# SMPS.net
KiCad netlist of a schematic drawn in Altium Designer
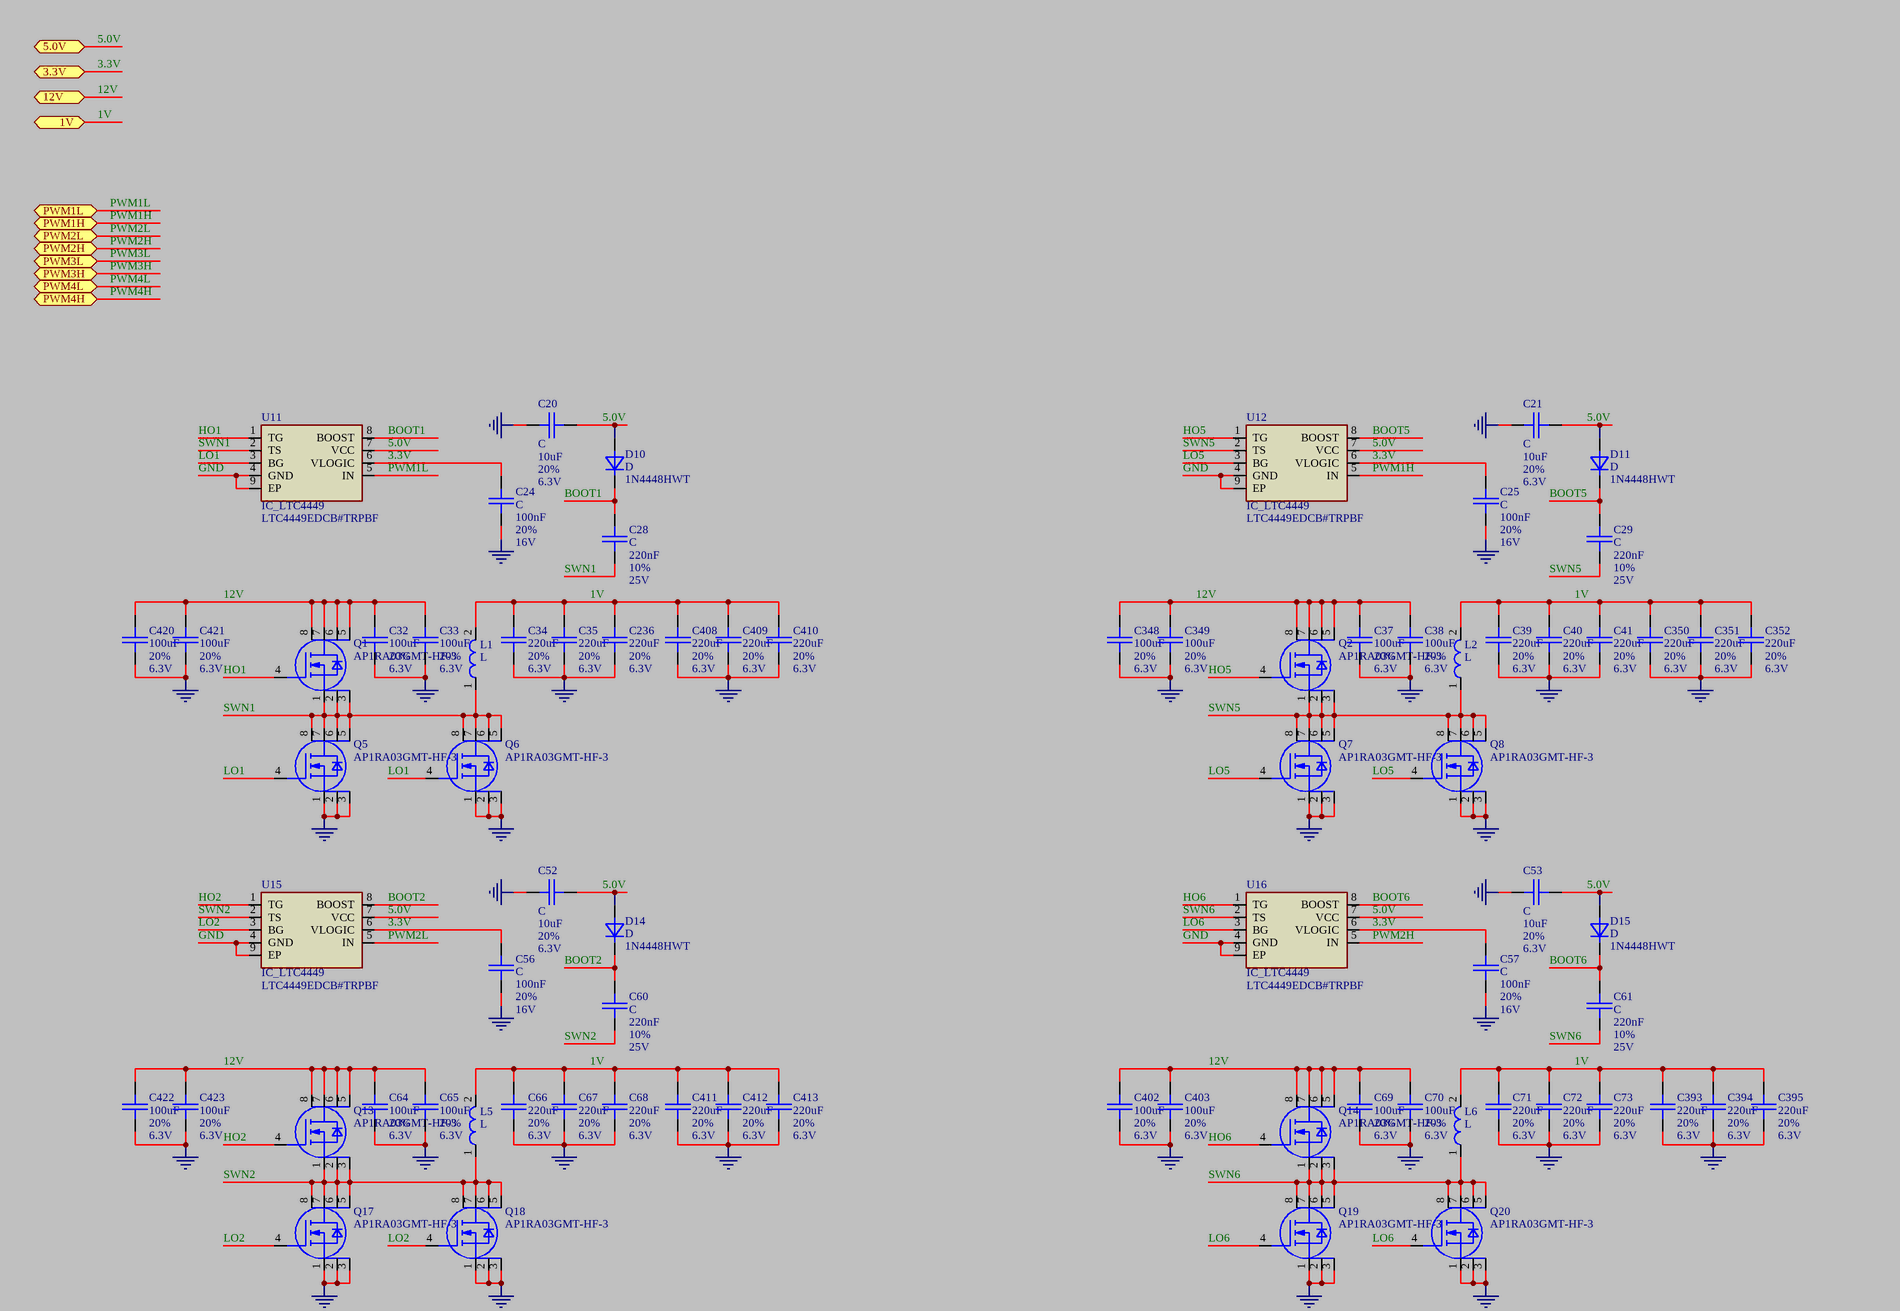
[diagram p0: SMPS.SchDoc, top left]
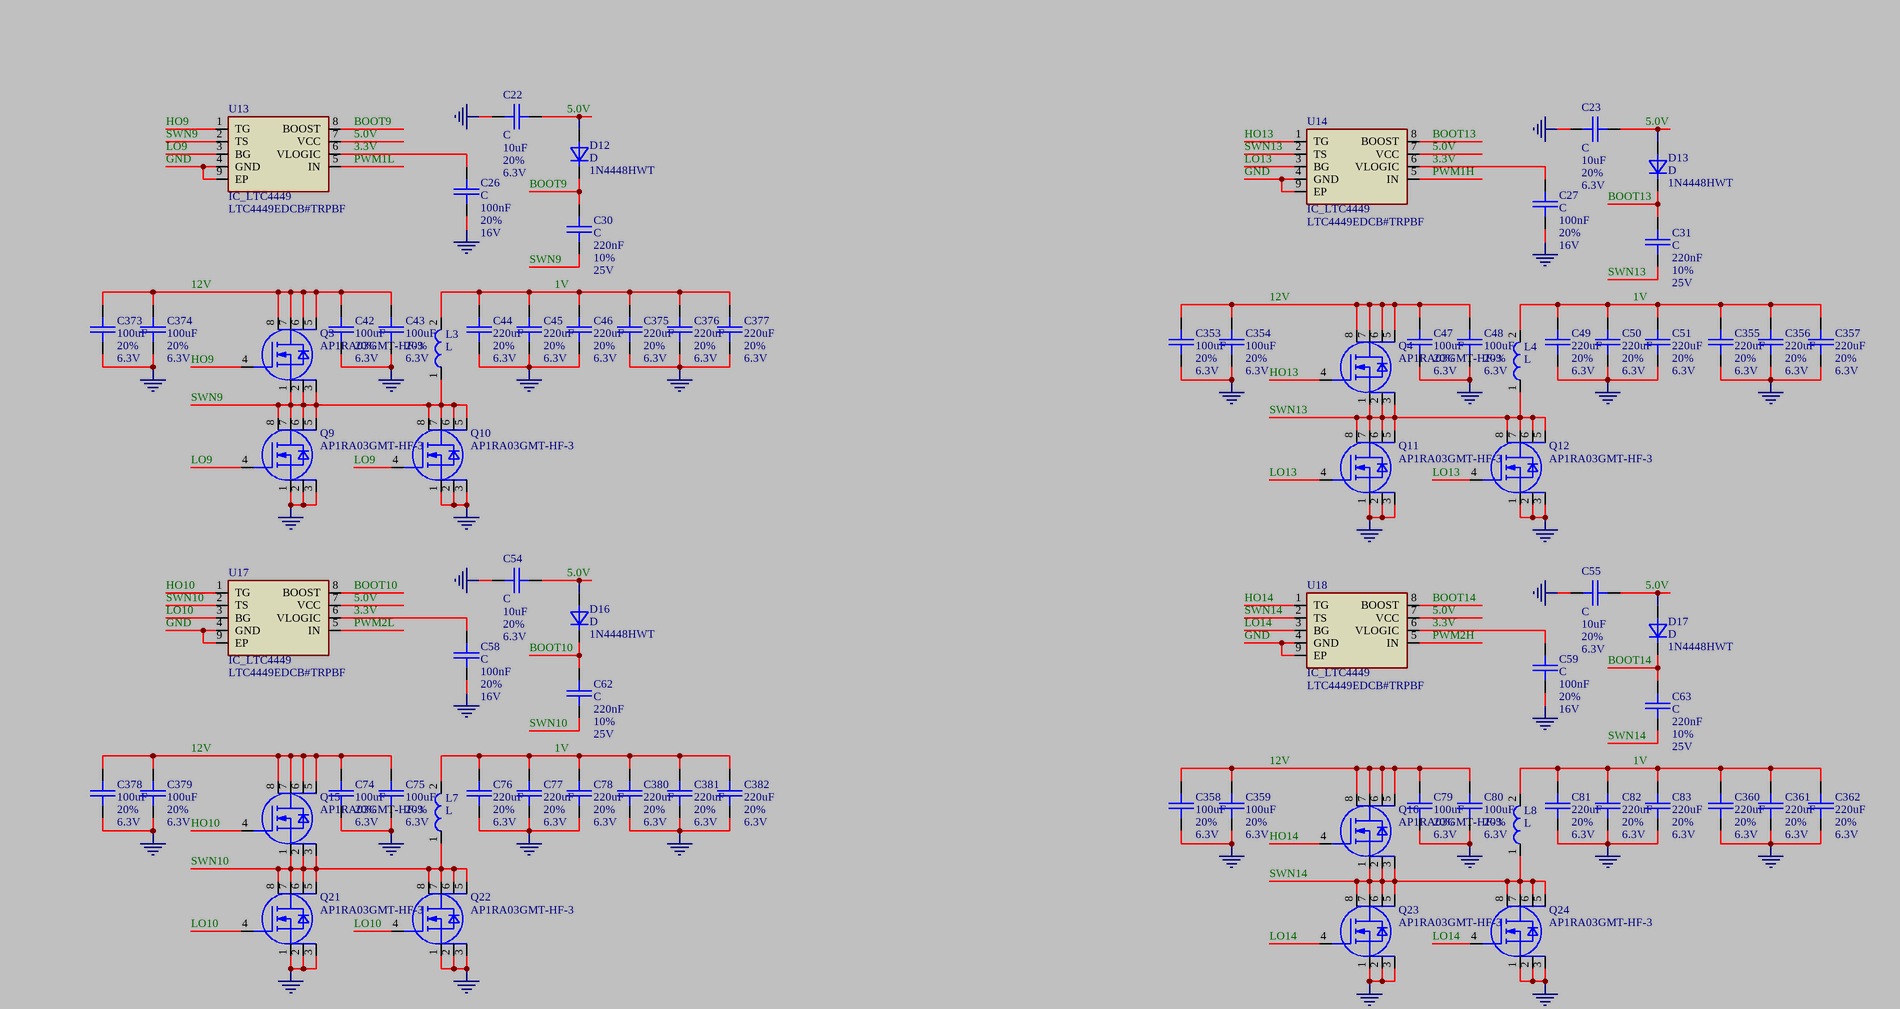
[diagram p1: SMPS.SchDoc, top right]
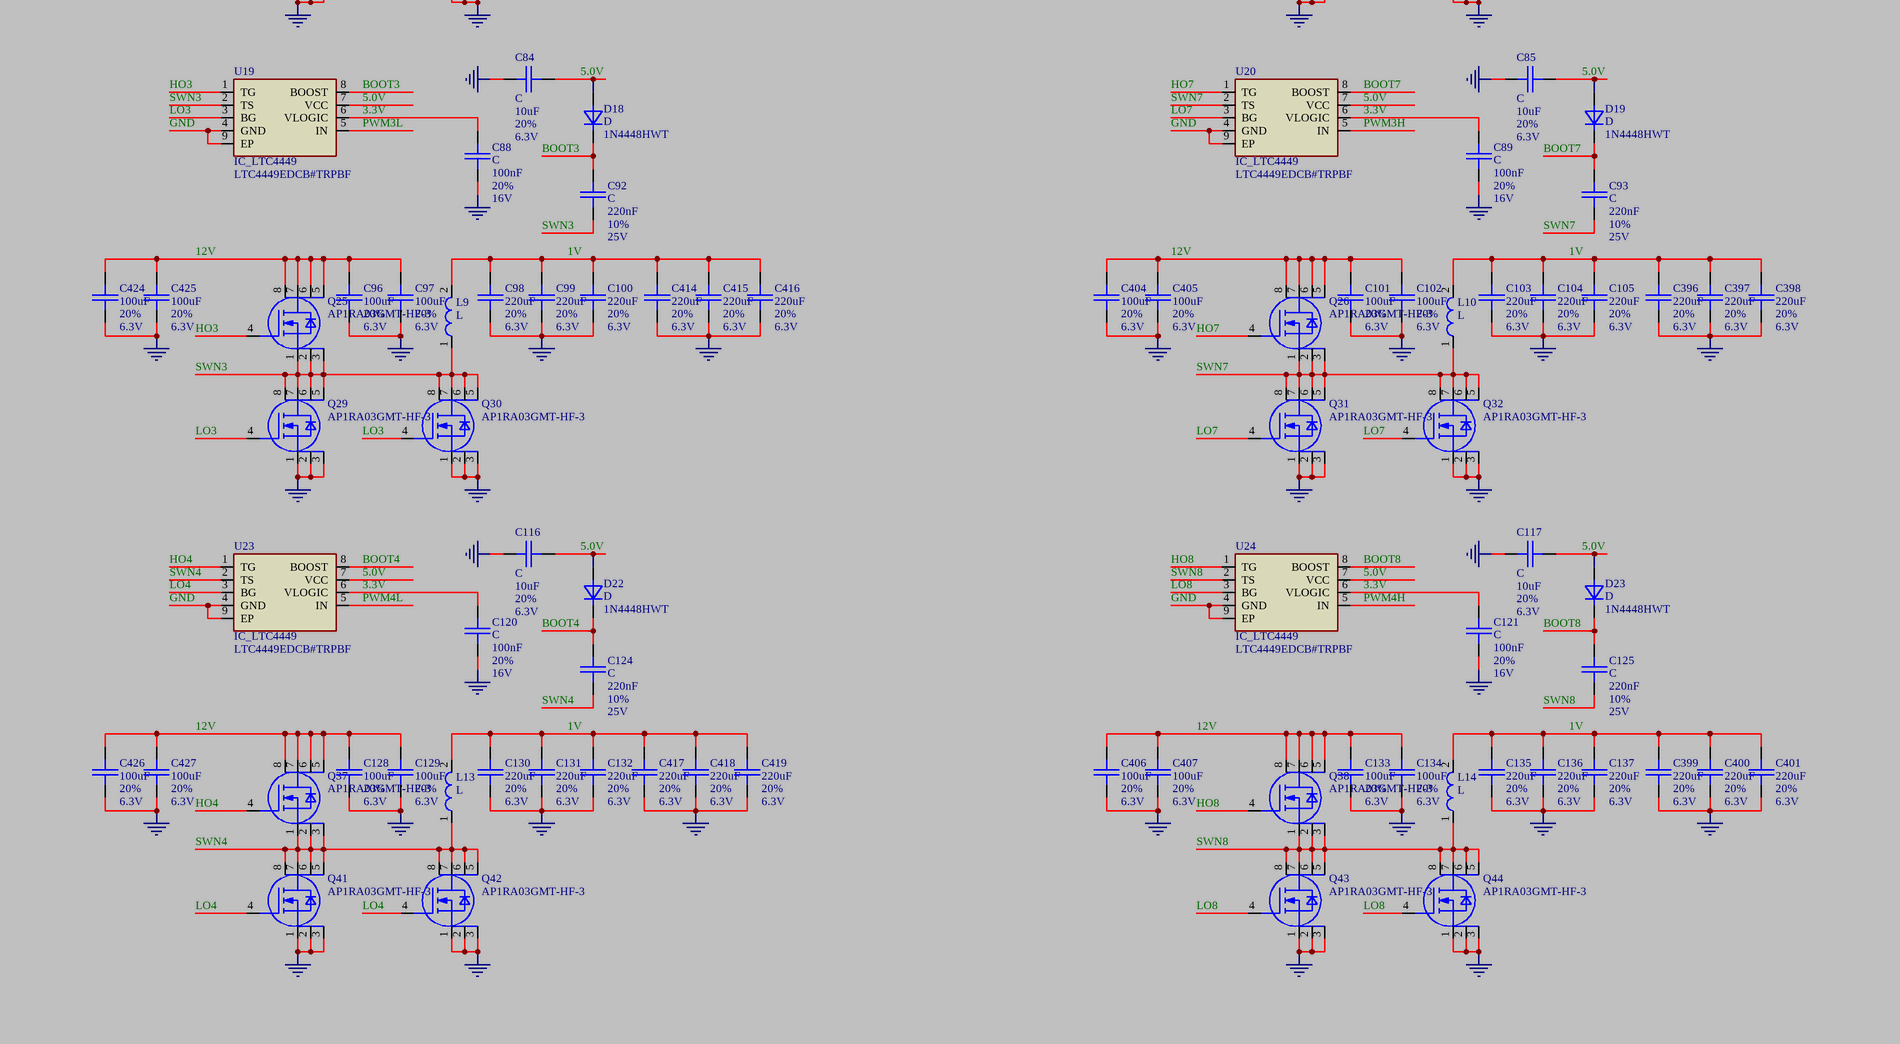
[diagram p2: SMPS.SchDoc, bottom left]
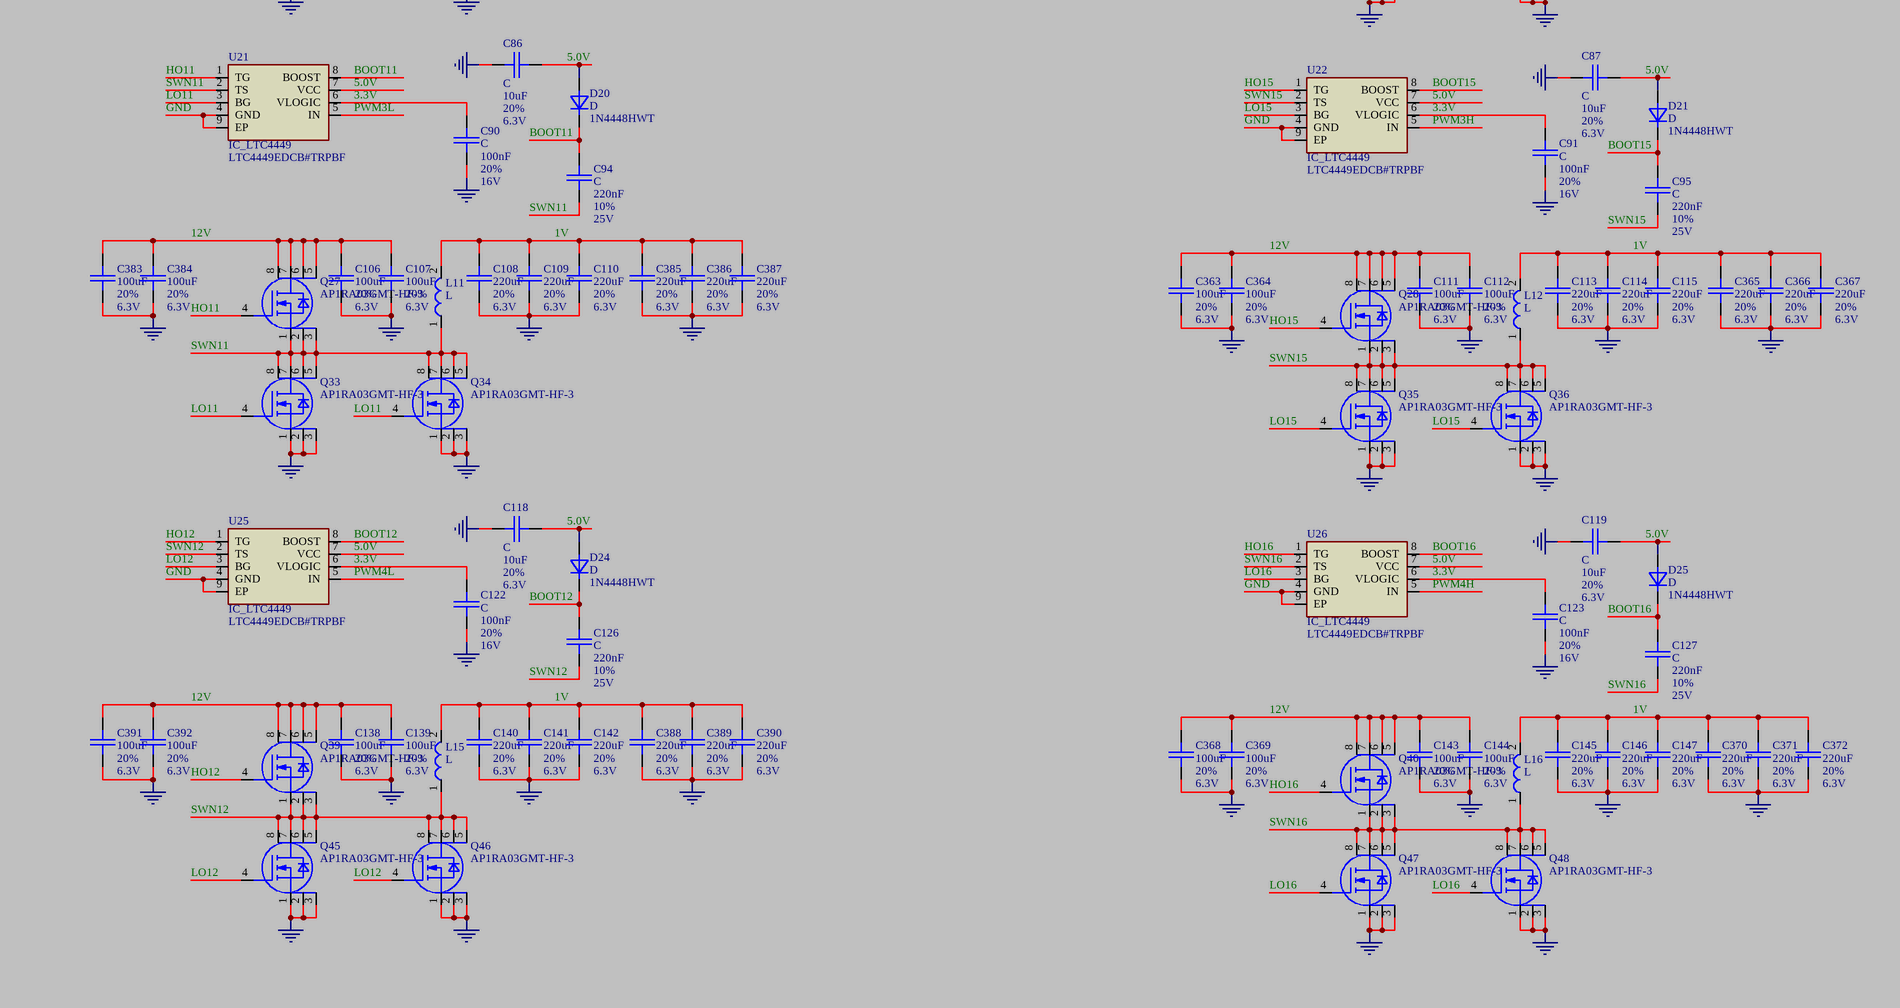
[diagram p3: SMPS.SchDoc, bottom right]

(export (version "E")
  (design (tool "Eeschema 10.0.6"))
  (components
    (comp (ref "C20")
      (value "C")
      (footprint "SMD_0603_CAPC1608X95N")
      (fields
        (field (name "DB_PART_NUMBER") "CAP000043646")
        (field (name "DB_VALUE") "10uF")
        (field (name "DB_TOLERANCE") "20%")
        (field (name "DB_VOLTAGE") "6.3V")
        (field (name "DB_MANUFACTURER_PART") "KEMET    C0603C106M9PAC")
      )
      (libsource (lib "Database_Libs1") (part "C"))
    )
    (comp (ref "C21")
      (value "C")
      (footprint "SMD_0603_CAPC1608X95N")
      (fields
        (field (name "DB_PART_NUMBER") "CAP000043646")
        (field (name "DB_VALUE") "10uF")
        (field (name "DB_TOLERANCE") "20%")
        (field (name "DB_VOLTAGE") "6.3V")
        (field (name "DB_MANUFACTURER_PART") "KEMET    C0603C106M9PAC")
      )
      (libsource (lib "Database_Libs1") (part "C"))
    )
    (comp (ref "C22")
      (value "C")
      (footprint "SMD_0603_CAPC1608X95N")
      (fields
        (field (name "DB_PART_NUMBER") "CAP000043646")
        (field (name "DB_VALUE") "10uF")
        (field (name "DB_TOLERANCE") "20%")
        (field (name "DB_VOLTAGE") "6.3V")
        (field (name "DB_MANUFACTURER_PART") "KEMET    C0603C106M9PAC")
      )
      (libsource (lib "Database_Libs1") (part "C"))
    )
    (comp (ref "C23")
      (value "C")
      (footprint "SMD_0603_CAPC1608X95N")
      (fields
        (field (name "DB_PART_NUMBER") "CAP000043646")
        (field (name "DB_VALUE") "10uF")
        (field (name "DB_TOLERANCE") "20%")
        (field (name "DB_VOLTAGE") "6.3V")
        (field (name "DB_MANUFACTURER_PART") "KEMET    C0603C106M9PAC")
      )
      (libsource (lib "Database_Libs1") (part "C"))
    )
    (comp (ref "C24")
      (value "C")
      (footprint "SMD_0402_CAPC1005X55N")
      (fields
        (field (name "DB_PART_NUMBER") "CAP000022751")
        (field (name "DB_VALUE") "100nF")
        (field (name "DB_TOLERANCE") "20%")
        (field (name "DB_VOLTAGE") "16V")
        (field (name "DB_MANUFACTURER_PART") "KEMET    C0402F104M4RAC")
      )
      (libsource (lib "Database_Libs1") (part "C"))
    )
    (comp (ref "C25")
      (value "C")
      (footprint "SMD_0402_CAPC1005X55N")
      (fields
        (field (name "DB_PART_NUMBER") "CAP000022751")
        (field (name "DB_VALUE") "100nF")
        (field (name "DB_TOLERANCE") "20%")
        (field (name "DB_VOLTAGE") "16V")
        (field (name "DB_MANUFACTURER_PART") "KEMET    C0402F104M4RAC")
      )
      (libsource (lib "Database_Libs1") (part "C"))
    )
    (comp (ref "C26")
      (value "C")
      (footprint "SMD_0402_CAPC1005X55N")
      (fields
        (field (name "DB_PART_NUMBER") "CAP000022751")
        (field (name "DB_VALUE") "100nF")
        (field (name "DB_TOLERANCE") "20%")
        (field (name "DB_VOLTAGE") "16V")
        (field (name "DB_MANUFACTURER_PART") "KEMET    C0402F104M4RAC")
      )
      (libsource (lib "Database_Libs1") (part "C"))
    )
    (comp (ref "C27")
      (value "C")
      (footprint "SMD_0402_CAPC1005X55N")
      (fields
        (field (name "DB_PART_NUMBER") "CAP000022751")
        (field (name "DB_VALUE") "100nF")
        (field (name "DB_TOLERANCE") "20%")
        (field (name "DB_VOLTAGE") "16V")
        (field (name "DB_MANUFACTURER_PART") "KEMET    C0402F104M4RAC")
      )
      (libsource (lib "Database_Libs1") (part "C"))
    )
    (comp (ref "C28")
      (value "C")
      (footprint "SMD_0603_CAPC1608X95N")
      (fields
        (field (name "DB_PART_NUMBER") "CAP000022968")
        (field (name "DB_VALUE") "220nF")
        (field (name "DB_TOLERANCE") "10%")
        (field (name "DB_VOLTAGE") "25V")
        (field (name "DB_MANUFACTURER_PART") "KEMET    C0603F224K3RAC")
      )
      (libsource (lib "Database_Libs1") (part "C"))
    )
    (comp (ref "C29")
      (value "C")
      (footprint "SMD_0603_CAPC1608X95N")
      (fields
        (field (name "DB_PART_NUMBER") "CAP000022968")
        (field (name "DB_VALUE") "220nF")
        (field (name "DB_TOLERANCE") "10%")
        (field (name "DB_VOLTAGE") "25V")
        (field (name "DB_MANUFACTURER_PART") "KEMET    C0603F224K3RAC")
      )
      (libsource (lib "Database_Libs1") (part "C"))
    )
    (comp (ref "C30")
      (value "C")
      (footprint "SMD_0603_CAPC1608X95N")
      (fields
        (field (name "DB_PART_NUMBER") "CAP000022968")
        (field (name "DB_VALUE") "220nF")
        (field (name "DB_TOLERANCE") "10%")
        (field (name "DB_VOLTAGE") "25V")
        (field (name "DB_MANUFACTURER_PART") "KEMET    C0603F224K3RAC")
      )
      (libsource (lib "Database_Libs1") (part "C"))
    )
    (comp (ref "C31")
      (value "C")
      (footprint "SMD_0603_CAPC1608X95N")
      (fields
        (field (name "DB_PART_NUMBER") "CAP000022968")
        (field (name "DB_VALUE") "220nF")
        (field (name "DB_TOLERANCE") "10%")
        (field (name "DB_VOLTAGE") "25V")
        (field (name "DB_MANUFACTURER_PART") "KEMET    C0603F224K3RAC")
      )
      (libsource (lib "Database_Libs1") (part "C"))
    )
    (comp (ref "C32")
      (value "C")
      (footprint "SMD_1210_CAPC3225X270N")
      (fields
        (field (name "DB_PART_NUMBER") "CAP000043701")
        (field (name "DB_VALUE") "100uF")
        (field (name "DB_TOLERANCE") "20%")
        (field (name "DB_VOLTAGE") "6.3V")
        (field (name "DB_MANUFACTURER_PART") "KEMET    C1210C107M9PAC")
      )
      (libsource (lib "Database_Libs1") (part "C"))
    )
    (comp (ref "C33")
      (value "C")
      (footprint "SMD_1210_CAPC3225X270N")
      (fields
        (field (name "DB_PART_NUMBER") "CAP000043701")
        (field (name "DB_VALUE") "100uF")
        (field (name "DB_TOLERANCE") "20%")
        (field (name "DB_VOLTAGE") "6.3V")
        (field (name "DB_MANUFACTURER_PART") "KEMET    C1210C107M9PAC")
      )
      (libsource (lib "Database_Libs1") (part "C"))
    )
    (comp (ref "C34")
      (value "C")
      (footprint "SMD_1210_CAPC3225X279N")
      (fields
        (field (name "DB_PART_NUMBER") "CAP000047355")
        (field (name "DB_VALUE") "220uF")
        (field (name "DB_TOLERANCE") "20%")
        (field (name "DB_VOLTAGE") "6.3V")
        (field (name "DB_MANUFACTURER_PART") "SAMSUNG    CL32A227MQVNNNE")
        (field (name "DB_APPROVED_BY") "VSN")
      )
      (libsource (lib "Database_Libs1") (part "C"))
    )
    (comp (ref "C35")
      (value "C")
      (footprint "SMD_1210_CAPC3225X279N")
      (fields
        (field (name "DB_PART_NUMBER") "CAP000047355")
        (field (name "DB_VALUE") "220uF")
        (field (name "DB_TOLERANCE") "20%")
        (field (name "DB_VOLTAGE") "6.3V")
        (field (name "DB_MANUFACTURER_PART") "SAMSUNG    CL32A227MQVNNNE")
        (field (name "DB_APPROVED_BY") "VSN")
      )
      (libsource (lib "Database_Libs1") (part "C"))
    )
    (comp (ref "C37")
      (value "C")
      (footprint "SMD_1210_CAPC3225X270N")
      (fields
        (field (name "DB_PART_NUMBER") "CAP000043701")
        (field (name "DB_VALUE") "100uF")
        (field (name "DB_TOLERANCE") "20%")
        (field (name "DB_VOLTAGE") "6.3V")
        (field (name "DB_MANUFACTURER_PART") "KEMET    C1210C107M9PAC")
      )
      (libsource (lib "Database_Libs1") (part "C"))
    )
    (comp (ref "C38")
      (value "C")
      (footprint "SMD_1210_CAPC3225X270N")
      (fields
        (field (name "DB_PART_NUMBER") "CAP000043701")
        (field (name "DB_VALUE") "100uF")
        (field (name "DB_TOLERANCE") "20%")
        (field (name "DB_VOLTAGE") "6.3V")
        (field (name "DB_MANUFACTURER_PART") "KEMET    C1210C107M9PAC")
      )
      (libsource (lib "Database_Libs1") (part "C"))
    )
    (comp (ref "C39")
      (value "C")
      (footprint "SMD_1210_CAPC3225X279N")
      (fields
        (field (name "DB_PART_NUMBER") "CAP000047355")
        (field (name "DB_VALUE") "220uF")
        (field (name "DB_TOLERANCE") "20%")
        (field (name "DB_VOLTAGE") "6.3V")
        (field (name "DB_MANUFACTURER_PART") "SAMSUNG    CL32A227MQVNNNE")
        (field (name "DB_APPROVED_BY") "VSN")
      )
      (libsource (lib "Database_Libs1") (part "C"))
    )
    (comp (ref "C40")
      (value "C")
      (footprint "SMD_1210_CAPC3225X279N")
      (fields
        (field (name "DB_PART_NUMBER") "CAP000047355")
        (field (name "DB_VALUE") "220uF")
        (field (name "DB_TOLERANCE") "20%")
        (field (name "DB_VOLTAGE") "6.3V")
        (field (name "DB_MANUFACTURER_PART") "SAMSUNG    CL32A227MQVNNNE")
        (field (name "DB_APPROVED_BY") "VSN")
      )
      (libsource (lib "Database_Libs1") (part "C"))
    )
    (comp (ref "C41")
      (value "C")
      (footprint "SMD_1210_CAPC3225X279N")
      (fields
        (field (name "DB_PART_NUMBER") "CAP000047355")
        (field (name "DB_VALUE") "220uF")
        (field (name "DB_TOLERANCE") "20%")
        (field (name "DB_VOLTAGE") "6.3V")
        (field (name "DB_MANUFACTURER_PART") "SAMSUNG    CL32A227MQVNNNE")
        (field (name "DB_APPROVED_BY") "VSN")
      )
      (libsource (lib "Database_Libs1") (part "C"))
    )
    (comp (ref "C42")
      (value "C")
      (footprint "SMD_1210_CAPC3225X270N")
      (fields
        (field (name "DB_PART_NUMBER") "CAP000043701")
        (field (name "DB_VALUE") "100uF")
        (field (name "DB_TOLERANCE") "20%")
        (field (name "DB_VOLTAGE") "6.3V")
        (field (name "DB_MANUFACTURER_PART") "KEMET    C1210C107M9PAC")
      )
      (libsource (lib "Database_Libs1") (part "C"))
    )
    (comp (ref "C43")
      (value "C")
      (footprint "SMD_1210_CAPC3225X270N")
      (fields
        (field (name "DB_PART_NUMBER") "CAP000043701")
        (field (name "DB_VALUE") "100uF")
        (field (name "DB_TOLERANCE") "20%")
        (field (name "DB_VOLTAGE") "6.3V")
        (field (name "DB_MANUFACTURER_PART") "KEMET    C1210C107M9PAC")
      )
      (libsource (lib "Database_Libs1") (part "C"))
    )
    (comp (ref "C44")
      (value "C")
      (footprint "SMD_1210_CAPC3225X279N")
      (fields
        (field (name "DB_PART_NUMBER") "CAP000047355")
        (field (name "DB_VALUE") "220uF")
        (field (name "DB_TOLERANCE") "20%")
        (field (name "DB_VOLTAGE") "6.3V")
        (field (name "DB_MANUFACTURER_PART") "SAMSUNG    CL32A227MQVNNNE")
        (field (name "DB_APPROVED_BY") "VSN")
      )
      (libsource (lib "Database_Libs1") (part "C"))
    )
    (comp (ref "C45")
      (value "C")
      (footprint "SMD_1210_CAPC3225X279N")
      (fields
        (field (name "DB_PART_NUMBER") "CAP000047355")
        (field (name "DB_VALUE") "220uF")
        (field (name "DB_TOLERANCE") "20%")
        (field (name "DB_VOLTAGE") "6.3V")
        (field (name "DB_MANUFACTURER_PART") "SAMSUNG    CL32A227MQVNNNE")
        (field (name "DB_APPROVED_BY") "VSN")
      )
      (libsource (lib "Database_Libs1") (part "C"))
    )
    (comp (ref "C46")
      (value "C")
      (footprint "SMD_1210_CAPC3225X279N")
      (fields
        (field (name "DB_PART_NUMBER") "CAP000047355")
        (field (name "DB_VALUE") "220uF")
        (field (name "DB_TOLERANCE") "20%")
        (field (name "DB_VOLTAGE") "6.3V")
        (field (name "DB_MANUFACTURER_PART") "SAMSUNG    CL32A227MQVNNNE")
        (field (name "DB_APPROVED_BY") "VSN")
      )
      (libsource (lib "Database_Libs1") (part "C"))
    )
    (comp (ref "C47")
      (value "C")
      (footprint "SMD_1210_CAPC3225X270N")
      (fields
        (field (name "DB_PART_NUMBER") "CAP000043701")
        (field (name "DB_VALUE") "100uF")
        (field (name "DB_TOLERANCE") "20%")
        (field (name "DB_VOLTAGE") "6.3V")
        (field (name "DB_MANUFACTURER_PART") "KEMET    C1210C107M9PAC")
      )
      (libsource (lib "Database_Libs1") (part "C"))
    )
    (comp (ref "C48")
      (value "C")
      (footprint "SMD_1210_CAPC3225X270N")
      (fields
        (field (name "DB_PART_NUMBER") "CAP000043701")
        (field (name "DB_VALUE") "100uF")
        (field (name "DB_TOLERANCE") "20%")
        (field (name "DB_VOLTAGE") "6.3V")
        (field (name "DB_MANUFACTURER_PART") "KEMET    C1210C107M9PAC")
      )
      (libsource (lib "Database_Libs1") (part "C"))
    )
    (comp (ref "C49")
      (value "C")
      (footprint "SMD_1210_CAPC3225X279N")
      (fields
        (field (name "DB_PART_NUMBER") "CAP000047355")
        (field (name "DB_VALUE") "220uF")
        (field (name "DB_TOLERANCE") "20%")
        (field (name "DB_VOLTAGE") "6.3V")
        (field (name "DB_MANUFACTURER_PART") "SAMSUNG    CL32A227MQVNNNE")
        (field (name "DB_APPROVED_BY") "VSN")
      )
      (libsource (lib "Database_Libs1") (part "C"))
    )
    (comp (ref "C50")
      (value "C")
      (footprint "SMD_1210_CAPC3225X279N")
      (fields
        (field (name "DB_PART_NUMBER") "CAP000047355")
        (field (name "DB_VALUE") "220uF")
        (field (name "DB_TOLERANCE") "20%")
        (field (name "DB_VOLTAGE") "6.3V")
        (field (name "DB_MANUFACTURER_PART") "SAMSUNG    CL32A227MQVNNNE")
        (field (name "DB_APPROVED_BY") "VSN")
      )
      (libsource (lib "Database_Libs1") (part "C"))
    )
    (comp (ref "C51")
      (value "C")
      (footprint "SMD_1210_CAPC3225X279N")
      (fields
        (field (name "DB_PART_NUMBER") "CAP000047355")
        (field (name "DB_VALUE") "220uF")
        (field (name "DB_TOLERANCE") "20%")
        (field (name "DB_VOLTAGE") "6.3V")
        (field (name "DB_MANUFACTURER_PART") "SAMSUNG    CL32A227MQVNNNE")
        (field (name "DB_APPROVED_BY") "VSN")
      )
      (libsource (lib "Database_Libs1") (part "C"))
    )
    (comp (ref "C52")
      (value "C")
      (footprint "SMD_0603_CAPC1608X95N")
      (fields
        (field (name "DB_PART_NUMBER") "CAP000043646")
        (field (name "DB_VALUE") "10uF")
        (field (name "DB_TOLERANCE") "20%")
        (field (name "DB_VOLTAGE") "6.3V")
        (field (name "DB_MANUFACTURER_PART") "KEMET    C0603C106M9PAC")
      )
      (libsource (lib "Database_Libs1") (part "C"))
    )
    (comp (ref "C53")
      (value "C")
      (footprint "SMD_0603_CAPC1608X95N")
      (fields
        (field (name "DB_PART_NUMBER") "CAP000043646")
        (field (name "DB_VALUE") "10uF")
        (field (name "DB_TOLERANCE") "20%")
        (field (name "DB_VOLTAGE") "6.3V")
        (field (name "DB_MANUFACTURER_PART") "KEMET    C0603C106M9PAC")
      )
      (libsource (lib "Database_Libs1") (part "C"))
    )
    (comp (ref "C54")
      (value "C")
      (footprint "SMD_0603_CAPC1608X95N")
      (fields
        (field (name "DB_PART_NUMBER") "CAP000043646")
        (field (name "DB_VALUE") "10uF")
        (field (name "DB_TOLERANCE") "20%")
        (field (name "DB_VOLTAGE") "6.3V")
        (field (name "DB_MANUFACTURER_PART") "KEMET    C0603C106M9PAC")
      )
      (libsource (lib "Database_Libs1") (part "C"))
    )
    (comp (ref "C55")
      (value "C")
      (footprint "SMD_0603_CAPC1608X95N")
      (fields
        (field (name "DB_PART_NUMBER") "CAP000043646")
        (field (name "DB_VALUE") "10uF")
        (field (name "DB_TOLERANCE") "20%")
        (field (name "DB_VOLTAGE") "6.3V")
        (field (name "DB_MANUFACTURER_PART") "KEMET    C0603C106M9PAC")
      )
      (libsource (lib "Database_Libs1") (part "C"))
    )
    (comp (ref "C56")
      (value "C")
      (footprint "SMD_0402_CAPC1005X55N")
      (fields
        (field (name "DB_PART_NUMBER") "CAP000022751")
        (field (name "DB_VALUE") "100nF")
        (field (name "DB_TOLERANCE") "20%")
        (field (name "DB_VOLTAGE") "16V")
        (field (name "DB_MANUFACTURER_PART") "KEMET    C0402F104M4RAC")
      )
      (libsource (lib "Database_Libs1") (part "C"))
    )
    (comp (ref "C57")
      (value "C")
      (footprint "SMD_0402_CAPC1005X55N")
      (fields
        (field (name "DB_PART_NUMBER") "CAP000022751")
        (field (name "DB_VALUE") "100nF")
        (field (name "DB_TOLERANCE") "20%")
        (field (name "DB_VOLTAGE") "16V")
        (field (name "DB_MANUFACTURER_PART") "KEMET    C0402F104M4RAC")
      )
      (libsource (lib "Database_Libs1") (part "C"))
    )
    (comp (ref "C58")
      (value "C")
      (footprint "SMD_0402_CAPC1005X55N")
      (fields
        (field (name "DB_PART_NUMBER") "CAP000022751")
        (field (name "DB_VALUE") "100nF")
        (field (name "DB_TOLERANCE") "20%")
        (field (name "DB_VOLTAGE") "16V")
        (field (name "DB_MANUFACTURER_PART") "KEMET    C0402F104M4RAC")
      )
      (libsource (lib "Database_Libs1") (part "C"))
    )
    (comp (ref "C59")
      (value "C")
      (footprint "SMD_0402_CAPC1005X55N")
      (fields
        (field (name "DB_PART_NUMBER") "CAP000022751")
        (field (name "DB_VALUE") "100nF")
        (field (name "DB_TOLERANCE") "20%")
        (field (name "DB_VOLTAGE") "16V")
        (field (name "DB_MANUFACTURER_PART") "KEMET    C0402F104M4RAC")
      )
      (libsource (lib "Database_Libs1") (part "C"))
    )
    (comp (ref "C60")
      (value "C")
      (footprint "SMD_0603_CAPC1608X95N")
      (fields
        (field (name "DB_PART_NUMBER") "CAP000022968")
        (field (name "DB_VALUE") "220nF")
        (field (name "DB_TOLERANCE") "10%")
        (field (name "DB_VOLTAGE") "25V")
        (field (name "DB_MANUFACTURER_PART") "KEMET    C0603F224K3RAC")
      )
      (libsource (lib "Database_Libs1") (part "C"))
    )
    (comp (ref "C61")
      (value "C")
      (footprint "SMD_0603_CAPC1608X95N")
      (fields
        (field (name "DB_PART_NUMBER") "CAP000022968")
        (field (name "DB_VALUE") "220nF")
        (field (name "DB_TOLERANCE") "10%")
        (field (name "DB_VOLTAGE") "25V")
        (field (name "DB_MANUFACTURER_PART") "KEMET    C0603F224K3RAC")
      )
      (libsource (lib "Database_Libs1") (part "C"))
    )
    (comp (ref "C62")
      (value "C")
      (footprint "SMD_0603_CAPC1608X95N")
      (fields
        (field (name "DB_PART_NUMBER") "CAP000022968")
        (field (name "DB_VALUE") "220nF")
        (field (name "DB_TOLERANCE") "10%")
        (field (name "DB_VOLTAGE") "25V")
        (field (name "DB_MANUFACTURER_PART") "KEMET    C0603F224K3RAC")
      )
      (libsource (lib "Database_Libs1") (part "C"))
    )
    (comp (ref "C63")
      (value "C")
      (footprint "SMD_0603_CAPC1608X95N")
      (fields
        (field (name "DB_PART_NUMBER") "CAP000022968")
        (field (name "DB_VALUE") "220nF")
        (field (name "DB_TOLERANCE") "10%")
        (field (name "DB_VOLTAGE") "25V")
        (field (name "DB_MANUFACTURER_PART") "KEMET    C0603F224K3RAC")
      )
      (libsource (lib "Database_Libs1") (part "C"))
    )
    (comp (ref "C64")
      (value "C")
      (footprint "SMD_1210_CAPC3225X270N")
      (fields
        (field (name "DB_PART_NUMBER") "CAP000043701")
        (field (name "DB_VALUE") "100uF")
        (field (name "DB_TOLERANCE") "20%")
        (field (name "DB_VOLTAGE") "6.3V")
        (field (name "DB_MANUFACTURER_PART") "KEMET    C1210C107M9PAC")
      )
      (libsource (lib "Database_Libs1") (part "C"))
    )
    (comp (ref "C65")
      (value "C")
      (footprint "SMD_1210_CAPC3225X270N")
      (fields
        (field (name "DB_PART_NUMBER") "CAP000043701")
        (field (name "DB_VALUE") "100uF")
        (field (name "DB_TOLERANCE") "20%")
        (field (name "DB_VOLTAGE") "6.3V")
        (field (name "DB_MANUFACTURER_PART") "KEMET    C1210C107M9PAC")
      )
      (libsource (lib "Database_Libs1") (part "C"))
    )
    (comp (ref "C66")
      (value "C")
      (footprint "SMD_1210_CAPC3225X279N")
      (fields
        (field (name "DB_PART_NUMBER") "CAP000047355")
        (field (name "DB_VALUE") "220uF")
        (field (name "DB_TOLERANCE") "20%")
        (field (name "DB_VOLTAGE") "6.3V")
        (field (name "DB_MANUFACTURER_PART") "SAMSUNG    CL32A227MQVNNNE")
        (field (name "DB_APPROVED_BY") "VSN")
      )
      (libsource (lib "Database_Libs1") (part "C"))
    )
    (comp (ref "C67")
      (value "C")
      (footprint "SMD_1210_CAPC3225X279N")
      (fields
        (field (name "DB_PART_NUMBER") "CAP000047355")
        (field (name "DB_VALUE") "220uF")
        (field (name "DB_TOLERANCE") "20%")
        (field (name "DB_VOLTAGE") "6.3V")
        (field (name "DB_MANUFACTURER_PART") "SAMSUNG    CL32A227MQVNNNE")
        (field (name "DB_APPROVED_BY") "VSN")
      )
      (libsource (lib "Database_Libs1") (part "C"))
    )
    (comp (ref "C68")
      (value "C")
      (footprint "SMD_1210_CAPC3225X279N")
      (fields
        (field (name "DB_PART_NUMBER") "CAP000047355")
        (field (name "DB_VALUE") "220uF")
        (field (name "DB_TOLERANCE") "20%")
        (field (name "DB_VOLTAGE") "6.3V")
        (field (name "DB_MANUFACTURER_PART") "SAMSUNG    CL32A227MQVNNNE")
        (field (name "DB_APPROVED_BY") "VSN")
      )
      (libsource (lib "Database_Libs1") (part "C"))
    )
    (comp (ref "C69")
      (value "C")
      (footprint "SMD_1210_CAPC3225X270N")
      (fields
        (field (name "DB_PART_NUMBER") "CAP000043701")
        (field (name "DB_VALUE") "100uF")
        (field (name "DB_TOLERANCE") "20%")
        (field (name "DB_VOLTAGE") "6.3V")
        (field (name "DB_MANUFACTURER_PART") "KEMET    C1210C107M9PAC")
      )
      (libsource (lib "Database_Libs1") (part "C"))
    )
    (comp (ref "C70")
      (value "C")
      (footprint "SMD_1210_CAPC3225X270N")
      (fields
        (field (name "DB_PART_NUMBER") "CAP000043701")
        (field (name "DB_VALUE") "100uF")
        (field (name "DB_TOLERANCE") "20%")
        (field (name "DB_VOLTAGE") "6.3V")
        (field (name "DB_MANUFACTURER_PART") "KEMET    C1210C107M9PAC")
      )
      (libsource (lib "Database_Libs1") (part "C"))
    )
    (comp (ref "C71")
      (value "C")
      (footprint "SMD_1210_CAPC3225X279N")
      (fields
        (field (name "DB_PART_NUMBER") "CAP000047355")
        (field (name "DB_VALUE") "220uF")
        (field (name "DB_TOLERANCE") "20%")
        (field (name "DB_VOLTAGE") "6.3V")
        (field (name "DB_MANUFACTURER_PART") "SAMSUNG    CL32A227MQVNNNE")
        (field (name "DB_APPROVED_BY") "VSN")
      )
      (libsource (lib "Database_Libs1") (part "C"))
    )
    (comp (ref "C72")
      (value "C")
      (footprint "SMD_1210_CAPC3225X279N")
      (fields
        (field (name "DB_PART_NUMBER") "CAP000047355")
        (field (name "DB_VALUE") "220uF")
        (field (name "DB_TOLERANCE") "20%")
        (field (name "DB_VOLTAGE") "6.3V")
        (field (name "DB_MANUFACTURER_PART") "SAMSUNG    CL32A227MQVNNNE")
        (field (name "DB_APPROVED_BY") "VSN")
      )
      (libsource (lib "Database_Libs1") (part "C"))
    )
    (comp (ref "C73")
      (value "C")
      (footprint "SMD_1210_CAPC3225X279N")
      (fields
        (field (name "DB_PART_NUMBER") "CAP000047355")
        (field (name "DB_VALUE") "220uF")
        (field (name "DB_TOLERANCE") "20%")
        (field (name "DB_VOLTAGE") "6.3V")
        (field (name "DB_MANUFACTURER_PART") "SAMSUNG    CL32A227MQVNNNE")
        (field (name "DB_APPROVED_BY") "VSN")
      )
      (libsource (lib "Database_Libs1") (part "C"))
    )
    (comp (ref "C74")
      (value "C")
      (footprint "SMD_1210_CAPC3225X270N")
      (fields
        (field (name "DB_PART_NUMBER") "CAP000043701")
        (field (name "DB_VALUE") "100uF")
        (field (name "DB_TOLERANCE") "20%")
        (field (name "DB_VOLTAGE") "6.3V")
        (field (name "DB_MANUFACTURER_PART") "KEMET    C1210C107M9PAC")
      )
      (libsource (lib "Database_Libs1") (part "C"))
    )
    (comp (ref "C75")
      (value "C")
      (footprint "SMD_1210_CAPC3225X270N")
      (fields
        (field (name "DB_PART_NUMBER") "CAP000043701")
        (field (name "DB_VALUE") "100uF")
        (field (name "DB_TOLERANCE") "20%")
        (field (name "DB_VOLTAGE") "6.3V")
        (field (name "DB_MANUFACTURER_PART") "KEMET    C1210C107M9PAC")
      )
      (libsource (lib "Database_Libs1") (part "C"))
    )
    (comp (ref "C76")
      (value "C")
      (footprint "SMD_1210_CAPC3225X279N")
      (fields
        (field (name "DB_PART_NUMBER") "CAP000047355")
        (field (name "DB_VALUE") "220uF")
        (field (name "DB_TOLERANCE") "20%")
        (field (name "DB_VOLTAGE") "6.3V")
        (field (name "DB_MANUFACTURER_PART") "SAMSUNG    CL32A227MQVNNNE")
        (field (name "DB_APPROVED_BY") "VSN")
      )
      (libsource (lib "Database_Libs1") (part "C"))
    )
    (comp (ref "C77")
      (value "C")
      (footprint "SMD_1210_CAPC3225X279N")
      (fields
        (field (name "DB_PART_NUMBER") "CAP000047355")
        (field (name "DB_VALUE") "220uF")
        (field (name "DB_TOLERANCE") "20%")
        (field (name "DB_VOLTAGE") "6.3V")
        (field (name "DB_MANUFACTURER_PART") "SAMSUNG    CL32A227MQVNNNE")
        (field (name "DB_APPROVED_BY") "VSN")
      )
      (libsource (lib "Database_Libs1") (part "C"))
    )
    (comp (ref "C78")
      (value "C")
      (footprint "SMD_1210_CAPC3225X279N")
      (fields
        (field (name "DB_PART_NUMBER") "CAP000047355")
        (field (name "DB_VALUE") "220uF")
        (field (name "DB_TOLERANCE") "20%")
        (field (name "DB_VOLTAGE") "6.3V")
        (field (name "DB_MANUFACTURER_PART") "SAMSUNG    CL32A227MQVNNNE")
        (field (name "DB_APPROVED_BY") "VSN")
      )
      (libsource (lib "Database_Libs1") (part "C"))
    )
    (comp (ref "C79")
      (value "C")
      (footprint "SMD_1210_CAPC3225X270N")
      (fields
        (field (name "DB_PART_NUMBER") "CAP000043701")
        (field (name "DB_VALUE") "100uF")
        (field (name "DB_TOLERANCE") "20%")
        (field (name "DB_VOLTAGE") "6.3V")
        (field (name "DB_MANUFACTURER_PART") "KEMET    C1210C107M9PAC")
      )
      (libsource (lib "Database_Libs1") (part "C"))
    )
    (comp (ref "C80")
      (value "C")
      (footprint "SMD_1210_CAPC3225X270N")
      (fields
        (field (name "DB_PART_NUMBER") "CAP000043701")
        (field (name "DB_VALUE") "100uF")
        (field (name "DB_TOLERANCE") "20%")
        (field (name "DB_VOLTAGE") "6.3V")
        (field (name "DB_MANUFACTURER_PART") "KEMET    C1210C107M9PAC")
      )
      (libsource (lib "Database_Libs1") (part "C"))
    )
    (comp (ref "C81")
      (value "C")
      (footprint "SMD_1210_CAPC3225X279N")
      (fields
        (field (name "DB_PART_NUMBER") "CAP000047355")
        (field (name "DB_VALUE") "220uF")
        (field (name "DB_TOLERANCE") "20%")
        (field (name "DB_VOLTAGE") "6.3V")
        (field (name "DB_MANUFACTURER_PART") "SAMSUNG    CL32A227MQVNNNE")
        (field (name "DB_APPROVED_BY") "VSN")
      )
      (libsource (lib "Database_Libs1") (part "C"))
    )
    (comp (ref "C82")
      (value "C")
      (footprint "SMD_1210_CAPC3225X279N")
      (fields
        (field (name "DB_PART_NUMBER") "CAP000047355")
        (field (name "DB_VALUE") "220uF")
        (field (name "DB_TOLERANCE") "20%")
        (field (name "DB_VOLTAGE") "6.3V")
        (field (name "DB_MANUFACTURER_PART") "SAMSUNG    CL32A227MQVNNNE")
        (field (name "DB_APPROVED_BY") "VSN")
      )
      (libsource (lib "Database_Libs1") (part "C"))
    )
    (comp (ref "C83")
      (value "C")
      (footprint "SMD_1210_CAPC3225X279N")
      (fields
        (field (name "DB_PART_NUMBER") "CAP000047355")
        (field (name "DB_VALUE") "220uF")
        (field (name "DB_TOLERANCE") "20%")
        (field (name "DB_VOLTAGE") "6.3V")
        (field (name "DB_MANUFACTURER_PART") "SAMSUNG    CL32A227MQVNNNE")
        (field (name "DB_APPROVED_BY") "VSN")
      )
      (libsource (lib "Database_Libs1") (part "C"))
    )
    (comp (ref "C84")
      (value "C")
      (footprint "SMD_0603_CAPC1608X95N")
      (fields
        (field (name "DB_PART_NUMBER") "CAP000043646")
        (field (name "DB_VALUE") "10uF")
        (field (name "DB_TOLERANCE") "20%")
        (field (name "DB_VOLTAGE") "6.3V")
        (field (name "DB_MANUFACTURER_PART") "KEMET    C0603C106M9PAC")
      )
      (libsource (lib "Database_Libs1") (part "C"))
    )
    (comp (ref "C85")
      (value "C")
      (footprint "SMD_0603_CAPC1608X95N")
      (fields
        (field (name "DB_PART_NUMBER") "CAP000043646")
        (field (name "DB_VALUE") "10uF")
        (field (name "DB_TOLERANCE") "20%")
        (field (name "DB_VOLTAGE") "6.3V")
        (field (name "DB_MANUFACTURER_PART") "KEMET    C0603C106M9PAC")
      )
      (libsource (lib "Database_Libs1") (part "C"))
    )
    (comp (ref "C86")
      (value "C")
      (footprint "SMD_0603_CAPC1608X95N")
      (fields
        (field (name "DB_PART_NUMBER") "CAP000043646")
        (field (name "DB_VALUE") "10uF")
        (field (name "DB_TOLERANCE") "20%")
        (field (name "DB_VOLTAGE") "6.3V")
        (field (name "DB_MANUFACTURER_PART") "KEMET    C0603C106M9PAC")
      )
      (libsource (lib "Database_Libs1") (part "C"))
    )
    (comp (ref "C87")
      (value "C")
      (footprint "SMD_0603_CAPC1608X95N")
      (fields
        (field (name "DB_PART_NUMBER") "CAP000043646")
        (field (name "DB_VALUE") "10uF")
        (field (name "DB_TOLERANCE") "20%")
        (field (name "DB_VOLTAGE") "6.3V")
        (field (name "DB_MANUFACTURER_PART") "KEMET    C0603C106M9PAC")
      )
      (libsource (lib "Database_Libs1") (part "C"))
    )
    (comp (ref "C88")
      (value "C")
      (footprint "SMD_0402_CAPC1005X55N")
      (fields
        (field (name "DB_PART_NUMBER") "CAP000022751")
        (field (name "DB_VALUE") "100nF")
        (field (name "DB_TOLERANCE") "20%")
        (field (name "DB_VOLTAGE") "16V")
        (field (name "DB_MANUFACTURER_PART") "KEMET    C0402F104M4RAC")
      )
      (libsource (lib "Database_Libs1") (part "C"))
    )
    (comp (ref "C89")
      (value "C")
      (footprint "SMD_0402_CAPC1005X55N")
      (fields
        (field (name "DB_PART_NUMBER") "CAP000022751")
        (field (name "DB_VALUE") "100nF")
        (field (name "DB_TOLERANCE") "20%")
        (field (name "DB_VOLTAGE") "16V")
        (field (name "DB_MANUFACTURER_PART") "KEMET    C0402F104M4RAC")
      )
      (libsource (lib "Database_Libs1") (part "C"))
    )
    (comp (ref "C90")
      (value "C")
      (footprint "SMD_0402_CAPC1005X55N")
      (fields
        (field (name "DB_PART_NUMBER") "CAP000022751")
        (field (name "DB_VALUE") "100nF")
        (field (name "DB_TOLERANCE") "20%")
        (field (name "DB_VOLTAGE") "16V")
        (field (name "DB_MANUFACTURER_PART") "KEMET    C0402F104M4RAC")
      )
      (libsource (lib "Database_Libs1") (part "C"))
    )
    (comp (ref "C91")
      (value "C")
      (footprint "SMD_0402_CAPC1005X55N")
      (fields
        (field (name "DB_PART_NUMBER") "CAP000022751")
        (field (name "DB_VALUE") "100nF")
        (field (name "DB_TOLERANCE") "20%")
        (field (name "DB_VOLTAGE") "16V")
        (field (name "DB_MANUFACTURER_PART") "KEMET    C0402F104M4RAC")
      )
      (libsource (lib "Database_Libs1") (part "C"))
    )
    (comp (ref "C92")
      (value "C")
      (footprint "SMD_0603_CAPC1608X95N")
      (fields
        (field (name "DB_PART_NUMBER") "CAP000022968")
        (field (name "DB_VALUE") "220nF")
        (field (name "DB_TOLERANCE") "10%")
        (field (name "DB_VOLTAGE") "25V")
        (field (name "DB_MANUFACTURER_PART") "KEMET    C0603F224K3RAC")
      )
      (libsource (lib "Database_Libs1") (part "C"))
    )
    (comp (ref "C93")
      (value "C")
      (footprint "SMD_0603_CAPC1608X95N")
      (fields
        (field (name "DB_PART_NUMBER") "CAP000022968")
        (field (name "DB_VALUE") "220nF")
        (field (name "DB_TOLERANCE") "10%")
        (field (name "DB_VOLTAGE") "25V")
        (field (name "DB_MANUFACTURER_PART") "KEMET    C0603F224K3RAC")
      )
      (libsource (lib "Database_Libs1") (part "C"))
    )
    (comp (ref "C94")
      (value "C")
      (footprint "SMD_0603_CAPC1608X95N")
      (fields
        (field (name "DB_PART_NUMBER") "CAP000022968")
        (field (name "DB_VALUE") "220nF")
        (field (name "DB_TOLERANCE") "10%")
        (field (name "DB_VOLTAGE") "25V")
        (field (name "DB_MANUFACTURER_PART") "KEMET    C0603F224K3RAC")
      )
      (libsource (lib "Database_Libs1") (part "C"))
    )
    (comp (ref "C95")
      (value "C")
      (footprint "SMD_0603_CAPC1608X95N")
      (fields
        (field (name "DB_PART_NUMBER") "CAP000022968")
        (field (name "DB_VALUE") "220nF")
        (field (name "DB_TOLERANCE") "10%")
        (field (name "DB_VOLTAGE") "25V")
        (field (name "DB_MANUFACTURER_PART") "KEMET    C0603F224K3RAC")
      )
      (libsource (lib "Database_Libs1") (part "C"))
    )
    (comp (ref "C96")
      (value "C")
      (footprint "SMD_1210_CAPC3225X270N")
      (fields
        (field (name "DB_PART_NUMBER") "CAP000043701")
        (field (name "DB_VALUE") "100uF")
        (field (name "DB_TOLERANCE") "20%")
        (field (name "DB_VOLTAGE") "6.3V")
        (field (name "DB_MANUFACTURER_PART") "KEMET    C1210C107M9PAC")
      )
      (libsource (lib "Database_Libs1") (part "C"))
    )
    (comp (ref "C97")
      (value "C")
      (footprint "SMD_1210_CAPC3225X270N")
      (fields
        (field (name "DB_PART_NUMBER") "CAP000043701")
        (field (name "DB_VALUE") "100uF")
        (field (name "DB_TOLERANCE") "20%")
        (field (name "DB_VOLTAGE") "6.3V")
        (field (name "DB_MANUFACTURER_PART") "KEMET    C1210C107M9PAC")
      )
      (libsource (lib "Database_Libs1") (part "C"))
    )
    (comp (ref "C98")
      (value "C")
      (footprint "SMD_1210_CAPC3225X279N")
      (fields
        (field (name "DB_PART_NUMBER") "CAP000047355")
        (field (name "DB_VALUE") "220uF")
        (field (name "DB_TOLERANCE") "20%")
        (field (name "DB_VOLTAGE") "6.3V")
        (field (name "DB_MANUFACTURER_PART") "SAMSUNG    CL32A227MQVNNNE")
        (field (name "DB_APPROVED_BY") "VSN")
      )
      (libsource (lib "Database_Libs1") (part "C"))
    )
    (comp (ref "C99")
      (value "C")
      (footprint "SMD_1210_CAPC3225X279N")
      (fields
        (field (name "DB_PART_NUMBER") "CAP000047355")
        (field (name "DB_VALUE") "220uF")
        (field (name "DB_TOLERANCE") "20%")
        (field (name "DB_VOLTAGE") "6.3V")
        (field (name "DB_MANUFACTURER_PART") "SAMSUNG    CL32A227MQVNNNE")
        (field (name "DB_APPROVED_BY") "VSN")
      )
      (libsource (lib "Database_Libs1") (part "C"))
    )
    (comp (ref "C100")
      (value "C")
      (footprint "SMD_1210_CAPC3225X279N")
      (fields
        (field (name "DB_PART_NUMBER") "CAP000047355")
        (field (name "DB_VALUE") "220uF")
        (field (name "DB_TOLERANCE") "20%")
        (field (name "DB_VOLTAGE") "6.3V")
        (field (name "DB_MANUFACTURER_PART") "SAMSUNG    CL32A227MQVNNNE")
        (field (name "DB_APPROVED_BY") "VSN")
      )
      (libsource (lib "Database_Libs1") (part "C"))
    )
    (comp (ref "C101")
      (value "C")
      (footprint "SMD_1210_CAPC3225X270N")
      (fields
        (field (name "DB_PART_NUMBER") "CAP000043701")
        (field (name "DB_VALUE") "100uF")
        (field (name "DB_TOLERANCE") "20%")
        (field (name "DB_VOLTAGE") "6.3V")
        (field (name "DB_MANUFACTURER_PART") "KEMET    C1210C107M9PAC")
      )
      (libsource (lib "Database_Libs1") (part "C"))
    )
    (comp (ref "C102")
      (value "C")
      (footprint "SMD_1210_CAPC3225X270N")
      (fields
        (field (name "DB_PART_NUMBER") "CAP000043701")
        (field (name "DB_VALUE") "100uF")
        (field (name "DB_TOLERANCE") "20%")
        (field (name "DB_VOLTAGE") "6.3V")
        (field (name "DB_MANUFACTURER_PART") "KEMET    C1210C107M9PAC")
      )
      (libsource (lib "Database_Libs1") (part "C"))
    )
    (comp (ref "C103")
      (value "C")
      (footprint "SMD_1210_CAPC3225X279N")
      (fields
        (field (name "DB_PART_NUMBER") "CAP000047355")
        (field (name "DB_VALUE") "220uF")
        (field (name "DB_TOLERANCE") "20%")
        (field (name "DB_VOLTAGE") "6.3V")
        (field (name "DB_MANUFACTURER_PART") "SAMSUNG    CL32A227MQVNNNE")
        (field (name "DB_APPROVED_BY") "VSN")
      )
      (libsource (lib "Database_Libs1") (part "C"))
    )
    (comp (ref "C104")
      (value "C")
      (footprint "SMD_1210_CAPC3225X279N")
      (fields
        (field (name "DB_PART_NUMBER") "CAP000047355")
        (field (name "DB_VALUE") "220uF")
        (field (name "DB_TOLERANCE") "20%")
        (field (name "DB_VOLTAGE") "6.3V")
        (field (name "DB_MANUFACTURER_PART") "SAMSUNG    CL32A227MQVNNNE")
        (field (name "DB_APPROVED_BY") "VSN")
      )
      (libsource (lib "Database_Libs1") (part "C"))
    )
    (comp (ref "C105")
      (value "C")
      (footprint "SMD_1210_CAPC3225X279N")
      (fields
        (field (name "DB_PART_NUMBER") "CAP000047355")
        (field (name "DB_VALUE") "220uF")
        (field (name "DB_TOLERANCE") "20%")
        (field (name "DB_VOLTAGE") "6.3V")
        (field (name "DB_MANUFACTURER_PART") "SAMSUNG    CL32A227MQVNNNE")
        (field (name "DB_APPROVED_BY") "VSN")
      )
      (libsource (lib "Database_Libs1") (part "C"))
    )
    (comp (ref "C106")
      (value "C")
      (footprint "SMD_1210_CAPC3225X270N")
      (fields
        (field (name "DB_PART_NUMBER") "CAP000043701")
        (field (name "DB_VALUE") "100uF")
        (field (name "DB_TOLERANCE") "20%")
        (field (name "DB_VOLTAGE") "6.3V")
        (field (name "DB_MANUFACTURER_PART") "KEMET    C1210C107M9PAC")
      )
      (libsource (lib "Database_Libs1") (part "C"))
    )
    (comp (ref "C107")
      (value "C")
      (footprint "SMD_1210_CAPC3225X270N")
      (fields
        (field (name "DB_PART_NUMBER") "CAP000043701")
        (field (name "DB_VALUE") "100uF")
        (field (name "DB_TOLERANCE") "20%")
        (field (name "DB_VOLTAGE") "6.3V")
        (field (name "DB_MANUFACTURER_PART") "KEMET    C1210C107M9PAC")
      )
      (libsource (lib "Database_Libs1") (part "C"))
    )
    (comp (ref "C108")
      (value "C")
      (footprint "SMD_1210_CAPC3225X279N")
      (fields
        (field (name "DB_PART_NUMBER") "CAP000047355")
        (field (name "DB_VALUE") "220uF")
        (field (name "DB_TOLERANCE") "20%")
        (field (name "DB_VOLTAGE") "6.3V")
        (field (name "DB_MANUFACTURER_PART") "SAMSUNG    CL32A227MQVNNNE")
        (field (name "DB_APPROVED_BY") "VSN")
      )
      (libsource (lib "Database_Libs1") (part "C"))
    )
    (comp (ref "C109")
      (value "C")
      (footprint "SMD_1210_CAPC3225X279N")
      (fields
        (field (name "DB_PART_NUMBER") "CAP000047355")
        (field (name "DB_VALUE") "220uF")
        (field (name "DB_TOLERANCE") "20%")
        (field (name "DB_VOLTAGE") "6.3V")
        (field (name "DB_MANUFACTURER_PART") "SAMSUNG    CL32A227MQVNNNE")
        (field (name "DB_APPROVED_BY") "VSN")
      )
      (libsource (lib "Database_Libs1") (part "C"))
    )
    (comp (ref "C110")
      (value "C")
      (footprint "SMD_1210_CAPC3225X279N")
      (fields
        (field (name "DB_PART_NUMBER") "CAP000047355")
        (field (name "DB_VALUE") "220uF")
        (field (name "DB_TOLERANCE") "20%")
        (field (name "DB_VOLTAGE") "6.3V")
        (field (name "DB_MANUFACTURER_PART") "SAMSUNG    CL32A227MQVNNNE")
        (field (name "DB_APPROVED_BY") "VSN")
      )
      (libsource (lib "Database_Libs1") (part "C"))
    )
    (comp (ref "C111")
      (value "C")
      (footprint "SMD_1210_CAPC3225X270N")
      (fields
        (field (name "DB_PART_NUMBER") "CAP000043701")
        (field (name "DB_VALUE") "100uF")
        (field (name "DB_TOLERANCE") "20%")
        (field (name "DB_VOLTAGE") "6.3V")
        (field (name "DB_MANUFACTURER_PART") "KEMET    C1210C107M9PAC")
      )
      (libsource (lib "Database_Libs1") (part "C"))
    )
    (comp (ref "C112")
      (value "C")
      (footprint "SMD_1210_CAPC3225X270N")
      (fields
        (field (name "DB_PART_NUMBER") "CAP000043701")
        (field (name "DB_VALUE") "100uF")
        (field (name "DB_TOLERANCE") "20%")
        (field (name "DB_VOLTAGE") "6.3V")
        (field (name "DB_MANUFACTURER_PART") "KEMET    C1210C107M9PAC")
      )
      (libsource (lib "Database_Libs1") (part "C"))
    )
    (comp (ref "C113")
      (value "C")
      (footprint "SMD_1210_CAPC3225X279N")
      (fields
        (field (name "DB_PART_NUMBER") "CAP000047355")
        (field (name "DB_VALUE") "220uF")
        (field (name "DB_TOLERANCE") "20%")
        (field (name "DB_VOLTAGE") "6.3V")
        (field (name "DB_MANUFACTURER_PART") "SAMSUNG    CL32A227MQVNNNE")
        (field (name "DB_APPROVED_BY") "VSN")
      )
      (libsource (lib "Database_Libs1") (part "C"))
    )
    (comp (ref "C114")
      (value "C")
      (footprint "SMD_1210_CAPC3225X279N")
      (fields
        (field (name "DB_PART_NUMBER") "CAP000047355")
        (field (name "DB_VALUE") "220uF")
        (field (name "DB_TOLERANCE") "20%")
        (field (name "DB_VOLTAGE") "6.3V")
        (field (name "DB_MANUFACTURER_PART") "SAMSUNG    CL32A227MQVNNNE")
        (field (name "DB_APPROVED_BY") "VSN")
      )
      (libsource (lib "Database_Libs1") (part "C"))
    )
    (comp (ref "C115")
      (value "C")
      (footprint "SMD_1210_CAPC3225X279N")
      (fields
        (field (name "DB_PART_NUMBER") "CAP000047355")
        (field (name "DB_VALUE") "220uF")
        (field (name "DB_TOLERANCE") "20%")
        (field (name "DB_VOLTAGE") "6.3V")
        (field (name "DB_MANUFACTURER_PART") "SAMSUNG    CL32A227MQVNNNE")
        (field (name "DB_APPROVED_BY") "VSN")
      )
      (libsource (lib "Database_Libs1") (part "C"))
    )
    (comp (ref "C116")
      (value "C")
      (footprint "SMD_0603_CAPC1608X95N")
      (fields
        (field (name "DB_PART_NUMBER") "CAP000043646")
        (field (name "DB_VALUE") "10uF")
        (field (name "DB_TOLERANCE") "20%")
        (field (name "DB_VOLTAGE") "6.3V")
        (field (name "DB_MANUFACTURER_PART") "KEMET    C0603C106M9PAC")
      )
      (libsource (lib "Database_Libs1") (part "C"))
    )
    (comp (ref "C117")
      (value "C")
      (footprint "SMD_0603_CAPC1608X95N")
      (fields
        (field (name "DB_PART_NUMBER") "CAP000043646")
        (field (name "DB_VALUE") "10uF")
        (field (name "DB_TOLERANCE") "20%")
        (field (name "DB_VOLTAGE") "6.3V")
        (field (name "DB_MANUFACTURER_PART") "KEMET    C0603C106M9PAC")
      )
      (libsource (lib "Database_Libs1") (part "C"))
    )
    (comp (ref "C118")
      (value "C")
      (footprint "SMD_0603_CAPC1608X95N")
      (fields
        (field (name "DB_PART_NUMBER") "CAP000043646")
        (field (name "DB_VALUE") "10uF")
        (field (name "DB_TOLERANCE") "20%")
        (field (name "DB_VOLTAGE") "6.3V")
        (field (name "DB_MANUFACTURER_PART") "KEMET    C0603C106M9PAC")
      )
      (libsource (lib "Database_Libs1") (part "C"))
    )
    (comp (ref "C119")
      (value "C")
      (footprint "SMD_0603_CAPC1608X95N")
      (fields
        (field (name "DB_PART_NUMBER") "CAP000043646")
        (field (name "DB_VALUE") "10uF")
        (field (name "DB_TOLERANCE") "20%")
        (field (name "DB_VOLTAGE") "6.3V")
        (field (name "DB_MANUFACTURER_PART") "KEMET    C0603C106M9PAC")
      )
      (libsource (lib "Database_Libs1") (part "C"))
    )
    (comp (ref "C120")
      (value "C")
      (footprint "SMD_0402_CAPC1005X55N")
      (fields
        (field (name "DB_PART_NUMBER") "CAP000022751")
        (field (name "DB_VALUE") "100nF")
        (field (name "DB_TOLERANCE") "20%")
        (field (name "DB_VOLTAGE") "16V")
        (field (name "DB_MANUFACTURER_PART") "KEMET    C0402F104M4RAC")
      )
      (libsource (lib "Database_Libs1") (part "C"))
    )
    (comp (ref "C121")
      (value "C")
      (footprint "SMD_0402_CAPC1005X55N")
      (fields
        (field (name "DB_PART_NUMBER") "CAP000022751")
        (field (name "DB_VALUE") "100nF")
        (field (name "DB_TOLERANCE") "20%")
        (field (name "DB_VOLTAGE") "16V")
        (field (name "DB_MANUFACTURER_PART") "KEMET    C0402F104M4RAC")
      )
      (libsource (lib "Database_Libs1") (part "C"))
    )
    (comp (ref "C122")
      (value "C")
      (footprint "SMD_0402_CAPC1005X55N")
      (fields
        (field (name "DB_PART_NUMBER") "CAP000022751")
        (field (name "DB_VALUE") "100nF")
        (field (name "DB_TOLERANCE") "20%")
        (field (name "DB_VOLTAGE") "16V")
        (field (name "DB_MANUFACTURER_PART") "KEMET    C0402F104M4RAC")
      )
      (libsource (lib "Database_Libs1") (part "C"))
    )
    (comp (ref "C123")
      (value "C")
      (footprint "SMD_0402_CAPC1005X55N")
      (fields
        (field (name "DB_PART_NUMBER") "CAP000022751")
        (field (name "DB_VALUE") "100nF")
        (field (name "DB_TOLERANCE") "20%")
        (field (name "DB_VOLTAGE") "16V")
        (field (name "DB_MANUFACTURER_PART") "KEMET    C0402F104M4RAC")
      )
      (libsource (lib "Database_Libs1") (part "C"))
    )
    (comp (ref "C124")
      (value "C")
      (footprint "SMD_0603_CAPC1608X95N")
      (fields
        (field (name "DB_PART_NUMBER") "CAP000022968")
        (field (name "DB_VALUE") "220nF")
        (field (name "DB_TOLERANCE") "10%")
        (field (name "DB_VOLTAGE") "25V")
        (field (name "DB_MANUFACTURER_PART") "KEMET    C0603F224K3RAC")
      )
      (libsource (lib "Database_Libs1") (part "C"))
    )
    (comp (ref "C125")
      (value "C")
      (footprint "SMD_0603_CAPC1608X95N")
      (fields
        (field (name "DB_PART_NUMBER") "CAP000022968")
        (field (name "DB_VALUE") "220nF")
        (field (name "DB_TOLERANCE") "10%")
        (field (name "DB_VOLTAGE") "25V")
        (field (name "DB_MANUFACTURER_PART") "KEMET    C0603F224K3RAC")
      )
      (libsource (lib "Database_Libs1") (part "C"))
    )
    (comp (ref "C126")
      (value "C")
      (footprint "SMD_0603_CAPC1608X95N")
      (fields
        (field (name "DB_PART_NUMBER") "CAP000022968")
        (field (name "DB_VALUE") "220nF")
        (field (name "DB_TOLERANCE") "10%")
        (field (name "DB_VOLTAGE") "25V")
        (field (name "DB_MANUFACTURER_PART") "KEMET    C0603F224K3RAC")
      )
      (libsource (lib "Database_Libs1") (part "C"))
    )
    (comp (ref "C127")
      (value "C")
      (footprint "SMD_0603_CAPC1608X95N")
      (fields
        (field (name "DB_PART_NUMBER") "CAP000022968")
        (field (name "DB_VALUE") "220nF")
        (field (name "DB_TOLERANCE") "10%")
        (field (name "DB_VOLTAGE") "25V")
        (field (name "DB_MANUFACTURER_PART") "KEMET    C0603F224K3RAC")
      )
      (libsource (lib "Database_Libs1") (part "C"))
    )
    (comp (ref "C128")
      (value "C")
      (footprint "SMD_1210_CAPC3225X270N")
      (fields
        (field (name "DB_PART_NUMBER") "CAP000043701")
        (field (name "DB_VALUE") "100uF")
        (field (name "DB_TOLERANCE") "20%")
        (field (name "DB_VOLTAGE") "6.3V")
        (field (name "DB_MANUFACTURER_PART") "KEMET    C1210C107M9PAC")
      )
      (libsource (lib "Database_Libs1") (part "C"))
    )
    (comp (ref "C129")
      (value "C")
      (footprint "SMD_1210_CAPC3225X270N")
      (fields
        (field (name "DB_PART_NUMBER") "CAP000043701")
        (field (name "DB_VALUE") "100uF")
        (field (name "DB_TOLERANCE") "20%")
        (field (name "DB_VOLTAGE") "6.3V")
        (field (name "DB_MANUFACTURER_PART") "KEMET    C1210C107M9PAC")
      )
      (libsource (lib "Database_Libs1") (part "C"))
    )
    (comp (ref "C130")
      (value "C")
      (footprint "SMD_1210_CAPC3225X279N")
      (fields
        (field (name "DB_PART_NUMBER") "CAP000047355")
        (field (name "DB_VALUE") "220uF")
        (field (name "DB_TOLERANCE") "20%")
        (field (name "DB_VOLTAGE") "6.3V")
        (field (name "DB_MANUFACTURER_PART") "SAMSUNG    CL32A227MQVNNNE")
        (field (name "DB_APPROVED_BY") "VSN")
      )
      (libsource (lib "Database_Libs1") (part "C"))
    )
    (comp (ref "C131")
      (value "C")
      (footprint "SMD_1210_CAPC3225X279N")
      (fields
        (field (name "DB_PART_NUMBER") "CAP000047355")
        (field (name "DB_VALUE") "220uF")
        (field (name "DB_TOLERANCE") "20%")
        (field (name "DB_VOLTAGE") "6.3V")
        (field (name "DB_MANUFACTURER_PART") "SAMSUNG    CL32A227MQVNNNE")
        (field (name "DB_APPROVED_BY") "VSN")
      )
      (libsource (lib "Database_Libs1") (part "C"))
    )
    (comp (ref "C132")
      (value "C")
      (footprint "SMD_1210_CAPC3225X279N")
      (fields
        (field (name "DB_PART_NUMBER") "CAP000047355")
        (field (name "DB_VALUE") "220uF")
        (field (name "DB_TOLERANCE") "20%")
        (field (name "DB_VOLTAGE") "6.3V")
        (field (name "DB_MANUFACTURER_PART") "SAMSUNG    CL32A227MQVNNNE")
        (field (name "DB_APPROVED_BY") "VSN")
      )
      (libsource (lib "Database_Libs1") (part "C"))
    )
    (comp (ref "C133")
      (value "C")
      (footprint "SMD_1210_CAPC3225X270N")
      (fields
        (field (name "DB_PART_NUMBER") "CAP000043701")
        (field (name "DB_VALUE") "100uF")
        (field (name "DB_TOLERANCE") "20%")
        (field (name "DB_VOLTAGE") "6.3V")
        (field (name "DB_MANUFACTURER_PART") "KEMET    C1210C107M9PAC")
      )
      (libsource (lib "Database_Libs1") (part "C"))
    )
    (comp (ref "C134")
      (value "C")
      (footprint "SMD_1210_CAPC3225X270N")
      (fields
        (field (name "DB_PART_NUMBER") "CAP000043701")
        (field (name "DB_VALUE") "100uF")
        (field (name "DB_TOLERANCE") "20%")
        (field (name "DB_VOLTAGE") "6.3V")
        (field (name "DB_MANUFACTURER_PART") "KEMET    C1210C107M9PAC")
      )
      (libsource (lib "Database_Libs1") (part "C"))
    )
    (comp (ref "C135")
      (value "C")
      (footprint "SMD_1210_CAPC3225X279N")
      (fields
        (field (name "DB_PART_NUMBER") "CAP000047355")
        (field (name "DB_VALUE") "220uF")
        (field (name "DB_TOLERANCE") "20%")
        (field (name "DB_VOLTAGE") "6.3V")
        (field (name "DB_MANUFACTURER_PART") "SAMSUNG    CL32A227MQVNNNE")
        (field (name "DB_APPROVED_BY") "VSN")
      )
      (libsource (lib "Database_Libs1") (part "C"))
    )
    (comp (ref "C136")
      (value "C")
      (footprint "SMD_1210_CAPC3225X279N")
      (fields
        (field (name "DB_PART_NUMBER") "CAP000047355")
        (field (name "DB_VALUE") "220uF")
        (field (name "DB_TOLERANCE") "20%")
        (field (name "DB_VOLTAGE") "6.3V")
        (field (name "DB_MANUFACTURER_PART") "SAMSUNG    CL32A227MQVNNNE")
        (field (name "DB_APPROVED_BY") "VSN")
      )
      (libsource (lib "Database_Libs1") (part "C"))
    )
    (comp (ref "C137")
      (value "C")
      (footprint "SMD_1210_CAPC3225X279N")
      (fields
        (field (name "DB_PART_NUMBER") "CAP000047355")
        (field (name "DB_VALUE") "220uF")
        (field (name "DB_TOLERANCE") "20%")
        (field (name "DB_VOLTAGE") "6.3V")
        (field (name "DB_MANUFACTURER_PART") "SAMSUNG    CL32A227MQVNNNE")
        (field (name "DB_APPROVED_BY") "VSN")
      )
      (libsource (lib "Database_Libs1") (part "C"))
    )
    (comp (ref "C138")
      (value "C")
      (footprint "SMD_1210_CAPC3225X270N")
      (fields
        (field (name "DB_PART_NUMBER") "CAP000043701")
        (field (name "DB_VALUE") "100uF")
        (field (name "DB_TOLERANCE") "20%")
        (field (name "DB_VOLTAGE") "6.3V")
        (field (name "DB_MANUFACTURER_PART") "KEMET    C1210C107M9PAC")
      )
      (libsource (lib "Database_Libs1") (part "C"))
    )
    (comp (ref "C139")
      (value "C")
      (footprint "SMD_1210_CAPC3225X270N")
      (fields
        (field (name "DB_PART_NUMBER") "CAP000043701")
        (field (name "DB_VALUE") "100uF")
        (field (name "DB_TOLERANCE") "20%")
        (field (name "DB_VOLTAGE") "6.3V")
        (field (name "DB_MANUFACTURER_PART") "KEMET    C1210C107M9PAC")
      )
      (libsource (lib "Database_Libs1") (part "C"))
    )
    (comp (ref "C140")
      (value "C")
      (footprint "SMD_1210_CAPC3225X279N")
      (fields
        (field (name "DB_PART_NUMBER") "CAP000047355")
        (field (name "DB_VALUE") "220uF")
        (field (name "DB_TOLERANCE") "20%")
        (field (name "DB_VOLTAGE") "6.3V")
        (field (name "DB_MANUFACTURER_PART") "SAMSUNG    CL32A227MQVNNNE")
        (field (name "DB_APPROVED_BY") "VSN")
      )
      (libsource (lib "Database_Libs1") (part "C"))
    )
    (comp (ref "C141")
      (value "C")
      (footprint "SMD_1210_CAPC3225X279N")
      (fields
        (field (name "DB_PART_NUMBER") "CAP000047355")
        (field (name "DB_VALUE") "220uF")
        (field (name "DB_TOLERANCE") "20%")
        (field (name "DB_VOLTAGE") "6.3V")
        (field (name "DB_MANUFACTURER_PART") "SAMSUNG    CL32A227MQVNNNE")
        (field (name "DB_APPROVED_BY") "VSN")
      )
      (libsource (lib "Database_Libs1") (part "C"))
    )
    (comp (ref "C142")
      (value "C")
      (footprint "SMD_1210_CAPC3225X279N")
      (fields
        (field (name "DB_PART_NUMBER") "CAP000047355")
        (field (name "DB_VALUE") "220uF")
        (field (name "DB_TOLERANCE") "20%")
        (field (name "DB_VOLTAGE") "6.3V")
        (field (name "DB_MANUFACTURER_PART") "SAMSUNG    CL32A227MQVNNNE")
        (field (name "DB_APPROVED_BY") "VSN")
      )
      (libsource (lib "Database_Libs1") (part "C"))
    )
    (comp (ref "C143")
      (value "C")
      (footprint "SMD_1210_CAPC3225X270N")
      (fields
        (field (name "DB_PART_NUMBER") "CAP000043701")
        (field (name "DB_VALUE") "100uF")
        (field (name "DB_TOLERANCE") "20%")
        (field (name "DB_VOLTAGE") "6.3V")
        (field (name "DB_MANUFACTURER_PART") "KEMET    C1210C107M9PAC")
      )
      (libsource (lib "Database_Libs1") (part "C"))
    )
    (comp (ref "C144")
      (value "C")
      (footprint "SMD_1210_CAPC3225X270N")
      (fields
        (field (name "DB_PART_NUMBER") "CAP000043701")
        (field (name "DB_VALUE") "100uF")
        (field (name "DB_TOLERANCE") "20%")
        (field (name "DB_VOLTAGE") "6.3V")
        (field (name "DB_MANUFACTURER_PART") "KEMET    C1210C107M9PAC")
      )
      (libsource (lib "Database_Libs1") (part "C"))
    )
    (comp (ref "C145")
      (value "C")
      (footprint "SMD_1210_CAPC3225X279N")
      (fields
        (field (name "DB_PART_NUMBER") "CAP000047355")
        (field (name "DB_VALUE") "220uF")
        (field (name "DB_TOLERANCE") "20%")
        (field (name "DB_VOLTAGE") "6.3V")
        (field (name "DB_MANUFACTURER_PART") "SAMSUNG    CL32A227MQVNNNE")
        (field (name "DB_APPROVED_BY") "VSN")
      )
      (libsource (lib "Database_Libs1") (part "C"))
    )
    (comp (ref "C146")
      (value "C")
      (footprint "SMD_1210_CAPC3225X279N")
      (fields
        (field (name "DB_PART_NUMBER") "CAP000047355")
        (field (name "DB_VALUE") "220uF")
        (field (name "DB_TOLERANCE") "20%")
        (field (name "DB_VOLTAGE") "6.3V")
        (field (name "DB_MANUFACTURER_PART") "SAMSUNG    CL32A227MQVNNNE")
        (field (name "DB_APPROVED_BY") "VSN")
      )
      (libsource (lib "Database_Libs1") (part "C"))
    )
    (comp (ref "C147")
      (value "C")
      (footprint "SMD_1210_CAPC3225X279N")
      (fields
        (field (name "DB_PART_NUMBER") "CAP000047355")
        (field (name "DB_VALUE") "220uF")
        (field (name "DB_TOLERANCE") "20%")
        (field (name "DB_VOLTAGE") "6.3V")
        (field (name "DB_MANUFACTURER_PART") "SAMSUNG    CL32A227MQVNNNE")
        (field (name "DB_APPROVED_BY") "VSN")
      )
      (libsource (lib "Database_Libs1") (part "C"))
    )
    (comp (ref "C236")
      (value "C")
      (footprint "SMD_1210_CAPC3225X279N")
      (fields
        (field (name "DB_PART_NUMBER") "CAP000047355")
        (field (name "DB_VALUE") "220uF")
        (field (name "DB_TOLERANCE") "20%")
        (field (name "DB_VOLTAGE") "6.3V")
        (field (name "DB_MANUFACTURER_PART") "SAMSUNG    CL32A227MQVNNNE")
        (field (name "DB_APPROVED_BY") "VSN")
      )
      (libsource (lib "Database_Libs1") (part "C"))
    )
    (comp (ref "C348")
      (value "C")
      (footprint "SMD_1210_CAPC3225X270N")
      (fields
        (field (name "DB_PART_NUMBER") "CAP000043701")
        (field (name "DB_VALUE") "100uF")
        (field (name "DB_TOLERANCE") "20%")
        (field (name "DB_VOLTAGE") "6.3V")
        (field (name "DB_MANUFACTURER_PART") "KEMET    C1210C107M9PAC")
      )
      (libsource (lib "Database_Libs1") (part "C"))
    )
    (comp (ref "C349")
      (value "C")
      (footprint "SMD_1210_CAPC3225X270N")
      (fields
        (field (name "DB_PART_NUMBER") "CAP000043701")
        (field (name "DB_VALUE") "100uF")
        (field (name "DB_TOLERANCE") "20%")
        (field (name "DB_VOLTAGE") "6.3V")
        (field (name "DB_MANUFACTURER_PART") "KEMET    C1210C107M9PAC")
      )
      (libsource (lib "Database_Libs1") (part "C"))
    )
    (comp (ref "C350")
      (value "C")
      (footprint "SMD_1210_CAPC3225X279N")
      (fields
        (field (name "DB_PART_NUMBER") "CAP000047355")
        (field (name "DB_VALUE") "220uF")
        (field (name "DB_TOLERANCE") "20%")
        (field (name "DB_VOLTAGE") "6.3V")
        (field (name "DB_MANUFACTURER_PART") "SAMSUNG    CL32A227MQVNNNE")
        (field (name "DB_APPROVED_BY") "VSN")
      )
      (libsource (lib "Database_Libs1") (part "C"))
    )
    (comp (ref "C351")
      (value "C")
      (footprint "SMD_1210_CAPC3225X279N")
      (fields
        (field (name "DB_PART_NUMBER") "CAP000047355")
        (field (name "DB_VALUE") "220uF")
        (field (name "DB_TOLERANCE") "20%")
        (field (name "DB_VOLTAGE") "6.3V")
        (field (name "DB_MANUFACTURER_PART") "SAMSUNG    CL32A227MQVNNNE")
        (field (name "DB_APPROVED_BY") "VSN")
      )
      (libsource (lib "Database_Libs1") (part "C"))
    )
    (comp (ref "C352")
      (value "C")
      (footprint "SMD_1210_CAPC3225X279N")
      (fields
        (field (name "DB_PART_NUMBER") "CAP000047355")
        (field (name "DB_VALUE") "220uF")
        (field (name "DB_TOLERANCE") "20%")
        (field (name "DB_VOLTAGE") "6.3V")
        (field (name "DB_MANUFACTURER_PART") "SAMSUNG    CL32A227MQVNNNE")
        (field (name "DB_APPROVED_BY") "VSN")
      )
      (libsource (lib "Database_Libs1") (part "C"))
    )
    (comp (ref "C353")
      (value "C")
      (footprint "SMD_1210_CAPC3225X270N")
      (fields
        (field (name "DB_PART_NUMBER") "CAP000043701")
        (field (name "DB_VALUE") "100uF")
        (field (name "DB_TOLERANCE") "20%")
        (field (name "DB_VOLTAGE") "6.3V")
        (field (name "DB_MANUFACTURER_PART") "KEMET    C1210C107M9PAC")
      )
      (libsource (lib "Database_Libs1") (part "C"))
    )
    (comp (ref "C354")
      (value "C")
      (footprint "SMD_1210_CAPC3225X270N")
      (fields
        (field (name "DB_PART_NUMBER") "CAP000043701")
        (field (name "DB_VALUE") "100uF")
        (field (name "DB_TOLERANCE") "20%")
        (field (name "DB_VOLTAGE") "6.3V")
        (field (name "DB_MANUFACTURER_PART") "KEMET    C1210C107M9PAC")
      )
      (libsource (lib "Database_Libs1") (part "C"))
    )
    (comp (ref "C355")
      (value "C")
      (footprint "SMD_1210_CAPC3225X279N")
      (fields
        (field (name "DB_PART_NUMBER") "CAP000047355")
        (field (name "DB_VALUE") "220uF")
        (field (name "DB_TOLERANCE") "20%")
        (field (name "DB_VOLTAGE") "6.3V")
        (field (name "DB_MANUFACTURER_PART") "SAMSUNG    CL32A227MQVNNNE")
        (field (name "DB_APPROVED_BY") "VSN")
      )
      (libsource (lib "Database_Libs1") (part "C"))
    )
    (comp (ref "C356")
      (value "C")
      (footprint "SMD_1210_CAPC3225X279N")
      (fields
        (field (name "DB_PART_NUMBER") "CAP000047355")
        (field (name "DB_VALUE") "220uF")
        (field (name "DB_TOLERANCE") "20%")
        (field (name "DB_VOLTAGE") "6.3V")
        (field (name "DB_MANUFACTURER_PART") "SAMSUNG    CL32A227MQVNNNE")
        (field (name "DB_APPROVED_BY") "VSN")
      )
      (libsource (lib "Database_Libs1") (part "C"))
    )
    (comp (ref "C357")
      (value "C")
      (footprint "SMD_1210_CAPC3225X279N")
      (fields
        (field (name "DB_PART_NUMBER") "CAP000047355")
        (field (name "DB_VALUE") "220uF")
        (field (name "DB_TOLERANCE") "20%")
        (field (name "DB_VOLTAGE") "6.3V")
        (field (name "DB_MANUFACTURER_PART") "SAMSUNG    CL32A227MQVNNNE")
        (field (name "DB_APPROVED_BY") "VSN")
      )
      (libsource (lib "Database_Libs1") (part "C"))
    )
    (comp (ref "C358")
      (value "C")
      (footprint "SMD_1210_CAPC3225X270N")
      (fields
        (field (name "DB_PART_NUMBER") "CAP000043701")
        (field (name "DB_VALUE") "100uF")
        (field (name "DB_TOLERANCE") "20%")
        (field (name "DB_VOLTAGE") "6.3V")
        (field (name "DB_MANUFACTURER_PART") "KEMET    C1210C107M9PAC")
      )
      (libsource (lib "Database_Libs1") (part "C"))
    )
    (comp (ref "C359")
      (value "C")
      (footprint "SMD_1210_CAPC3225X270N")
      (fields
        (field (name "DB_PART_NUMBER") "CAP000043701")
        (field (name "DB_VALUE") "100uF")
        (field (name "DB_TOLERANCE") "20%")
        (field (name "DB_VOLTAGE") "6.3V")
        (field (name "DB_MANUFACTURER_PART") "KEMET    C1210C107M9PAC")
      )
      (libsource (lib "Database_Libs1") (part "C"))
    )
    (comp (ref "C360")
      (value "C")
      (footprint "SMD_1210_CAPC3225X279N")
      (fields
        (field (name "DB_PART_NUMBER") "CAP000047355")
        (field (name "DB_VALUE") "220uF")
        (field (name "DB_TOLERANCE") "20%")
        (field (name "DB_VOLTAGE") "6.3V")
        (field (name "DB_MANUFACTURER_PART") "SAMSUNG    CL32A227MQVNNNE")
        (field (name "DB_APPROVED_BY") "VSN")
      )
      (libsource (lib "Database_Libs1") (part "C"))
    )
    (comp (ref "C361")
      (value "C")
      (footprint "SMD_1210_CAPC3225X279N")
      (fields
        (field (name "DB_PART_NUMBER") "CAP000047355")
        (field (name "DB_VALUE") "220uF")
        (field (name "DB_TOLERANCE") "20%")
        (field (name "DB_VOLTAGE") "6.3V")
        (field (name "DB_MANUFACTURER_PART") "SAMSUNG    CL32A227MQVNNNE")
        (field (name "DB_APPROVED_BY") "VSN")
      )
      (libsource (lib "Database_Libs1") (part "C"))
    )
    (comp (ref "C362")
      (value "C")
      (footprint "SMD_1210_CAPC3225X279N")
      (fields
        (field (name "DB_PART_NUMBER") "CAP000047355")
        (field (name "DB_VALUE") "220uF")
        (field (name "DB_TOLERANCE") "20%")
        (field (name "DB_VOLTAGE") "6.3V")
        (field (name "DB_MANUFACTURER_PART") "SAMSUNG    CL32A227MQVNNNE")
        (field (name "DB_APPROVED_BY") "VSN")
      )
      (libsource (lib "Database_Libs1") (part "C"))
    )
    (comp (ref "C363")
      (value "C")
      (footprint "SMD_1210_CAPC3225X270N")
      (fields
        (field (name "DB_PART_NUMBER") "CAP000043701")
        (field (name "DB_VALUE") "100uF")
        (field (name "DB_TOLERANCE") "20%")
        (field (name "DB_VOLTAGE") "6.3V")
        (field (name "DB_MANUFACTURER_PART") "KEMET    C1210C107M9PAC")
      )
      (libsource (lib "Database_Libs1") (part "C"))
    )
    (comp (ref "C364")
      (value "C")
      (footprint "SMD_1210_CAPC3225X270N")
      (fields
        (field (name "DB_PART_NUMBER") "CAP000043701")
        (field (name "DB_VALUE") "100uF")
        (field (name "DB_TOLERANCE") "20%")
        (field (name "DB_VOLTAGE") "6.3V")
        (field (name "DB_MANUFACTURER_PART") "KEMET    C1210C107M9PAC")
      )
      (libsource (lib "Database_Libs1") (part "C"))
    )
    (comp (ref "C365")
      (value "C")
      (footprint "SMD_1210_CAPC3225X279N")
      (fields
        (field (name "DB_PART_NUMBER") "CAP000047355")
        (field (name "DB_VALUE") "220uF")
        (field (name "DB_TOLERANCE") "20%")
        (field (name "DB_VOLTAGE") "6.3V")
        (field (name "DB_MANUFACTURER_PART") "SAMSUNG    CL32A227MQVNNNE")
        (field (name "DB_APPROVED_BY") "VSN")
      )
      (libsource (lib "Database_Libs1") (part "C"))
    )
    (comp (ref "C366")
      (value "C")
      (footprint "SMD_1210_CAPC3225X279N")
      (fields
        (field (name "DB_PART_NUMBER") "CAP000047355")
        (field (name "DB_VALUE") "220uF")
        (field (name "DB_TOLERANCE") "20%")
        (field (name "DB_VOLTAGE") "6.3V")
        (field (name "DB_MANUFACTURER_PART") "SAMSUNG    CL32A227MQVNNNE")
        (field (name "DB_APPROVED_BY") "VSN")
      )
      (libsource (lib "Database_Libs1") (part "C"))
    )
    (comp (ref "C367")
      (value "C")
      (footprint "SMD_1210_CAPC3225X279N")
      (fields
        (field (name "DB_PART_NUMBER") "CAP000047355")
        (field (name "DB_VALUE") "220uF")
        (field (name "DB_TOLERANCE") "20%")
        (field (name "DB_VOLTAGE") "6.3V")
        (field (name "DB_MANUFACTURER_PART") "SAMSUNG    CL32A227MQVNNNE")
        (field (name "DB_APPROVED_BY") "VSN")
      )
      (libsource (lib "Database_Libs1") (part "C"))
    )
    (comp (ref "C368")
      (value "C")
      (footprint "SMD_1210_CAPC3225X270N")
      (fields
        (field (name "DB_PART_NUMBER") "CAP000043701")
        (field (name "DB_VALUE") "100uF")
        (field (name "DB_TOLERANCE") "20%")
        (field (name "DB_VOLTAGE") "6.3V")
        (field (name "DB_MANUFACTURER_PART") "KEMET    C1210C107M9PAC")
      )
      (libsource (lib "Database_Libs1") (part "C"))
    )
    (comp (ref "C369")
      (value "C")
      (footprint "SMD_1210_CAPC3225X270N")
      (fields
        (field (name "DB_PART_NUMBER") "CAP000043701")
        (field (name "DB_VALUE") "100uF")
        (field (name "DB_TOLERANCE") "20%")
        (field (name "DB_VOLTAGE") "6.3V")
        (field (name "DB_MANUFACTURER_PART") "KEMET    C1210C107M9PAC")
      )
      (libsource (lib "Database_Libs1") (part "C"))
    )
    (comp (ref "C370")
      (value "C")
      (footprint "SMD_1210_CAPC3225X279N")
      (fields
        (field (name "DB_PART_NUMBER") "CAP000047355")
        (field (name "DB_VALUE") "220uF")
        (field (name "DB_TOLERANCE") "20%")
        (field (name "DB_VOLTAGE") "6.3V")
        (field (name "DB_MANUFACTURER_PART") "SAMSUNG    CL32A227MQVNNNE")
        (field (name "DB_APPROVED_BY") "VSN")
      )
      (libsource (lib "Database_Libs1") (part "C"))
    )
    (comp (ref "C371")
      (value "C")
      (footprint "SMD_1210_CAPC3225X279N")
      (fields
        (field (name "DB_PART_NUMBER") "CAP000047355")
        (field (name "DB_VALUE") "220uF")
        (field (name "DB_TOLERANCE") "20%")
        (field (name "DB_VOLTAGE") "6.3V")
        (field (name "DB_MANUFACTURER_PART") "SAMSUNG    CL32A227MQVNNNE")
        (field (name "DB_APPROVED_BY") "VSN")
      )
      (libsource (lib "Database_Libs1") (part "C"))
    )
    (comp (ref "C372")
      (value "C")
      (footprint "SMD_1210_CAPC3225X279N")
      (fields
        (field (name "DB_PART_NUMBER") "CAP000047355")
        (field (name "DB_VALUE") "220uF")
        (field (name "DB_TOLERANCE") "20%")
        (field (name "DB_VOLTAGE") "6.3V")
        (field (name "DB_MANUFACTURER_PART") "SAMSUNG    CL32A227MQVNNNE")
        (field (name "DB_APPROVED_BY") "VSN")
      )
      (libsource (lib "Database_Libs1") (part "C"))
    )
    (comp (ref "C373")
      (value "C")
      (footprint "SMD_1210_CAPC3225X270N")
      (fields
        (field (name "DB_PART_NUMBER") "CAP000043701")
        (field (name "DB_VALUE") "100uF")
        (field (name "DB_TOLERANCE") "20%")
        (field (name "DB_VOLTAGE") "6.3V")
        (field (name "DB_MANUFACTURER_PART") "KEMET    C1210C107M9PAC")
      )
      (libsource (lib "Database_Libs1") (part "C"))
    )
    (comp (ref "C374")
      (value "C")
      (footprint "SMD_1210_CAPC3225X270N")
      (fields
        (field (name "DB_PART_NUMBER") "CAP000043701")
        (field (name "DB_VALUE") "100uF")
        (field (name "DB_TOLERANCE") "20%")
        (field (name "DB_VOLTAGE") "6.3V")
        (field (name "DB_MANUFACTURER_PART") "KEMET    C1210C107M9PAC")
      )
      (libsource (lib "Database_Libs1") (part "C"))
    )
    (comp (ref "C375")
      (value "C")
      (footprint "SMD_1210_CAPC3225X279N")
      (fields
        (field (name "DB_PART_NUMBER") "CAP000047355")
        (field (name "DB_VALUE") "220uF")
        (field (name "DB_TOLERANCE") "20%")
        (field (name "DB_VOLTAGE") "6.3V")
        (field (name "DB_MANUFACTURER_PART") "SAMSUNG    CL32A227MQVNNNE")
        (field (name "DB_APPROVED_BY") "VSN")
      )
      (libsource (lib "Database_Libs1") (part "C"))
    )
    (comp (ref "C376")
      (value "C")
      (footprint "SMD_1210_CAPC3225X279N")
      (fields
        (field (name "DB_PART_NUMBER") "CAP000047355")
        (field (name "DB_VALUE") "220uF")
        (field (name "DB_TOLERANCE") "20%")
        (field (name "DB_VOLTAGE") "6.3V")
        (field (name "DB_MANUFACTURER_PART") "SAMSUNG    CL32A227MQVNNNE")
        (field (name "DB_APPROVED_BY") "VSN")
      )
      (libsource (lib "Database_Libs1") (part "C"))
    )
    (comp (ref "C377")
      (value "C")
      (footprint "SMD_1210_CAPC3225X279N")
      (fields
        (field (name "DB_PART_NUMBER") "CAP000047355")
        (field (name "DB_VALUE") "220uF")
        (field (name "DB_TOLERANCE") "20%")
        (field (name "DB_VOLTAGE") "6.3V")
        (field (name "DB_MANUFACTURER_PART") "SAMSUNG    CL32A227MQVNNNE")
        (field (name "DB_APPROVED_BY") "VSN")
      )
      (libsource (lib "Database_Libs1") (part "C"))
    )
    (comp (ref "C378")
      (value "C")
      (footprint "SMD_1210_CAPC3225X270N")
      (fields
        (field (name "DB_PART_NUMBER") "CAP000043701")
        (field (name "DB_VALUE") "100uF")
        (field (name "DB_TOLERANCE") "20%")
        (field (name "DB_VOLTAGE") "6.3V")
        (field (name "DB_MANUFACTURER_PART") "KEMET    C1210C107M9PAC")
      )
      (libsource (lib "Database_Libs1") (part "C"))
    )
    (comp (ref "C379")
      (value "C")
      (footprint "SMD_1210_CAPC3225X270N")
      (fields
        (field (name "DB_PART_NUMBER") "CAP000043701")
        (field (name "DB_VALUE") "100uF")
        (field (name "DB_TOLERANCE") "20%")
        (field (name "DB_VOLTAGE") "6.3V")
        (field (name "DB_MANUFACTURER_PART") "KEMET    C1210C107M9PAC")
      )
      (libsource (lib "Database_Libs1") (part "C"))
    )
    (comp (ref "C380")
      (value "C")
      (footprint "SMD_1210_CAPC3225X279N")
      (fields
        (field (name "DB_PART_NUMBER") "CAP000047355")
        (field (name "DB_VALUE") "220uF")
        (field (name "DB_TOLERANCE") "20%")
        (field (name "DB_VOLTAGE") "6.3V")
        (field (name "DB_MANUFACTURER_PART") "SAMSUNG    CL32A227MQVNNNE")
        (field (name "DB_APPROVED_BY") "VSN")
      )
      (libsource (lib "Database_Libs1") (part "C"))
    )
    (comp (ref "C381")
      (value "C")
      (footprint "SMD_1210_CAPC3225X279N")
      (fields
        (field (name "DB_PART_NUMBER") "CAP000047355")
        (field (name "DB_VALUE") "220uF")
        (field (name "DB_TOLERANCE") "20%")
        (field (name "DB_VOLTAGE") "6.3V")
        (field (name "DB_MANUFACTURER_PART") "SAMSUNG    CL32A227MQVNNNE")
        (field (name "DB_APPROVED_BY") "VSN")
      )
      (libsource (lib "Database_Libs1") (part "C"))
    )
    (comp (ref "C382")
      (value "C")
      (footprint "SMD_1210_CAPC3225X279N")
      (fields
        (field (name "DB_PART_NUMBER") "CAP000047355")
        (field (name "DB_VALUE") "220uF")
        (field (name "DB_TOLERANCE") "20%")
        (field (name "DB_VOLTAGE") "6.3V")
        (field (name "DB_MANUFACTURER_PART") "SAMSUNG    CL32A227MQVNNNE")
        (field (name "DB_APPROVED_BY") "VSN")
      )
      (libsource (lib "Database_Libs1") (part "C"))
    )
    (comp (ref "C383")
      (value "C")
      (footprint "SMD_1210_CAPC3225X270N")
      (fields
        (field (name "DB_PART_NUMBER") "CAP000043701")
        (field (name "DB_VALUE") "100uF")
        (field (name "DB_TOLERANCE") "20%")
        (field (name "DB_VOLTAGE") "6.3V")
        (field (name "DB_MANUFACTURER_PART") "KEMET    C1210C107M9PAC")
      )
      (libsource (lib "Database_Libs1") (part "C"))
    )
    (comp (ref "C384")
      (value "C")
      (footprint "SMD_1210_CAPC3225X270N")
      (fields
        (field (name "DB_PART_NUMBER") "CAP000043701")
        (field (name "DB_VALUE") "100uF")
        (field (name "DB_TOLERANCE") "20%")
        (field (name "DB_VOLTAGE") "6.3V")
        (field (name "DB_MANUFACTURER_PART") "KEMET    C1210C107M9PAC")
      )
      (libsource (lib "Database_Libs1") (part "C"))
    )
    (comp (ref "C385")
      (value "C")
      (footprint "SMD_1210_CAPC3225X279N")
      (fields
        (field (name "DB_PART_NUMBER") "CAP000047355")
        (field (name "DB_VALUE") "220uF")
        (field (name "DB_TOLERANCE") "20%")
        (field (name "DB_VOLTAGE") "6.3V")
        (field (name "DB_MANUFACTURER_PART") "SAMSUNG    CL32A227MQVNNNE")
        (field (name "DB_APPROVED_BY") "VSN")
      )
      (libsource (lib "Database_Libs1") (part "C"))
    )
    (comp (ref "C386")
      (value "C")
      (footprint "SMD_1210_CAPC3225X279N")
      (fields
        (field (name "DB_PART_NUMBER") "CAP000047355")
        (field (name "DB_VALUE") "220uF")
        (field (name "DB_TOLERANCE") "20%")
        (field (name "DB_VOLTAGE") "6.3V")
        (field (name "DB_MANUFACTURER_PART") "SAMSUNG    CL32A227MQVNNNE")
        (field (name "DB_APPROVED_BY") "VSN")
      )
      (libsource (lib "Database_Libs1") (part "C"))
    )
    (comp (ref "C387")
      (value "C")
      (footprint "SMD_1210_CAPC3225X279N")
      (fields
        (field (name "DB_PART_NUMBER") "CAP000047355")
        (field (name "DB_VALUE") "220uF")
        (field (name "DB_TOLERANCE") "20%")
        (field (name "DB_VOLTAGE") "6.3V")
        (field (name "DB_MANUFACTURER_PART") "SAMSUNG    CL32A227MQVNNNE")
        (field (name "DB_APPROVED_BY") "VSN")
      )
      (libsource (lib "Database_Libs1") (part "C"))
    )
    (comp (ref "C388")
      (value "C")
      (footprint "SMD_1210_CAPC3225X279N")
      (fields
        (field (name "DB_PART_NUMBER") "CAP000047355")
        (field (name "DB_VALUE") "220uF")
        (field (name "DB_TOLERANCE") "20%")
        (field (name "DB_VOLTAGE") "6.3V")
        (field (name "DB_MANUFACTURER_PART") "SAMSUNG    CL32A227MQVNNNE")
        (field (name "DB_APPROVED_BY") "VSN")
      )
      (libsource (lib "Database_Libs1") (part "C"))
    )
    (comp (ref "C389")
      (value "C")
      (footprint "SMD_1210_CAPC3225X279N")
      (fields
        (field (name "DB_PART_NUMBER") "CAP000047355")
        (field (name "DB_VALUE") "220uF")
        (field (name "DB_TOLERANCE") "20%")
        (field (name "DB_VOLTAGE") "6.3V")
        (field (name "DB_MANUFACTURER_PART") "SAMSUNG    CL32A227MQVNNNE")
        (field (name "DB_APPROVED_BY") "VSN")
      )
      (libsource (lib "Database_Libs1") (part "C"))
    )
    (comp (ref "C390")
      (value "C")
      (footprint "SMD_1210_CAPC3225X279N")
      (fields
        (field (name "DB_PART_NUMBER") "CAP000047355")
        (field (name "DB_VALUE") "220uF")
        (field (name "DB_TOLERANCE") "20%")
        (field (name "DB_VOLTAGE") "6.3V")
        (field (name "DB_MANUFACTURER_PART") "SAMSUNG    CL32A227MQVNNNE")
        (field (name "DB_APPROVED_BY") "VSN")
      )
      (libsource (lib "Database_Libs1") (part "C"))
    )
    (comp (ref "C391")
      (value "C")
      (footprint "SMD_1210_CAPC3225X270N")
      (fields
        (field (name "DB_PART_NUMBER") "CAP000043701")
        (field (name "DB_VALUE") "100uF")
        (field (name "DB_TOLERANCE") "20%")
        (field (name "DB_VOLTAGE") "6.3V")
        (field (name "DB_MANUFACTURER_PART") "KEMET    C1210C107M9PAC")
      )
      (libsource (lib "Database_Libs1") (part "C"))
    )
    (comp (ref "C392")
      (value "C")
      (footprint "SMD_1210_CAPC3225X270N")
      (fields
        (field (name "DB_PART_NUMBER") "CAP000043701")
        (field (name "DB_VALUE") "100uF")
        (field (name "DB_TOLERANCE") "20%")
        (field (name "DB_VOLTAGE") "6.3V")
        (field (name "DB_MANUFACTURER_PART") "KEMET    C1210C107M9PAC")
      )
      (libsource (lib "Database_Libs1") (part "C"))
    )
    (comp (ref "C393")
      (value "C")
      (footprint "SMD_1210_CAPC3225X279N")
      (fields
        (field (name "DB_PART_NUMBER") "CAP000047355")
        (field (name "DB_VALUE") "220uF")
        (field (name "DB_TOLERANCE") "20%")
        (field (name "DB_VOLTAGE") "6.3V")
        (field (name "DB_MANUFACTURER_PART") "SAMSUNG    CL32A227MQVNNNE")
        (field (name "DB_APPROVED_BY") "VSN")
      )
      (libsource (lib "Database_Libs1") (part "C"))
    )
    (comp (ref "C394")
      (value "C")
      (footprint "SMD_1210_CAPC3225X279N")
      (fields
        (field (name "DB_PART_NUMBER") "CAP000047355")
        (field (name "DB_VALUE") "220uF")
        (field (name "DB_TOLERANCE") "20%")
        (field (name "DB_VOLTAGE") "6.3V")
        (field (name "DB_MANUFACTURER_PART") "SAMSUNG    CL32A227MQVNNNE")
        (field (name "DB_APPROVED_BY") "VSN")
      )
      (libsource (lib "Database_Libs1") (part "C"))
    )
    (comp (ref "C395")
      (value "C")
      (footprint "SMD_1210_CAPC3225X279N")
      (fields
        (field (name "DB_PART_NUMBER") "CAP000047355")
        (field (name "DB_VALUE") "220uF")
        (field (name "DB_TOLERANCE") "20%")
        (field (name "DB_VOLTAGE") "6.3V")
        (field (name "DB_MANUFACTURER_PART") "SAMSUNG    CL32A227MQVNNNE")
        (field (name "DB_APPROVED_BY") "VSN")
      )
      (libsource (lib "Database_Libs1") (part "C"))
    )
    (comp (ref "C396")
      (value "C")
      (footprint "SMD_1210_CAPC3225X279N")
      (fields
        (field (name "DB_PART_NUMBER") "CAP000047355")
        (field (name "DB_VALUE") "220uF")
        (field (name "DB_TOLERANCE") "20%")
        (field (name "DB_VOLTAGE") "6.3V")
        (field (name "DB_MANUFACTURER_PART") "SAMSUNG    CL32A227MQVNNNE")
        (field (name "DB_APPROVED_BY") "VSN")
      )
      (libsource (lib "Database_Libs1") (part "C"))
    )
    (comp (ref "C397")
      (value "C")
      (footprint "SMD_1210_CAPC3225X279N")
      (fields
        (field (name "DB_PART_NUMBER") "CAP000047355")
        (field (name "DB_VALUE") "220uF")
        (field (name "DB_TOLERANCE") "20%")
        (field (name "DB_VOLTAGE") "6.3V")
        (field (name "DB_MANUFACTURER_PART") "SAMSUNG    CL32A227MQVNNNE")
        (field (name "DB_APPROVED_BY") "VSN")
      )
      (libsource (lib "Database_Libs1") (part "C"))
    )
    (comp (ref "C398")
      (value "C")
      (footprint "SMD_1210_CAPC3225X279N")
      (fields
        (field (name "DB_PART_NUMBER") "CAP000047355")
        (field (name "DB_VALUE") "220uF")
        (field (name "DB_TOLERANCE") "20%")
        (field (name "DB_VOLTAGE") "6.3V")
        (field (name "DB_MANUFACTURER_PART") "SAMSUNG    CL32A227MQVNNNE")
        (field (name "DB_APPROVED_BY") "VSN")
      )
      (libsource (lib "Database_Libs1") (part "C"))
    )
    (comp (ref "C399")
      (value "C")
      (footprint "SMD_1210_CAPC3225X279N")
      (fields
        (field (name "DB_PART_NUMBER") "CAP000047355")
        (field (name "DB_VALUE") "220uF")
        (field (name "DB_TOLERANCE") "20%")
        (field (name "DB_VOLTAGE") "6.3V")
        (field (name "DB_MANUFACTURER_PART") "SAMSUNG    CL32A227MQVNNNE")
        (field (name "DB_APPROVED_BY") "VSN")
      )
      (libsource (lib "Database_Libs1") (part "C"))
    )
    (comp (ref "C400")
      (value "C")
      (footprint "SMD_1210_CAPC3225X279N")
      (fields
        (field (name "DB_PART_NUMBER") "CAP000047355")
        (field (name "DB_VALUE") "220uF")
        (field (name "DB_TOLERANCE") "20%")
        (field (name "DB_VOLTAGE") "6.3V")
        (field (name "DB_MANUFACTURER_PART") "SAMSUNG    CL32A227MQVNNNE")
        (field (name "DB_APPROVED_BY") "VSN")
      )
      (libsource (lib "Database_Libs1") (part "C"))
    )
    (comp (ref "C401")
      (value "C")
      (footprint "SMD_1210_CAPC3225X279N")
      (fields
        (field (name "DB_PART_NUMBER") "CAP000047355")
        (field (name "DB_VALUE") "220uF")
        (field (name "DB_TOLERANCE") "20%")
        (field (name "DB_VOLTAGE") "6.3V")
        (field (name "DB_MANUFACTURER_PART") "SAMSUNG    CL32A227MQVNNNE")
        (field (name "DB_APPROVED_BY") "VSN")
      )
      (libsource (lib "Database_Libs1") (part "C"))
    )
    (comp (ref "C402")
      (value "C")
      (footprint "SMD_1210_CAPC3225X270N")
      (fields
        (field (name "DB_PART_NUMBER") "CAP000043701")
        (field (name "DB_VALUE") "100uF")
        (field (name "DB_TOLERANCE") "20%")
        (field (name "DB_VOLTAGE") "6.3V")
        (field (name "DB_MANUFACTURER_PART") "KEMET    C1210C107M9PAC")
      )
      (libsource (lib "Database_Libs1") (part "C"))
    )
    (comp (ref "C403")
      (value "C")
      (footprint "SMD_1210_CAPC3225X270N")
      (fields
        (field (name "DB_PART_NUMBER") "CAP000043701")
        (field (name "DB_VALUE") "100uF")
        (field (name "DB_TOLERANCE") "20%")
        (field (name "DB_VOLTAGE") "6.3V")
        (field (name "DB_MANUFACTURER_PART") "KEMET    C1210C107M9PAC")
      )
      (libsource (lib "Database_Libs1") (part "C"))
    )
    (comp (ref "C404")
      (value "C")
      (footprint "SMD_1210_CAPC3225X270N")
      (fields
        (field (name "DB_PART_NUMBER") "CAP000043701")
        (field (name "DB_VALUE") "100uF")
        (field (name "DB_TOLERANCE") "20%")
        (field (name "DB_VOLTAGE") "6.3V")
        (field (name "DB_MANUFACTURER_PART") "KEMET    C1210C107M9PAC")
      )
      (libsource (lib "Database_Libs1") (part "C"))
    )
    (comp (ref "C405")
      (value "C")
      (footprint "SMD_1210_CAPC3225X270N")
      (fields
        (field (name "DB_PART_NUMBER") "CAP000043701")
        (field (name "DB_VALUE") "100uF")
        (field (name "DB_TOLERANCE") "20%")
        (field (name "DB_VOLTAGE") "6.3V")
        (field (name "DB_MANUFACTURER_PART") "KEMET    C1210C107M9PAC")
      )
      (libsource (lib "Database_Libs1") (part "C"))
    )
    (comp (ref "C406")
      (value "C")
      (footprint "SMD_1210_CAPC3225X270N")
      (fields
        (field (name "DB_PART_NUMBER") "CAP000043701")
        (field (name "DB_VALUE") "100uF")
        (field (name "DB_TOLERANCE") "20%")
        (field (name "DB_VOLTAGE") "6.3V")
        (field (name "DB_MANUFACTURER_PART") "KEMET    C1210C107M9PAC")
      )
      (libsource (lib "Database_Libs1") (part "C"))
    )
    (comp (ref "C407")
      (value "C")
      (footprint "SMD_1210_CAPC3225X270N")
      (fields
        (field (name "DB_PART_NUMBER") "CAP000043701")
        (field (name "DB_VALUE") "100uF")
        (field (name "DB_TOLERANCE") "20%")
        (field (name "DB_VOLTAGE") "6.3V")
        (field (name "DB_MANUFACTURER_PART") "KEMET    C1210C107M9PAC")
      )
      (libsource (lib "Database_Libs1") (part "C"))
    )
    (comp (ref "C408")
      (value "C")
      (footprint "SMD_1210_CAPC3225X279N")
      (fields
        (field (name "DB_PART_NUMBER") "CAP000047355")
        (field (name "DB_VALUE") "220uF")
        (field (name "DB_TOLERANCE") "20%")
        (field (name "DB_VOLTAGE") "6.3V")
        (field (name "DB_MANUFACTURER_PART") "SAMSUNG    CL32A227MQVNNNE")
        (field (name "DB_APPROVED_BY") "VSN")
      )
      (libsource (lib "Database_Libs1") (part "C"))
    )
    (comp (ref "C409")
      (value "C")
      (footprint "SMD_1210_CAPC3225X279N")
      (fields
        (field (name "DB_PART_NUMBER") "CAP000047355")
        (field (name "DB_VALUE") "220uF")
        (field (name "DB_TOLERANCE") "20%")
        (field (name "DB_VOLTAGE") "6.3V")
        (field (name "DB_MANUFACTURER_PART") "SAMSUNG    CL32A227MQVNNNE")
        (field (name "DB_APPROVED_BY") "VSN")
      )
      (libsource (lib "Database_Libs1") (part "C"))
    )
    (comp (ref "C410")
      (value "C")
      (footprint "SMD_1210_CAPC3225X279N")
      (fields
        (field (name "DB_PART_NUMBER") "CAP000047355")
        (field (name "DB_VALUE") "220uF")
        (field (name "DB_TOLERANCE") "20%")
        (field (name "DB_VOLTAGE") "6.3V")
        (field (name "DB_MANUFACTURER_PART") "SAMSUNG    CL32A227MQVNNNE")
        (field (name "DB_APPROVED_BY") "VSN")
      )
      (libsource (lib "Database_Libs1") (part "C"))
    )
    (comp (ref "C411")
      (value "C")
      (footprint "SMD_1210_CAPC3225X279N")
      (fields
        (field (name "DB_PART_NUMBER") "CAP000047355")
        (field (name "DB_VALUE") "220uF")
        (field (name "DB_TOLERANCE") "20%")
        (field (name "DB_VOLTAGE") "6.3V")
        (field (name "DB_MANUFACTURER_PART") "SAMSUNG    CL32A227MQVNNNE")
        (field (name "DB_APPROVED_BY") "VSN")
      )
      (libsource (lib "Database_Libs1") (part "C"))
    )
    (comp (ref "C412")
      (value "C")
      (footprint "SMD_1210_CAPC3225X279N")
      (fields
        (field (name "DB_PART_NUMBER") "CAP000047355")
        (field (name "DB_VALUE") "220uF")
        (field (name "DB_TOLERANCE") "20%")
        (field (name "DB_VOLTAGE") "6.3V")
        (field (name "DB_MANUFACTURER_PART") "SAMSUNG    CL32A227MQVNNNE")
        (field (name "DB_APPROVED_BY") "VSN")
      )
      (libsource (lib "Database_Libs1") (part "C"))
    )
    (comp (ref "C413")
      (value "C")
      (footprint "SMD_1210_CAPC3225X279N")
      (fields
        (field (name "DB_PART_NUMBER") "CAP000047355")
        (field (name "DB_VALUE") "220uF")
        (field (name "DB_TOLERANCE") "20%")
        (field (name "DB_VOLTAGE") "6.3V")
        (field (name "DB_MANUFACTURER_PART") "SAMSUNG    CL32A227MQVNNNE")
        (field (name "DB_APPROVED_BY") "VSN")
      )
      (libsource (lib "Database_Libs1") (part "C"))
    )
    (comp (ref "C414")
      (value "C")
      (footprint "SMD_1210_CAPC3225X279N")
      (fields
        (field (name "DB_PART_NUMBER") "CAP000047355")
        (field (name "DB_VALUE") "220uF")
        (field (name "DB_TOLERANCE") "20%")
        (field (name "DB_VOLTAGE") "6.3V")
        (field (name "DB_MANUFACTURER_PART") "SAMSUNG    CL32A227MQVNNNE")
        (field (name "DB_APPROVED_BY") "VSN")
      )
      (libsource (lib "Database_Libs1") (part "C"))
    )
    (comp (ref "C415")
      (value "C")
      (footprint "SMD_1210_CAPC3225X279N")
      (fields
        (field (name "DB_PART_NUMBER") "CAP000047355")
        (field (name "DB_VALUE") "220uF")
        (field (name "DB_TOLERANCE") "20%")
        (field (name "DB_VOLTAGE") "6.3V")
        (field (name "DB_MANUFACTURER_PART") "SAMSUNG    CL32A227MQVNNNE")
        (field (name "DB_APPROVED_BY") "VSN")
      )
      (libsource (lib "Database_Libs1") (part "C"))
    )
    (comp (ref "C416")
      (value "C")
      (footprint "SMD_1210_CAPC3225X279N")
      (fields
        (field (name "DB_PART_NUMBER") "CAP000047355")
        (field (name "DB_VALUE") "220uF")
        (field (name "DB_TOLERANCE") "20%")
        (field (name "DB_VOLTAGE") "6.3V")
        (field (name "DB_MANUFACTURER_PART") "SAMSUNG    CL32A227MQVNNNE")
        (field (name "DB_APPROVED_BY") "VSN")
      )
      (libsource (lib "Database_Libs1") (part "C"))
    )
    (comp (ref "C417")
      (value "C")
      (footprint "SMD_1210_CAPC3225X279N")
      (fields
        (field (name "DB_PART_NUMBER") "CAP000047355")
        (field (name "DB_VALUE") "220uF")
        (field (name "DB_TOLERANCE") "20%")
        (field (name "DB_VOLTAGE") "6.3V")
        (field (name "DB_MANUFACTURER_PART") "SAMSUNG    CL32A227MQVNNNE")
        (field (name "DB_APPROVED_BY") "VSN")
      )
      (libsource (lib "Database_Libs1") (part "C"))
    )
    (comp (ref "C418")
      (value "C")
      (footprint "SMD_1210_CAPC3225X279N")
      (fields
        (field (name "DB_PART_NUMBER") "CAP000047355")
        (field (name "DB_VALUE") "220uF")
        (field (name "DB_TOLERANCE") "20%")
        (field (name "DB_VOLTAGE") "6.3V")
        (field (name "DB_MANUFACTURER_PART") "SAMSUNG    CL32A227MQVNNNE")
        (field (name "DB_APPROVED_BY") "VSN")
      )
      (libsource (lib "Database_Libs1") (part "C"))
    )
    (comp (ref "C419")
      (value "C")
      (footprint "SMD_1210_CAPC3225X279N")
      (fields
        (field (name "DB_PART_NUMBER") "CAP000047355")
        (field (name "DB_VALUE") "220uF")
        (field (name "DB_TOLERANCE") "20%")
        (field (name "DB_VOLTAGE") "6.3V")
        (field (name "DB_MANUFACTURER_PART") "SAMSUNG    CL32A227MQVNNNE")
        (field (name "DB_APPROVED_BY") "VSN")
      )
      (libsource (lib "Database_Libs1") (part "C"))
    )
    (comp (ref "C420")
      (value "C")
      (footprint "SMD_1210_CAPC3225X270N")
      (fields
        (field (name "DB_PART_NUMBER") "CAP000043701")
        (field (name "DB_VALUE") "100uF")
        (field (name "DB_TOLERANCE") "20%")
        (field (name "DB_VOLTAGE") "6.3V")
        (field (name "DB_MANUFACTURER_PART") "KEMET    C1210C107M9PAC")
      )
      (libsource (lib "Database_Libs1") (part "C"))
    )
    (comp (ref "C421")
      (value "C")
      (footprint "SMD_1210_CAPC3225X270N")
      (fields
        (field (name "DB_PART_NUMBER") "CAP000043701")
        (field (name "DB_VALUE") "100uF")
        (field (name "DB_TOLERANCE") "20%")
        (field (name "DB_VOLTAGE") "6.3V")
        (field (name "DB_MANUFACTURER_PART") "KEMET    C1210C107M9PAC")
      )
      (libsource (lib "Database_Libs1") (part "C"))
    )
    (comp (ref "C422")
      (value "C")
      (footprint "SMD_1210_CAPC3225X270N")
      (fields
        (field (name "DB_PART_NUMBER") "CAP000043701")
        (field (name "DB_VALUE") "100uF")
        (field (name "DB_TOLERANCE") "20%")
        (field (name "DB_VOLTAGE") "6.3V")
        (field (name "DB_MANUFACTURER_PART") "KEMET    C1210C107M9PAC")
      )
      (libsource (lib "Database_Libs1") (part "C"))
    )
    (comp (ref "C423")
      (value "C")
      (footprint "SMD_1210_CAPC3225X270N")
      (fields
        (field (name "DB_PART_NUMBER") "CAP000043701")
        (field (name "DB_VALUE") "100uF")
        (field (name "DB_TOLERANCE") "20%")
        (field (name "DB_VOLTAGE") "6.3V")
        (field (name "DB_MANUFACTURER_PART") "KEMET    C1210C107M9PAC")
      )
      (libsource (lib "Database_Libs1") (part "C"))
    )
    (comp (ref "C424")
      (value "C")
      (footprint "SMD_1210_CAPC3225X270N")
      (fields
        (field (name "DB_PART_NUMBER") "CAP000043701")
        (field (name "DB_VALUE") "100uF")
        (field (name "DB_TOLERANCE") "20%")
        (field (name "DB_VOLTAGE") "6.3V")
        (field (name "DB_MANUFACTURER_PART") "KEMET    C1210C107M9PAC")
      )
      (libsource (lib "Database_Libs1") (part "C"))
    )
    (comp (ref "C425")
      (value "C")
      (footprint "SMD_1210_CAPC3225X270N")
      (fields
        (field (name "DB_PART_NUMBER") "CAP000043701")
        (field (name "DB_VALUE") "100uF")
        (field (name "DB_TOLERANCE") "20%")
        (field (name "DB_VOLTAGE") "6.3V")
        (field (name "DB_MANUFACTURER_PART") "KEMET    C1210C107M9PAC")
      )
      (libsource (lib "Database_Libs1") (part "C"))
    )
    (comp (ref "C426")
      (value "C")
      (footprint "SMD_1210_CAPC3225X270N")
      (fields
        (field (name "DB_PART_NUMBER") "CAP000043701")
        (field (name "DB_VALUE") "100uF")
        (field (name "DB_TOLERANCE") "20%")
        (field (name "DB_VOLTAGE") "6.3V")
        (field (name "DB_MANUFACTURER_PART") "KEMET    C1210C107M9PAC")
      )
      (libsource (lib "Database_Libs1") (part "C"))
    )
    (comp (ref "C427")
      (value "C")
      (footprint "SMD_1210_CAPC3225X270N")
      (fields
        (field (name "DB_PART_NUMBER") "CAP000043701")
        (field (name "DB_VALUE") "100uF")
        (field (name "DB_TOLERANCE") "20%")
        (field (name "DB_VOLTAGE") "6.3V")
        (field (name "DB_MANUFACTURER_PART") "KEMET    C1210C107M9PAC")
      )
      (libsource (lib "Database_Libs1") (part "C"))
    )
    (comp (ref "D10")
      (value "D")
      (footprint "SMD_SOD523_SOD1608X65N")
      (fields
        (field (name "DB_PART_NUMBER") "DDE000001203")
        (field (name "DB_VALUE") "1N4448HWT")
        (field (name "DB_MANUFACTURER_PART") "Diodes        1N4448HWT")
      )
      (libsource (lib "Database_Libs1") (part "D"))
    )
    (comp (ref "D11")
      (value "D")
      (footprint "SMD_SOD523_SOD1608X65N")
      (fields
        (field (name "DB_PART_NUMBER") "DDE000001203")
        (field (name "DB_VALUE") "1N4448HWT")
        (field (name "DB_MANUFACTURER_PART") "Diodes        1N4448HWT")
      )
      (libsource (lib "Database_Libs1") (part "D"))
    )
    (comp (ref "D12")
      (value "D")
      (footprint "SMD_SOD523_SOD1608X65N")
      (fields
        (field (name "DB_PART_NUMBER") "DDE000001203")
        (field (name "DB_VALUE") "1N4448HWT")
        (field (name "DB_MANUFACTURER_PART") "Diodes        1N4448HWT")
      )
      (libsource (lib "Database_Libs1") (part "D"))
    )
    (comp (ref "D13")
      (value "D")
      (footprint "SMD_SOD523_SOD1608X65N")
      (fields
        (field (name "DB_PART_NUMBER") "DDE000001203")
        (field (name "DB_VALUE") "1N4448HWT")
        (field (name "DB_MANUFACTURER_PART") "Diodes        1N4448HWT")
      )
      (libsource (lib "Database_Libs1") (part "D"))
    )
    (comp (ref "D14")
      (value "D")
      (footprint "SMD_SOD523_SOD1608X65N")
      (fields
        (field (name "DB_PART_NUMBER") "DDE000001203")
        (field (name "DB_VALUE") "1N4448HWT")
        (field (name "DB_MANUFACTURER_PART") "Diodes        1N4448HWT")
      )
      (libsource (lib "Database_Libs1") (part "D"))
    )
    (comp (ref "D15")
      (value "D")
      (footprint "SMD_SOD523_SOD1608X65N")
      (fields
        (field (name "DB_PART_NUMBER") "DDE000001203")
        (field (name "DB_VALUE") "1N4448HWT")
        (field (name "DB_MANUFACTURER_PART") "Diodes        1N4448HWT")
      )
      (libsource (lib "Database_Libs1") (part "D"))
    )
    (comp (ref "D16")
      (value "D")
      (footprint "SMD_SOD523_SOD1608X65N")
      (fields
        (field (name "DB_PART_NUMBER") "DDE000001203")
        (field (name "DB_VALUE") "1N4448HWT")
        (field (name "DB_MANUFACTURER_PART") "Diodes        1N4448HWT")
      )
      (libsource (lib "Database_Libs1") (part "D"))
    )
    (comp (ref "D17")
      (value "D")
      (footprint "SMD_SOD523_SOD1608X65N")
      (fields
        (field (name "DB_PART_NUMBER") "DDE000001203")
        (field (name "DB_VALUE") "1N4448HWT")
        (field (name "DB_MANUFACTURER_PART") "Diodes        1N4448HWT")
      )
      (libsource (lib "Database_Libs1") (part "D"))
    )
    (comp (ref "D18")
      (value "D")
      (footprint "SMD_SOD523_SOD1608X65N")
      (fields
        (field (name "DB_PART_NUMBER") "DDE000001203")
        (field (name "DB_VALUE") "1N4448HWT")
        (field (name "DB_MANUFACTURER_PART") "Diodes        1N4448HWT")
      )
      (libsource (lib "Database_Libs1") (part "D"))
    )
    (comp (ref "D19")
      (value "D")
      (footprint "SMD_SOD523_SOD1608X65N")
      (fields
        (field (name "DB_PART_NUMBER") "DDE000001203")
        (field (name "DB_VALUE") "1N4448HWT")
        (field (name "DB_MANUFACTURER_PART") "Diodes        1N4448HWT")
      )
      (libsource (lib "Database_Libs1") (part "D"))
    )
    (comp (ref "D20")
      (value "D")
      (footprint "SMD_SOD523_SOD1608X65N")
      (fields
        (field (name "DB_PART_NUMBER") "DDE000001203")
        (field (name "DB_VALUE") "1N4448HWT")
        (field (name "DB_MANUFACTURER_PART") "Diodes        1N4448HWT")
      )
      (libsource (lib "Database_Libs1") (part "D"))
    )
    (comp (ref "D21")
      (value "D")
      (footprint "SMD_SOD523_SOD1608X65N")
      (fields
        (field (name "DB_PART_NUMBER") "DDE000001203")
        (field (name "DB_VALUE") "1N4448HWT")
        (field (name "DB_MANUFACTURER_PART") "Diodes        1N4448HWT")
      )
      (libsource (lib "Database_Libs1") (part "D"))
    )
    (comp (ref "D22")
      (value "D")
      (footprint "SMD_SOD523_SOD1608X65N")
      (fields
        (field (name "DB_PART_NUMBER") "DDE000001203")
        (field (name "DB_VALUE") "1N4448HWT")
        (field (name "DB_MANUFACTURER_PART") "Diodes        1N4448HWT")
      )
      (libsource (lib "Database_Libs1") (part "D"))
    )
    (comp (ref "D23")
      (value "D")
      (footprint "SMD_SOD523_SOD1608X65N")
      (fields
        (field (name "DB_PART_NUMBER") "DDE000001203")
        (field (name "DB_VALUE") "1N4448HWT")
        (field (name "DB_MANUFACTURER_PART") "Diodes        1N4448HWT")
      )
      (libsource (lib "Database_Libs1") (part "D"))
    )
    (comp (ref "D24")
      (value "D")
      (footprint "SMD_SOD523_SOD1608X65N")
      (fields
        (field (name "DB_PART_NUMBER") "DDE000001203")
        (field (name "DB_VALUE") "1N4448HWT")
        (field (name "DB_MANUFACTURER_PART") "Diodes        1N4448HWT")
      )
      (libsource (lib "Database_Libs1") (part "D"))
    )
    (comp (ref "D25")
      (value "D")
      (footprint "SMD_SOD523_SOD1608X65N")
      (fields
        (field (name "DB_PART_NUMBER") "DDE000001203")
        (field (name "DB_VALUE") "1N4448HWT")
        (field (name "DB_MANUFACTURER_PART") "Diodes        1N4448HWT")
      )
      (libsource (lib "Database_Libs1") (part "D"))
    )
    (comp (ref "L1")
      (value "L")
      (footprint "SMT_INDM135130X800N")
      (libsource (lib "EPIQ_DND_CIS_Library") (part "L"))
    )
    (comp (ref "L2")
      (value "L")
      (footprint "SMT_INDM135130X800N")
      (libsource (lib "EPIQ_DND_CIS_Library") (part "L"))
    )
    (comp (ref "L3")
      (value "L")
      (footprint "SMT_INDM135130X800N")
      (libsource (lib "EPIQ_DND_CIS_Library") (part "L"))
    )
    (comp (ref "L4")
      (value "L")
      (footprint "SMT_INDM135130X800N")
      (libsource (lib "EPIQ_DND_CIS_Library") (part "L"))
    )
    (comp (ref "L5")
      (value "L")
      (footprint "SMT_INDM135130X800N")
      (libsource (lib "EPIQ_DND_CIS_Library") (part "L"))
    )
    (comp (ref "L6")
      (value "L")
      (footprint "SMT_INDM135130X800N")
      (libsource (lib "EPIQ_DND_CIS_Library") (part "L"))
    )
    (comp (ref "L7")
      (value "L")
      (footprint "SMT_INDM135130X800N")
      (libsource (lib "EPIQ_DND_CIS_Library") (part "L"))
    )
    (comp (ref "L8")
      (value "L")
      (footprint "SMT_INDM135130X800N")
      (libsource (lib "EPIQ_DND_CIS_Library") (part "L"))
    )
    (comp (ref "L9")
      (value "L")
      (footprint "SMT_INDM135130X800N")
      (libsource (lib "EPIQ_DND_CIS_Library") (part "L"))
    )
    (comp (ref "L10")
      (value "L")
      (footprint "SMT_INDM135130X800N")
      (libsource (lib "EPIQ_DND_CIS_Library") (part "L"))
    )
    (comp (ref "L11")
      (value "L")
      (footprint "SMT_INDM135130X800N")
      (libsource (lib "EPIQ_DND_CIS_Library") (part "L"))
    )
    (comp (ref "L12")
      (value "L")
      (footprint "SMT_INDM135130X800N")
      (libsource (lib "EPIQ_DND_CIS_Library") (part "L"))
    )
    (comp (ref "L13")
      (value "L")
      (footprint "SMT_INDM135130X800N")
      (libsource (lib "EPIQ_DND_CIS_Library") (part "L"))
    )
    (comp (ref "L14")
      (value "L")
      (footprint "SMT_INDM135130X800N")
      (libsource (lib "EPIQ_DND_CIS_Library") (part "L"))
    )
    (comp (ref "L15")
      (value "L")
      (footprint "SMT_INDM135130X800N")
      (libsource (lib "EPIQ_DND_CIS_Library") (part "L"))
    )
    (comp (ref "L16")
      (value "L")
      (footprint "SMT_INDM135130X800N")
      (libsource (lib "EPIQ_DND_CIS_Library") (part "L"))
    )
    (comp (ref "Q1")
      (value "MOS_N_D1_S1S2S3G4D5D6D7D8")
      (footprint "SMD_SOIC127P600X110-9AN")
      (fields
        (field (name "DB_PART_NUMBER") "TRA000001604")
        (field (name "DB_VALUE") "AP1RA03GMT-HF-3")
        (field (name "DB_MANUFACTURER_PART") "ADVANCED POWER ELECTRONICS CORP      AP1RA03GMT-HF-3")
        (field (name "DB_APPROVED_BY") "VSN")
      )
      (libsource (lib "Database_Libs1") (part "MOS_N_D1_S1S2S3G4D5D6D7D8"))
    )
    (comp (ref "Q2")
      (value "MOS_N_D1_S1S2S3G4D5D6D7D8")
      (footprint "SMD_SOIC127P600X110-9AN")
      (fields
        (field (name "DB_PART_NUMBER") "TRA000001604")
        (field (name "DB_VALUE") "AP1RA03GMT-HF-3")
        (field (name "DB_MANUFACTURER_PART") "ADVANCED POWER ELECTRONICS CORP      AP1RA03GMT-HF-3")
        (field (name "DB_APPROVED_BY") "VSN")
      )
      (libsource (lib "Database_Libs1") (part "MOS_N_D1_S1S2S3G4D5D6D7D8"))
    )
    (comp (ref "Q3")
      (value "MOS_N_D1_S1S2S3G4D5D6D7D8")
      (footprint "SMD_SOIC127P600X110-9AN")
      (fields
        (field (name "DB_PART_NUMBER") "TRA000001604")
        (field (name "DB_VALUE") "AP1RA03GMT-HF-3")
        (field (name "DB_MANUFACTURER_PART") "ADVANCED POWER ELECTRONICS CORP      AP1RA03GMT-HF-3")
        (field (name "DB_APPROVED_BY") "VSN")
      )
      (libsource (lib "Database_Libs1") (part "MOS_N_D1_S1S2S3G4D5D6D7D8"))
    )
    (comp (ref "Q4")
      (value "MOS_N_D1_S1S2S3G4D5D6D7D8")
      (footprint "SMD_SOIC127P600X110-9AN")
      (fields
        (field (name "DB_PART_NUMBER") "TRA000001604")
        (field (name "DB_VALUE") "AP1RA03GMT-HF-3")
        (field (name "DB_MANUFACTURER_PART") "ADVANCED POWER ELECTRONICS CORP      AP1RA03GMT-HF-3")
        (field (name "DB_APPROVED_BY") "VSN")
      )
      (libsource (lib "Database_Libs1") (part "MOS_N_D1_S1S2S3G4D5D6D7D8"))
    )
    (comp (ref "Q5")
      (value "MOS_N_D1_S1S2S3G4D5D6D7D8")
      (footprint "SMD_SOIC127P600X110-9AN")
      (fields
        (field (name "DB_PART_NUMBER") "TRA000001604")
        (field (name "DB_VALUE") "AP1RA03GMT-HF-3")
        (field (name "DB_MANUFACTURER_PART") "ADVANCED POWER ELECTRONICS CORP      AP1RA03GMT-HF-3")
        (field (name "DB_APPROVED_BY") "VSN")
      )
      (libsource (lib "Database_Libs1") (part "MOS_N_D1_S1S2S3G4D5D6D7D8"))
    )
    (comp (ref "Q6")
      (value "MOS_N_D1_S1S2S3G4D5D6D7D8")
      (footprint "SMD_SOIC127P600X110-9AN")
      (fields
        (field (name "DB_PART_NUMBER") "TRA000001604")
        (field (name "DB_VALUE") "AP1RA03GMT-HF-3")
        (field (name "DB_MANUFACTURER_PART") "ADVANCED POWER ELECTRONICS CORP      AP1RA03GMT-HF-3")
        (field (name "DB_APPROVED_BY") "VSN")
      )
      (libsource (lib "Database_Libs1") (part "MOS_N_D1_S1S2S3G4D5D6D7D8"))
    )
    (comp (ref "Q7")
      (value "MOS_N_D1_S1S2S3G4D5D6D7D8")
      (footprint "SMD_SOIC127P600X110-9AN")
      (fields
        (field (name "DB_PART_NUMBER") "TRA000001604")
        (field (name "DB_VALUE") "AP1RA03GMT-HF-3")
        (field (name "DB_MANUFACTURER_PART") "ADVANCED POWER ELECTRONICS CORP      AP1RA03GMT-HF-3")
        (field (name "DB_APPROVED_BY") "VSN")
      )
      (libsource (lib "Database_Libs1") (part "MOS_N_D1_S1S2S3G4D5D6D7D8"))
    )
    (comp (ref "Q8")
      (value "MOS_N_D1_S1S2S3G4D5D6D7D8")
      (footprint "SMD_SOIC127P600X110-9AN")
      (fields
        (field (name "DB_PART_NUMBER") "TRA000001604")
        (field (name "DB_VALUE") "AP1RA03GMT-HF-3")
        (field (name "DB_MANUFACTURER_PART") "ADVANCED POWER ELECTRONICS CORP      AP1RA03GMT-HF-3")
        (field (name "DB_APPROVED_BY") "VSN")
      )
      (libsource (lib "Database_Libs1") (part "MOS_N_D1_S1S2S3G4D5D6D7D8"))
    )
    (comp (ref "Q9")
      (value "MOS_N_D1_S1S2S3G4D5D6D7D8")
      (footprint "SMD_SOIC127P600X110-9AN")
      (fields
        (field (name "DB_PART_NUMBER") "TRA000001604")
        (field (name "DB_VALUE") "AP1RA03GMT-HF-3")
        (field (name "DB_MANUFACTURER_PART") "ADVANCED POWER ELECTRONICS CORP      AP1RA03GMT-HF-3")
        (field (name "DB_APPROVED_BY") "VSN")
      )
      (libsource (lib "Database_Libs1") (part "MOS_N_D1_S1S2S3G4D5D6D7D8"))
    )
    (comp (ref "Q10")
      (value "MOS_N_D1_S1S2S3G4D5D6D7D8")
      (footprint "SMD_SOIC127P600X110-9AN")
      (fields
        (field (name "DB_PART_NUMBER") "TRA000001604")
        (field (name "DB_VALUE") "AP1RA03GMT-HF-3")
        (field (name "DB_MANUFACTURER_PART") "ADVANCED POWER ELECTRONICS CORP      AP1RA03GMT-HF-3")
        (field (name "DB_APPROVED_BY") "VSN")
      )
      (libsource (lib "Database_Libs1") (part "MOS_N_D1_S1S2S3G4D5D6D7D8"))
    )
    (comp (ref "Q11")
      (value "MOS_N_D1_S1S2S3G4D5D6D7D8")
      (footprint "SMD_SOIC127P600X110-9AN")
      (fields
        (field (name "DB_PART_NUMBER") "TRA000001604")
        (field (name "DB_VALUE") "AP1RA03GMT-HF-3")
        (field (name "DB_MANUFACTURER_PART") "ADVANCED POWER ELECTRONICS CORP      AP1RA03GMT-HF-3")
        (field (name "DB_APPROVED_BY") "VSN")
      )
      (libsource (lib "Database_Libs1") (part "MOS_N_D1_S1S2S3G4D5D6D7D8"))
    )
    (comp (ref "Q12")
      (value "MOS_N_D1_S1S2S3G4D5D6D7D8")
      (footprint "SMD_SOIC127P600X110-9AN")
      (fields
        (field (name "DB_PART_NUMBER") "TRA000001604")
        (field (name "DB_VALUE") "AP1RA03GMT-HF-3")
        (field (name "DB_MANUFACTURER_PART") "ADVANCED POWER ELECTRONICS CORP      AP1RA03GMT-HF-3")
        (field (name "DB_APPROVED_BY") "VSN")
      )
      (libsource (lib "Database_Libs1") (part "MOS_N_D1_S1S2S3G4D5D6D7D8"))
    )
    (comp (ref "Q13")
      (value "MOS_N_D1_S1S2S3G4D5D6D7D8")
      (footprint "SMD_SOIC127P600X110-9AN")
      (fields
        (field (name "DB_PART_NUMBER") "TRA000001604")
        (field (name "DB_VALUE") "AP1RA03GMT-HF-3")
        (field (name "DB_MANUFACTURER_PART") "ADVANCED POWER ELECTRONICS CORP      AP1RA03GMT-HF-3")
        (field (name "DB_APPROVED_BY") "VSN")
      )
      (libsource (lib "Database_Libs1") (part "MOS_N_D1_S1S2S3G4D5D6D7D8"))
    )
    (comp (ref "Q14")
      (value "MOS_N_D1_S1S2S3G4D5D6D7D8")
      (footprint "SMD_SOIC127P600X110-9AN")
      (fields
        (field (name "DB_PART_NUMBER") "TRA000001604")
        (field (name "DB_VALUE") "AP1RA03GMT-HF-3")
        (field (name "DB_MANUFACTURER_PART") "ADVANCED POWER ELECTRONICS CORP      AP1RA03GMT-HF-3")
        (field (name "DB_APPROVED_BY") "VSN")
      )
      (libsource (lib "Database_Libs1") (part "MOS_N_D1_S1S2S3G4D5D6D7D8"))
    )
    (comp (ref "Q15")
      (value "MOS_N_D1_S1S2S3G4D5D6D7D8")
      (footprint "SMD_SOIC127P600X110-9AN")
      (fields
        (field (name "DB_PART_NUMBER") "TRA000001604")
        (field (name "DB_VALUE") "AP1RA03GMT-HF-3")
        (field (name "DB_MANUFACTURER_PART") "ADVANCED POWER ELECTRONICS CORP      AP1RA03GMT-HF-3")
        (field (name "DB_APPROVED_BY") "VSN")
      )
      (libsource (lib "Database_Libs1") (part "MOS_N_D1_S1S2S3G4D5D6D7D8"))
    )
    (comp (ref "Q16")
      (value "MOS_N_D1_S1S2S3G4D5D6D7D8")
      (footprint "SMD_SOIC127P600X110-9AN")
      (fields
        (field (name "DB_PART_NUMBER") "TRA000001604")
        (field (name "DB_VALUE") "AP1RA03GMT-HF-3")
        (field (name "DB_MANUFACTURER_PART") "ADVANCED POWER ELECTRONICS CORP      AP1RA03GMT-HF-3")
        (field (name "DB_APPROVED_BY") "VSN")
      )
      (libsource (lib "Database_Libs1") (part "MOS_N_D1_S1S2S3G4D5D6D7D8"))
    )
    (comp (ref "Q17")
      (value "MOS_N_D1_S1S2S3G4D5D6D7D8")
      (footprint "SMD_SOIC127P600X110-9AN")
      (fields
        (field (name "DB_PART_NUMBER") "TRA000001604")
        (field (name "DB_VALUE") "AP1RA03GMT-HF-3")
        (field (name "DB_MANUFACTURER_PART") "ADVANCED POWER ELECTRONICS CORP      AP1RA03GMT-HF-3")
        (field (name "DB_APPROVED_BY") "VSN")
      )
      (libsource (lib "Database_Libs1") (part "MOS_N_D1_S1S2S3G4D5D6D7D8"))
    )
    (comp (ref "Q18")
      (value "MOS_N_D1_S1S2S3G4D5D6D7D8")
      (footprint "SMD_SOIC127P600X110-9AN")
      (fields
        (field (name "DB_PART_NUMBER") "TRA000001604")
        (field (name "DB_VALUE") "AP1RA03GMT-HF-3")
        (field (name "DB_MANUFACTURER_PART") "ADVANCED POWER ELECTRONICS CORP      AP1RA03GMT-HF-3")
        (field (name "DB_APPROVED_BY") "VSN")
      )
      (libsource (lib "Database_Libs1") (part "MOS_N_D1_S1S2S3G4D5D6D7D8"))
    )
    (comp (ref "Q19")
      (value "MOS_N_D1_S1S2S3G4D5D6D7D8")
      (footprint "SMD_SOIC127P600X110-9AN")
      (fields
        (field (name "DB_PART_NUMBER") "TRA000001604")
        (field (name "DB_VALUE") "AP1RA03GMT-HF-3")
        (field (name "DB_MANUFACTURER_PART") "ADVANCED POWER ELECTRONICS CORP      AP1RA03GMT-HF-3")
        (field (name "DB_APPROVED_BY") "VSN")
      )
      (libsource (lib "Database_Libs1") (part "MOS_N_D1_S1S2S3G4D5D6D7D8"))
    )
    (comp (ref "Q20")
      (value "MOS_N_D1_S1S2S3G4D5D6D7D8")
      (footprint "SMD_SOIC127P600X110-9AN")
      (fields
        (field (name "DB_PART_NUMBER") "TRA000001604")
        (field (name "DB_VALUE") "AP1RA03GMT-HF-3")
        (field (name "DB_MANUFACTURER_PART") "ADVANCED POWER ELECTRONICS CORP      AP1RA03GMT-HF-3")
        (field (name "DB_APPROVED_BY") "VSN")
      )
      (libsource (lib "Database_Libs1") (part "MOS_N_D1_S1S2S3G4D5D6D7D8"))
    )
    (comp (ref "Q21")
      (value "MOS_N_D1_S1S2S3G4D5D6D7D8")
      (footprint "SMD_SOIC127P600X110-9AN")
      (fields
        (field (name "DB_PART_NUMBER") "TRA000001604")
        (field (name "DB_VALUE") "AP1RA03GMT-HF-3")
        (field (name "DB_MANUFACTURER_PART") "ADVANCED POWER ELECTRONICS CORP      AP1RA03GMT-HF-3")
        (field (name "DB_APPROVED_BY") "VSN")
      )
      (libsource (lib "Database_Libs1") (part "MOS_N_D1_S1S2S3G4D5D6D7D8"))
    )
    (comp (ref "Q22")
      (value "MOS_N_D1_S1S2S3G4D5D6D7D8")
      (footprint "SMD_SOIC127P600X110-9AN")
      (fields
        (field (name "DB_PART_NUMBER") "TRA000001604")
        (field (name "DB_VALUE") "AP1RA03GMT-HF-3")
        (field (name "DB_MANUFACTURER_PART") "ADVANCED POWER ELECTRONICS CORP      AP1RA03GMT-HF-3")
        (field (name "DB_APPROVED_BY") "VSN")
      )
      (libsource (lib "Database_Libs1") (part "MOS_N_D1_S1S2S3G4D5D6D7D8"))
    )
    (comp (ref "Q23")
      (value "MOS_N_D1_S1S2S3G4D5D6D7D8")
      (footprint "SMD_SOIC127P600X110-9AN")
      (fields
        (field (name "DB_PART_NUMBER") "TRA000001604")
        (field (name "DB_VALUE") "AP1RA03GMT-HF-3")
        (field (name "DB_MANUFACTURER_PART") "ADVANCED POWER ELECTRONICS CORP      AP1RA03GMT-HF-3")
        (field (name "DB_APPROVED_BY") "VSN")
      )
      (libsource (lib "Database_Libs1") (part "MOS_N_D1_S1S2S3G4D5D6D7D8"))
    )
    (comp (ref "Q24")
      (value "MOS_N_D1_S1S2S3G4D5D6D7D8")
      (footprint "SMD_SOIC127P600X110-9AN")
      (fields
        (field (name "DB_PART_NUMBER") "TRA000001604")
        (field (name "DB_VALUE") "AP1RA03GMT-HF-3")
        (field (name "DB_MANUFACTURER_PART") "ADVANCED POWER ELECTRONICS CORP      AP1RA03GMT-HF-3")
        (field (name "DB_APPROVED_BY") "VSN")
      )
      (libsource (lib "Database_Libs1") (part "MOS_N_D1_S1S2S3G4D5D6D7D8"))
    )
    (comp (ref "Q25")
      (value "MOS_N_D1_S1S2S3G4D5D6D7D8")
      (footprint "SMD_SOIC127P600X110-9AN")
      (fields
        (field (name "DB_PART_NUMBER") "TRA000001604")
        (field (name "DB_VALUE") "AP1RA03GMT-HF-3")
        (field (name "DB_MANUFACTURER_PART") "ADVANCED POWER ELECTRONICS CORP      AP1RA03GMT-HF-3")
        (field (name "DB_APPROVED_BY") "VSN")
      )
      (libsource (lib "Database_Libs1") (part "MOS_N_D1_S1S2S3G4D5D6D7D8"))
    )
    (comp (ref "Q26")
      (value "MOS_N_D1_S1S2S3G4D5D6D7D8")
      (footprint "SMD_SOIC127P600X110-9AN")
      (fields
        (field (name "DB_PART_NUMBER") "TRA000001604")
        (field (name "DB_VALUE") "AP1RA03GMT-HF-3")
        (field (name "DB_MANUFACTURER_PART") "ADVANCED POWER ELECTRONICS CORP      AP1RA03GMT-HF-3")
        (field (name "DB_APPROVED_BY") "VSN")
      )
      (libsource (lib "Database_Libs1") (part "MOS_N_D1_S1S2S3G4D5D6D7D8"))
    )
    (comp (ref "Q27")
      (value "MOS_N_D1_S1S2S3G4D5D6D7D8")
      (footprint "SMD_SOIC127P600X110-9AN")
      (fields
        (field (name "DB_PART_NUMBER") "TRA000001604")
        (field (name "DB_VALUE") "AP1RA03GMT-HF-3")
        (field (name "DB_MANUFACTURER_PART") "ADVANCED POWER ELECTRONICS CORP      AP1RA03GMT-HF-3")
        (field (name "DB_APPROVED_BY") "VSN")
      )
      (libsource (lib "Database_Libs1") (part "MOS_N_D1_S1S2S3G4D5D6D7D8"))
    )
    (comp (ref "Q28")
      (value "MOS_N_D1_S1S2S3G4D5D6D7D8")
      (footprint "SMD_SOIC127P600X110-9AN")
      (fields
        (field (name "DB_PART_NUMBER") "TRA000001604")
        (field (name "DB_VALUE") "AP1RA03GMT-HF-3")
        (field (name "DB_MANUFACTURER_PART") "ADVANCED POWER ELECTRONICS CORP      AP1RA03GMT-HF-3")
        (field (name "DB_APPROVED_BY") "VSN")
      )
      (libsource (lib "Database_Libs1") (part "MOS_N_D1_S1S2S3G4D5D6D7D8"))
    )
    (comp (ref "Q29")
      (value "MOS_N_D1_S1S2S3G4D5D6D7D8")
      (footprint "SMD_SOIC127P600X110-9AN")
      (fields
        (field (name "DB_PART_NUMBER") "TRA000001604")
        (field (name "DB_VALUE") "AP1RA03GMT-HF-3")
        (field (name "DB_MANUFACTURER_PART") "ADVANCED POWER ELECTRONICS CORP      AP1RA03GMT-HF-3")
        (field (name "DB_APPROVED_BY") "VSN")
      )
      (libsource (lib "Database_Libs1") (part "MOS_N_D1_S1S2S3G4D5D6D7D8"))
    )
    (comp (ref "Q30")
      (value "MOS_N_D1_S1S2S3G4D5D6D7D8")
      (footprint "SMD_SOIC127P600X110-9AN")
      (fields
        (field (name "DB_PART_NUMBER") "TRA000001604")
        (field (name "DB_VALUE") "AP1RA03GMT-HF-3")
        (field (name "DB_MANUFACTURER_PART") "ADVANCED POWER ELECTRONICS CORP      AP1RA03GMT-HF-3")
        (field (name "DB_APPROVED_BY") "VSN")
      )
      (libsource (lib "Database_Libs1") (part "MOS_N_D1_S1S2S3G4D5D6D7D8"))
    )
    (comp (ref "Q31")
      (value "MOS_N_D1_S1S2S3G4D5D6D7D8")
      (footprint "SMD_SOIC127P600X110-9AN")
      (fields
        (field (name "DB_PART_NUMBER") "TRA000001604")
        (field (name "DB_VALUE") "AP1RA03GMT-HF-3")
        (field (name "DB_MANUFACTURER_PART") "ADVANCED POWER ELECTRONICS CORP      AP1RA03GMT-HF-3")
        (field (name "DB_APPROVED_BY") "VSN")
      )
      (libsource (lib "Database_Libs1") (part "MOS_N_D1_S1S2S3G4D5D6D7D8"))
    )
    (comp (ref "Q32")
      (value "MOS_N_D1_S1S2S3G4D5D6D7D8")
      (footprint "SMD_SOIC127P600X110-9AN")
      (fields
        (field (name "DB_PART_NUMBER") "TRA000001604")
        (field (name "DB_VALUE") "AP1RA03GMT-HF-3")
        (field (name "DB_MANUFACTURER_PART") "ADVANCED POWER ELECTRONICS CORP      AP1RA03GMT-HF-3")
        (field (name "DB_APPROVED_BY") "VSN")
      )
      (libsource (lib "Database_Libs1") (part "MOS_N_D1_S1S2S3G4D5D6D7D8"))
    )
    (comp (ref "Q33")
      (value "MOS_N_D1_S1S2S3G4D5D6D7D8")
      (footprint "SMD_SOIC127P600X110-9AN")
      (fields
        (field (name "DB_PART_NUMBER") "TRA000001604")
        (field (name "DB_VALUE") "AP1RA03GMT-HF-3")
        (field (name "DB_MANUFACTURER_PART") "ADVANCED POWER ELECTRONICS CORP      AP1RA03GMT-HF-3")
        (field (name "DB_APPROVED_BY") "VSN")
      )
      (libsource (lib "Database_Libs1") (part "MOS_N_D1_S1S2S3G4D5D6D7D8"))
    )
    (comp (ref "Q34")
      (value "MOS_N_D1_S1S2S3G4D5D6D7D8")
      (footprint "SMD_SOIC127P600X110-9AN")
      (fields
        (field (name "DB_PART_NUMBER") "TRA000001604")
        (field (name "DB_VALUE") "AP1RA03GMT-HF-3")
        (field (name "DB_MANUFACTURER_PART") "ADVANCED POWER ELECTRONICS CORP      AP1RA03GMT-HF-3")
        (field (name "DB_APPROVED_BY") "VSN")
      )
      (libsource (lib "Database_Libs1") (part "MOS_N_D1_S1S2S3G4D5D6D7D8"))
    )
    (comp (ref "Q35")
      (value "MOS_N_D1_S1S2S3G4D5D6D7D8")
      (footprint "SMD_SOIC127P600X110-9AN")
      (fields
        (field (name "DB_PART_NUMBER") "TRA000001604")
        (field (name "DB_VALUE") "AP1RA03GMT-HF-3")
        (field (name "DB_MANUFACTURER_PART") "ADVANCED POWER ELECTRONICS CORP      AP1RA03GMT-HF-3")
        (field (name "DB_APPROVED_BY") "VSN")
      )
      (libsource (lib "Database_Libs1") (part "MOS_N_D1_S1S2S3G4D5D6D7D8"))
    )
    (comp (ref "Q36")
      (value "MOS_N_D1_S1S2S3G4D5D6D7D8")
      (footprint "SMD_SOIC127P600X110-9AN")
      (fields
        (field (name "DB_PART_NUMBER") "TRA000001604")
        (field (name "DB_VALUE") "AP1RA03GMT-HF-3")
        (field (name "DB_MANUFACTURER_PART") "ADVANCED POWER ELECTRONICS CORP      AP1RA03GMT-HF-3")
        (field (name "DB_APPROVED_BY") "VSN")
      )
      (libsource (lib "Database_Libs1") (part "MOS_N_D1_S1S2S3G4D5D6D7D8"))
    )
    (comp (ref "Q37")
      (value "MOS_N_D1_S1S2S3G4D5D6D7D8")
      (footprint "SMD_SOIC127P600X110-9AN")
      (fields
        (field (name "DB_PART_NUMBER") "TRA000001604")
        (field (name "DB_VALUE") "AP1RA03GMT-HF-3")
        (field (name "DB_MANUFACTURER_PART") "ADVANCED POWER ELECTRONICS CORP      AP1RA03GMT-HF-3")
        (field (name "DB_APPROVED_BY") "VSN")
      )
      (libsource (lib "Database_Libs1") (part "MOS_N_D1_S1S2S3G4D5D6D7D8"))
    )
    (comp (ref "Q38")
      (value "MOS_N_D1_S1S2S3G4D5D6D7D8")
      (footprint "SMD_SOIC127P600X110-9AN")
      (fields
        (field (name "DB_PART_NUMBER") "TRA000001604")
        (field (name "DB_VALUE") "AP1RA03GMT-HF-3")
        (field (name "DB_MANUFACTURER_PART") "ADVANCED POWER ELECTRONICS CORP      AP1RA03GMT-HF-3")
        (field (name "DB_APPROVED_BY") "VSN")
      )
      (libsource (lib "Database_Libs1") (part "MOS_N_D1_S1S2S3G4D5D6D7D8"))
    )
    (comp (ref "Q39")
      (value "MOS_N_D1_S1S2S3G4D5D6D7D8")
      (footprint "SMD_SOIC127P600X110-9AN")
      (fields
        (field (name "DB_PART_NUMBER") "TRA000001604")
        (field (name "DB_VALUE") "AP1RA03GMT-HF-3")
        (field (name "DB_MANUFACTURER_PART") "ADVANCED POWER ELECTRONICS CORP      AP1RA03GMT-HF-3")
        (field (name "DB_APPROVED_BY") "VSN")
      )
      (libsource (lib "Database_Libs1") (part "MOS_N_D1_S1S2S3G4D5D6D7D8"))
    )
    (comp (ref "Q40")
      (value "MOS_N_D1_S1S2S3G4D5D6D7D8")
      (footprint "SMD_SOIC127P600X110-9AN")
      (fields
        (field (name "DB_PART_NUMBER") "TRA000001604")
        (field (name "DB_VALUE") "AP1RA03GMT-HF-3")
        (field (name "DB_MANUFACTURER_PART") "ADVANCED POWER ELECTRONICS CORP      AP1RA03GMT-HF-3")
        (field (name "DB_APPROVED_BY") "VSN")
      )
      (libsource (lib "Database_Libs1") (part "MOS_N_D1_S1S2S3G4D5D6D7D8"))
    )
    (comp (ref "Q41")
      (value "MOS_N_D1_S1S2S3G4D5D6D7D8")
      (footprint "SMD_SOIC127P600X110-9AN")
      (fields
        (field (name "DB_PART_NUMBER") "TRA000001604")
        (field (name "DB_VALUE") "AP1RA03GMT-HF-3")
        (field (name "DB_MANUFACTURER_PART") "ADVANCED POWER ELECTRONICS CORP      AP1RA03GMT-HF-3")
        (field (name "DB_APPROVED_BY") "VSN")
      )
      (libsource (lib "Database_Libs1") (part "MOS_N_D1_S1S2S3G4D5D6D7D8"))
    )
    (comp (ref "Q42")
      (value "MOS_N_D1_S1S2S3G4D5D6D7D8")
      (footprint "SMD_SOIC127P600X110-9AN")
      (fields
        (field (name "DB_PART_NUMBER") "TRA000001604")
        (field (name "DB_VALUE") "AP1RA03GMT-HF-3")
        (field (name "DB_MANUFACTURER_PART") "ADVANCED POWER ELECTRONICS CORP      AP1RA03GMT-HF-3")
        (field (name "DB_APPROVED_BY") "VSN")
      )
      (libsource (lib "Database_Libs1") (part "MOS_N_D1_S1S2S3G4D5D6D7D8"))
    )
    (comp (ref "Q43")
      (value "MOS_N_D1_S1S2S3G4D5D6D7D8")
      (footprint "SMD_SOIC127P600X110-9AN")
      (fields
        (field (name "DB_PART_NUMBER") "TRA000001604")
        (field (name "DB_VALUE") "AP1RA03GMT-HF-3")
        (field (name "DB_MANUFACTURER_PART") "ADVANCED POWER ELECTRONICS CORP      AP1RA03GMT-HF-3")
        (field (name "DB_APPROVED_BY") "VSN")
      )
      (libsource (lib "Database_Libs1") (part "MOS_N_D1_S1S2S3G4D5D6D7D8"))
    )
    (comp (ref "Q44")
      (value "MOS_N_D1_S1S2S3G4D5D6D7D8")
      (footprint "SMD_SOIC127P600X110-9AN")
      (fields
        (field (name "DB_PART_NUMBER") "TRA000001604")
        (field (name "DB_VALUE") "AP1RA03GMT-HF-3")
        (field (name "DB_MANUFACTURER_PART") "ADVANCED POWER ELECTRONICS CORP      AP1RA03GMT-HF-3")
        (field (name "DB_APPROVED_BY") "VSN")
      )
      (libsource (lib "Database_Libs1") (part "MOS_N_D1_S1S2S3G4D5D6D7D8"))
    )
    (comp (ref "Q45")
      (value "MOS_N_D1_S1S2S3G4D5D6D7D8")
      (footprint "SMD_SOIC127P600X110-9AN")
      (fields
        (field (name "DB_PART_NUMBER") "TRA000001604")
        (field (name "DB_VALUE") "AP1RA03GMT-HF-3")
        (field (name "DB_MANUFACTURER_PART") "ADVANCED POWER ELECTRONICS CORP      AP1RA03GMT-HF-3")
        (field (name "DB_APPROVED_BY") "VSN")
      )
      (libsource (lib "Database_Libs1") (part "MOS_N_D1_S1S2S3G4D5D6D7D8"))
    )
    (comp (ref "Q46")
      (value "MOS_N_D1_S1S2S3G4D5D6D7D8")
      (footprint "SMD_SOIC127P600X110-9AN")
      (fields
        (field (name "DB_PART_NUMBER") "TRA000001604")
        (field (name "DB_VALUE") "AP1RA03GMT-HF-3")
        (field (name "DB_MANUFACTURER_PART") "ADVANCED POWER ELECTRONICS CORP      AP1RA03GMT-HF-3")
        (field (name "DB_APPROVED_BY") "VSN")
      )
      (libsource (lib "Database_Libs1") (part "MOS_N_D1_S1S2S3G4D5D6D7D8"))
    )
    (comp (ref "Q47")
      (value "MOS_N_D1_S1S2S3G4D5D6D7D8")
      (footprint "SMD_SOIC127P600X110-9AN")
      (fields
        (field (name "DB_PART_NUMBER") "TRA000001604")
        (field (name "DB_VALUE") "AP1RA03GMT-HF-3")
        (field (name "DB_MANUFACTURER_PART") "ADVANCED POWER ELECTRONICS CORP      AP1RA03GMT-HF-3")
        (field (name "DB_APPROVED_BY") "VSN")
      )
      (libsource (lib "Database_Libs1") (part "MOS_N_D1_S1S2S3G4D5D6D7D8"))
    )
    (comp (ref "Q48")
      (value "MOS_N_D1_S1S2S3G4D5D6D7D8")
      (footprint "SMD_SOIC127P600X110-9AN")
      (fields
        (field (name "DB_PART_NUMBER") "TRA000001604")
        (field (name "DB_VALUE") "AP1RA03GMT-HF-3")
        (field (name "DB_MANUFACTURER_PART") "ADVANCED POWER ELECTRONICS CORP      AP1RA03GMT-HF-3")
        (field (name "DB_APPROVED_BY") "VSN")
      )
      (libsource (lib "Database_Libs1") (part "MOS_N_D1_S1S2S3G4D5D6D7D8"))
    )
    (comp (ref "U11")
      (value "IC_LTC4449")
      (footprint "SMD_SON45P300X200X80-9N")
      (fields
        (field (name "DB_PART_NUMBER") "DRV000000079")
        (field (name "DB_VALUE") "LTC4449EDCB#TRPBF")
        (field (name "DB_MANUFACTURER_PART") "LINEAR       LTC4449EDCB#TRPBF")
        (field (name "DB_APPROVED_BY") "VSN")
      )
      (libsource (lib "Database_Libs1") (part "IC_LTC4449"))
    )
    (comp (ref "U12")
      (value "IC_LTC4449")
      (footprint "SMD_SON45P300X200X80-9N")
      (fields
        (field (name "DB_PART_NUMBER") "DRV000000079")
        (field (name "DB_VALUE") "LTC4449EDCB#TRPBF")
        (field (name "DB_MANUFACTURER_PART") "LINEAR       LTC4449EDCB#TRPBF")
        (field (name "DB_APPROVED_BY") "VSN")
      )
      (libsource (lib "Database_Libs1") (part "IC_LTC4449"))
    )
    (comp (ref "U13")
      (value "IC_LTC4449")
      (footprint "SMD_SON45P300X200X80-9N")
      (fields
        (field (name "DB_PART_NUMBER") "DRV000000079")
        (field (name "DB_VALUE") "LTC4449EDCB#TRPBF")
        (field (name "DB_MANUFACTURER_PART") "LINEAR       LTC4449EDCB#TRPBF")
        (field (name "DB_APPROVED_BY") "VSN")
      )
      (libsource (lib "Database_Libs1") (part "IC_LTC4449"))
    )
    (comp (ref "U14")
      (value "IC_LTC4449")
      (footprint "SMD_SON45P300X200X80-9N")
      (fields
        (field (name "DB_PART_NUMBER") "DRV000000079")
        (field (name "DB_VALUE") "LTC4449EDCB#TRPBF")
        (field (name "DB_MANUFACTURER_PART") "LINEAR       LTC4449EDCB#TRPBF")
        (field (name "DB_APPROVED_BY") "VSN")
      )
      (libsource (lib "Database_Libs1") (part "IC_LTC4449"))
    )
    (comp (ref "U15")
      (value "IC_LTC4449")
      (footprint "SMD_SON45P300X200X80-9N")
      (fields
        (field (name "DB_PART_NUMBER") "DRV000000079")
        (field (name "DB_VALUE") "LTC4449EDCB#TRPBF")
        (field (name "DB_MANUFACTURER_PART") "LINEAR       LTC4449EDCB#TRPBF")
        (field (name "DB_APPROVED_BY") "VSN")
      )
      (libsource (lib "Database_Libs1") (part "IC_LTC4449"))
    )
    (comp (ref "U16")
      (value "IC_LTC4449")
      (footprint "SMD_SON45P300X200X80-9N")
      (fields
        (field (name "DB_PART_NUMBER") "DRV000000079")
        (field (name "DB_VALUE") "LTC4449EDCB#TRPBF")
        (field (name "DB_MANUFACTURER_PART") "LINEAR       LTC4449EDCB#TRPBF")
        (field (name "DB_APPROVED_BY") "VSN")
      )
      (libsource (lib "Database_Libs1") (part "IC_LTC4449"))
    )
    (comp (ref "U17")
      (value "IC_LTC4449")
      (footprint "SMD_SON45P300X200X80-9N")
      (fields
        (field (name "DB_PART_NUMBER") "DRV000000079")
        (field (name "DB_VALUE") "LTC4449EDCB#TRPBF")
        (field (name "DB_MANUFACTURER_PART") "LINEAR       LTC4449EDCB#TRPBF")
        (field (name "DB_APPROVED_BY") "VSN")
      )
      (libsource (lib "Database_Libs1") (part "IC_LTC4449"))
    )
    (comp (ref "U18")
      (value "IC_LTC4449")
      (footprint "SMD_SON45P300X200X80-9N")
      (fields
        (field (name "DB_PART_NUMBER") "DRV000000079")
        (field (name "DB_VALUE") "LTC4449EDCB#TRPBF")
        (field (name "DB_MANUFACTURER_PART") "LINEAR       LTC4449EDCB#TRPBF")
        (field (name "DB_APPROVED_BY") "VSN")
      )
      (libsource (lib "Database_Libs1") (part "IC_LTC4449"))
    )
    (comp (ref "U19")
      (value "IC_LTC4449")
      (footprint "SMD_SON45P300X200X80-9N")
      (fields
        (field (name "DB_PART_NUMBER") "DRV000000079")
        (field (name "DB_VALUE") "LTC4449EDCB#TRPBF")
        (field (name "DB_MANUFACTURER_PART") "LINEAR       LTC4449EDCB#TRPBF")
        (field (name "DB_APPROVED_BY") "VSN")
      )
      (libsource (lib "Database_Libs1") (part "IC_LTC4449"))
    )
    (comp (ref "U20")
      (value "IC_LTC4449")
      (footprint "SMD_SON45P300X200X80-9N")
      (fields
        (field (name "DB_PART_NUMBER") "DRV000000079")
        (field (name "DB_VALUE") "LTC4449EDCB#TRPBF")
        (field (name "DB_MANUFACTURER_PART") "LINEAR       LTC4449EDCB#TRPBF")
        (field (name "DB_APPROVED_BY") "VSN")
      )
      (libsource (lib "Database_Libs1") (part "IC_LTC4449"))
    )
    (comp (ref "U21")
      (value "IC_LTC4449")
      (footprint "SMD_SON45P300X200X80-9N")
      (fields
        (field (name "DB_PART_NUMBER") "DRV000000079")
        (field (name "DB_VALUE") "LTC4449EDCB#TRPBF")
        (field (name "DB_MANUFACTURER_PART") "LINEAR       LTC4449EDCB#TRPBF")
        (field (name "DB_APPROVED_BY") "VSN")
      )
      (libsource (lib "Database_Libs1") (part "IC_LTC4449"))
    )
    (comp (ref "U22")
      (value "IC_LTC4449")
      (footprint "SMD_SON45P300X200X80-9N")
      (fields
        (field (name "DB_PART_NUMBER") "DRV000000079")
        (field (name "DB_VALUE") "LTC4449EDCB#TRPBF")
        (field (name "DB_MANUFACTURER_PART") "LINEAR       LTC4449EDCB#TRPBF")
        (field (name "DB_APPROVED_BY") "VSN")
      )
      (libsource (lib "Database_Libs1") (part "IC_LTC4449"))
    )
    (comp (ref "U23")
      (value "IC_LTC4449")
      (footprint "SMD_SON45P300X200X80-9N")
      (fields
        (field (name "DB_PART_NUMBER") "DRV000000079")
        (field (name "DB_VALUE") "LTC4449EDCB#TRPBF")
        (field (name "DB_MANUFACTURER_PART") "LINEAR       LTC4449EDCB#TRPBF")
        (field (name "DB_APPROVED_BY") "VSN")
      )
      (libsource (lib "Database_Libs1") (part "IC_LTC4449"))
    )
    (comp (ref "U24")
      (value "IC_LTC4449")
      (footprint "SMD_SON45P300X200X80-9N")
      (fields
        (field (name "DB_PART_NUMBER") "DRV000000079")
        (field (name "DB_VALUE") "LTC4449EDCB#TRPBF")
        (field (name "DB_MANUFACTURER_PART") "LINEAR       LTC4449EDCB#TRPBF")
        (field (name "DB_APPROVED_BY") "VSN")
      )
      (libsource (lib "Database_Libs1") (part "IC_LTC4449"))
    )
    (comp (ref "U25")
      (value "IC_LTC4449")
      (footprint "SMD_SON45P300X200X80-9N")
      (fields
        (field (name "DB_PART_NUMBER") "DRV000000079")
        (field (name "DB_VALUE") "LTC4449EDCB#TRPBF")
        (field (name "DB_MANUFACTURER_PART") "LINEAR       LTC4449EDCB#TRPBF")
        (field (name "DB_APPROVED_BY") "VSN")
      )
      (libsource (lib "Database_Libs1") (part "IC_LTC4449"))
    )
    (comp (ref "U26")
      (value "IC_LTC4449")
      (footprint "SMD_SON45P300X200X80-9N")
      (fields
        (field (name "DB_PART_NUMBER") "DRV000000079")
        (field (name "DB_VALUE") "LTC4449EDCB#TRPBF")
        (field (name "DB_MANUFACTURER_PART") "LINEAR       LTC4449EDCB#TRPBF")
        (field (name "DB_APPROVED_BY") "VSN")
      )
      (libsource (lib "Database_Libs1") (part "IC_LTC4449"))
    )
  )
  (nets
    (net (code "1") (name "/1V") (class "Default")
      (node (ref "C100") (pin "2") (pinfunction "2_2") (pintype "passive"))
      (node (ref "C103") (pin "2") (pinfunction "2_2") (pintype "passive"))
      (node (ref "C104") (pin "2") (pinfunction "2_2") (pintype "passive"))
      (node (ref "C105") (pin "2") (pinfunction "2_2") (pintype "passive"))
      (node (ref "C108") (pin "2") (pinfunction "2_2") (pintype "passive"))
      (node (ref "C109") (pin "2") (pinfunction "2_2") (pintype "passive"))
      (node (ref "C110") (pin "2") (pinfunction "2_2") (pintype "passive"))
      (node (ref "C113") (pin "2") (pinfunction "2_2") (pintype "passive"))
      (node (ref "C114") (pin "2") (pinfunction "2_2") (pintype "passive"))
      (node (ref "C115") (pin "2") (pinfunction "2_2") (pintype "passive"))
      (node (ref "C130") (pin "2") (pinfunction "2_2") (pintype "passive"))
      (node (ref "C131") (pin "2") (pinfunction "2_2") (pintype "passive"))
      (node (ref "C132") (pin "2") (pinfunction "2_2") (pintype "passive"))
      (node (ref "C135") (pin "2") (pinfunction "2_2") (pintype "passive"))
      (node (ref "C136") (pin "2") (pinfunction "2_2") (pintype "passive"))
      (node (ref "C137") (pin "2") (pinfunction "2_2") (pintype "passive"))
      (node (ref "C140") (pin "2") (pinfunction "2_2") (pintype "passive"))
      (node (ref "C141") (pin "2") (pinfunction "2_2") (pintype "passive"))
      (node (ref "C142") (pin "2") (pinfunction "2_2") (pintype "passive"))
      (node (ref "C145") (pin "2") (pinfunction "2_2") (pintype "passive"))
      (node (ref "C146") (pin "2") (pinfunction "2_2") (pintype "passive"))
      (node (ref "C147") (pin "2") (pinfunction "2_2") (pintype "passive"))
      (node (ref "C236") (pin "2") (pinfunction "2_2") (pintype "passive"))
      (node (ref "C34") (pin "2") (pinfunction "2_2") (pintype "passive"))
      (node (ref "C35") (pin "2") (pinfunction "2_2") (pintype "passive"))
      (node (ref "C350") (pin "2") (pinfunction "2_2") (pintype "passive"))
      (node (ref "C351") (pin "2") (pinfunction "2_2") (pintype "passive"))
      (node (ref "C352") (pin "2") (pinfunction "2_2") (pintype "passive"))
      (node (ref "C355") (pin "2") (pinfunction "2_2") (pintype "passive"))
      (node (ref "C356") (pin "2") (pinfunction "2_2") (pintype "passive"))
      (node (ref "C357") (pin "2") (pinfunction "2_2") (pintype "passive"))
      (node (ref "C360") (pin "2") (pinfunction "2_2") (pintype "passive"))
      (node (ref "C361") (pin "2") (pinfunction "2_2") (pintype "passive"))
      (node (ref "C362") (pin "2") (pinfunction "2_2") (pintype "passive"))
      (node (ref "C365") (pin "2") (pinfunction "2_2") (pintype "passive"))
      (node (ref "C366") (pin "2") (pinfunction "2_2") (pintype "passive"))
      (node (ref "C367") (pin "2") (pinfunction "2_2") (pintype "passive"))
      (node (ref "C370") (pin "2") (pinfunction "2_2") (pintype "passive"))
      (node (ref "C371") (pin "2") (pinfunction "2_2") (pintype "passive"))
      (node (ref "C372") (pin "2") (pinfunction "2_2") (pintype "passive"))
      (node (ref "C375") (pin "2") (pinfunction "2_2") (pintype "passive"))
      (node (ref "C376") (pin "2") (pinfunction "2_2") (pintype "passive"))
      (node (ref "C377") (pin "2") (pinfunction "2_2") (pintype "passive"))
      (node (ref "C380") (pin "2") (pinfunction "2_2") (pintype "passive"))
      (node (ref "C381") (pin "2") (pinfunction "2_2") (pintype "passive"))
      (node (ref "C382") (pin "2") (pinfunction "2_2") (pintype "passive"))
      (node (ref "C385") (pin "2") (pinfunction "2_2") (pintype "passive"))
      (node (ref "C386") (pin "2") (pinfunction "2_2") (pintype "passive"))
      (node (ref "C387") (pin "2") (pinfunction "2_2") (pintype "passive"))
      (node (ref "C388") (pin "2") (pinfunction "2_2") (pintype "passive"))
      (node (ref "C389") (pin "2") (pinfunction "2_2") (pintype "passive"))
      (node (ref "C39") (pin "2") (pinfunction "2_2") (pintype "passive"))
      (node (ref "C390") (pin "2") (pinfunction "2_2") (pintype "passive"))
      (node (ref "C393") (pin "2") (pinfunction "2_2") (pintype "passive"))
      (node (ref "C394") (pin "2") (pinfunction "2_2") (pintype "passive"))
      (node (ref "C395") (pin "2") (pinfunction "2_2") (pintype "passive"))
      (node (ref "C396") (pin "2") (pinfunction "2_2") (pintype "passive"))
      (node (ref "C397") (pin "2") (pinfunction "2_2") (pintype "passive"))
      (node (ref "C398") (pin "2") (pinfunction "2_2") (pintype "passive"))
      (node (ref "C399") (pin "2") (pinfunction "2_2") (pintype "passive"))
      (node (ref "C40") (pin "2") (pinfunction "2_2") (pintype "passive"))
      (node (ref "C400") (pin "2") (pinfunction "2_2") (pintype "passive"))
      (node (ref "C401") (pin "2") (pinfunction "2_2") (pintype "passive"))
      (node (ref "C408") (pin "2") (pinfunction "2_2") (pintype "passive"))
      (node (ref "C409") (pin "2") (pinfunction "2_2") (pintype "passive"))
      (node (ref "C41") (pin "2") (pinfunction "2_2") (pintype "passive"))
      (node (ref "C410") (pin "2") (pinfunction "2_2") (pintype "passive"))
      (node (ref "C411") (pin "2") (pinfunction "2_2") (pintype "passive"))
      (node (ref "C412") (pin "2") (pinfunction "2_2") (pintype "passive"))
      (node (ref "C413") (pin "2") (pinfunction "2_2") (pintype "passive"))
      (node (ref "C414") (pin "2") (pinfunction "2_2") (pintype "passive"))
      (node (ref "C415") (pin "2") (pinfunction "2_2") (pintype "passive"))
      (node (ref "C416") (pin "2") (pinfunction "2_2") (pintype "passive"))
      (node (ref "C417") (pin "2") (pinfunction "2_2") (pintype "passive"))
      (node (ref "C418") (pin "2") (pinfunction "2_2") (pintype "passive"))
      (node (ref "C419") (pin "2") (pinfunction "2_2") (pintype "passive"))
      (node (ref "C44") (pin "2") (pinfunction "2_2") (pintype "passive"))
      (node (ref "C45") (pin "2") (pinfunction "2_2") (pintype "passive"))
      (node (ref "C46") (pin "2") (pinfunction "2_2") (pintype "passive"))
      (node (ref "C49") (pin "2") (pinfunction "2_2") (pintype "passive"))
      (node (ref "C50") (pin "2") (pinfunction "2_2") (pintype "passive"))
      (node (ref "C51") (pin "2") (pinfunction "2_2") (pintype "passive"))
      (node (ref "C66") (pin "2") (pinfunction "2_2") (pintype "passive"))
      (node (ref "C67") (pin "2") (pinfunction "2_2") (pintype "passive"))
      (node (ref "C68") (pin "2") (pinfunction "2_2") (pintype "passive"))
      (node (ref "C71") (pin "2") (pinfunction "2_2") (pintype "passive"))
      (node (ref "C72") (pin "2") (pinfunction "2_2") (pintype "passive"))
      (node (ref "C73") (pin "2") (pinfunction "2_2") (pintype "passive"))
      (node (ref "C76") (pin "2") (pinfunction "2_2") (pintype "passive"))
      (node (ref "C77") (pin "2") (pinfunction "2_2") (pintype "passive"))
      (node (ref "C78") (pin "2") (pinfunction "2_2") (pintype "passive"))
      (node (ref "C81") (pin "2") (pinfunction "2_2") (pintype "passive"))
      (node (ref "C82") (pin "2") (pinfunction "2_2") (pintype "passive"))
      (node (ref "C83") (pin "2") (pinfunction "2_2") (pintype "passive"))
      (node (ref "C98") (pin "2") (pinfunction "2_2") (pintype "passive"))
      (node (ref "C99") (pin "2") (pinfunction "2_2") (pintype "passive"))
      (node (ref "L1") (pin "2") (pinfunction "2_2") (pintype "passive"))
      (node (ref "L10") (pin "2") (pinfunction "2_2") (pintype "passive"))
      (node (ref "L11") (pin "2") (pinfunction "2_2") (pintype "passive"))
      (node (ref "L12") (pin "2") (pinfunction "2_2") (pintype "passive"))
      (node (ref "L13") (pin "2") (pinfunction "2_2") (pintype "passive"))
      (node (ref "L14") (pin "2") (pinfunction "2_2") (pintype "passive"))
      (node (ref "L15") (pin "2") (pinfunction "2_2") (pintype "passive"))
      (node (ref "L16") (pin "2") (pinfunction "2_2") (pintype "passive"))
      (node (ref "L2") (pin "2") (pinfunction "2_2") (pintype "passive"))
      (node (ref "L3") (pin "2") (pinfunction "2_2") (pintype "passive"))
      (node (ref "L4") (pin "2") (pinfunction "2_2") (pintype "passive"))
      (node (ref "L5") (pin "2") (pinfunction "2_2") (pintype "passive"))
      (node (ref "L6") (pin "2") (pinfunction "2_2") (pintype "passive"))
      (node (ref "L7") (pin "2") (pinfunction "2_2") (pintype "passive"))
      (node (ref "L8") (pin "2") (pinfunction "2_2") (pintype "passive"))
      (node (ref "L9") (pin "2") (pinfunction "2_2") (pintype "passive"))
    )
    (net (code "2") (name "/3.3V") (class "Default")
      (node (ref "C120") (pin "1") (pinfunction "1_1") (pintype "passive"))
      (node (ref "C121") (pin "1") (pinfunction "1_1") (pintype "passive"))
      (node (ref "C122") (pin "1") (pinfunction "1_1") (pintype "passive"))
      (node (ref "C123") (pin "1") (pinfunction "1_1") (pintype "passive"))
      (node (ref "C24") (pin "1") (pinfunction "1_1") (pintype "passive"))
      (node (ref "C25") (pin "1") (pinfunction "1_1") (pintype "passive"))
      (node (ref "C26") (pin "1") (pinfunction "1_1") (pintype "passive"))
      (node (ref "C27") (pin "1") (pinfunction "1_1") (pintype "passive"))
      (node (ref "C56") (pin "1") (pinfunction "1_1") (pintype "passive"))
      (node (ref "C57") (pin "1") (pinfunction "1_1") (pintype "passive"))
      (node (ref "C58") (pin "1") (pinfunction "1_1") (pintype "passive"))
      (node (ref "C59") (pin "1") (pinfunction "1_1") (pintype "passive"))
      (node (ref "C88") (pin "1") (pinfunction "1_1") (pintype "passive"))
      (node (ref "C89") (pin "1") (pinfunction "1_1") (pintype "passive"))
      (node (ref "C90") (pin "1") (pinfunction "1_1") (pintype "passive"))
      (node (ref "C91") (pin "1") (pinfunction "1_1") (pintype "passive"))
      (node (ref "U11") (pin "6") (pinfunction "VLOGIC_6") (pintype "passive"))
      (node (ref "U12") (pin "6") (pinfunction "VLOGIC_6") (pintype "passive"))
      (node (ref "U13") (pin "6") (pinfunction "VLOGIC_6") (pintype "passive"))
      (node (ref "U14") (pin "6") (pinfunction "VLOGIC_6") (pintype "passive"))
      (node (ref "U15") (pin "6") (pinfunction "VLOGIC_6") (pintype "passive"))
      (node (ref "U16") (pin "6") (pinfunction "VLOGIC_6") (pintype "passive"))
      (node (ref "U17") (pin "6") (pinfunction "VLOGIC_6") (pintype "passive"))
      (node (ref "U18") (pin "6") (pinfunction "VLOGIC_6") (pintype "passive"))
      (node (ref "U19") (pin "6") (pinfunction "VLOGIC_6") (pintype "passive"))
      (node (ref "U20") (pin "6") (pinfunction "VLOGIC_6") (pintype "passive"))
      (node (ref "U21") (pin "6") (pinfunction "VLOGIC_6") (pintype "passive"))
      (node (ref "U22") (pin "6") (pinfunction "VLOGIC_6") (pintype "passive"))
      (node (ref "U23") (pin "6") (pinfunction "VLOGIC_6") (pintype "passive"))
      (node (ref "U24") (pin "6") (pinfunction "VLOGIC_6") (pintype "passive"))
      (node (ref "U25") (pin "6") (pinfunction "VLOGIC_6") (pintype "passive"))
      (node (ref "U26") (pin "6") (pinfunction "VLOGIC_6") (pintype "passive"))
    )
    (net (code "3") (name "/5.0V") (class "Default")
      (node (ref "C116") (pin "2") (pinfunction "2_2") (pintype "passive"))
      (node (ref "C117") (pin "2") (pinfunction "2_2") (pintype "passive"))
      (node (ref "C118") (pin "2") (pinfunction "2_2") (pintype "passive"))
      (node (ref "C119") (pin "2") (pinfunction "2_2") (pintype "passive"))
      (node (ref "C20") (pin "2") (pinfunction "2_2") (pintype "passive"))
      (node (ref "C21") (pin "2") (pinfunction "2_2") (pintype "passive"))
      (node (ref "C22") (pin "2") (pinfunction "2_2") (pintype "passive"))
      (node (ref "C23") (pin "2") (pinfunction "2_2") (pintype "passive"))
      (node (ref "C52") (pin "2") (pinfunction "2_2") (pintype "passive"))
      (node (ref "C53") (pin "2") (pinfunction "2_2") (pintype "passive"))
      (node (ref "C54") (pin "2") (pinfunction "2_2") (pintype "passive"))
      (node (ref "C55") (pin "2") (pinfunction "2_2") (pintype "passive"))
      (node (ref "C84") (pin "2") (pinfunction "2_2") (pintype "passive"))
      (node (ref "C85") (pin "2") (pinfunction "2_2") (pintype "passive"))
      (node (ref "C86") (pin "2") (pinfunction "2_2") (pintype "passive"))
      (node (ref "C87") (pin "2") (pinfunction "2_2") (pintype "passive"))
      (node (ref "D10") (pin "2") (pinfunction "A_2") (pintype "passive"))
      (node (ref "D11") (pin "2") (pinfunction "A_2") (pintype "passive"))
      (node (ref "D12") (pin "2") (pinfunction "A_2") (pintype "passive"))
      (node (ref "D13") (pin "2") (pinfunction "A_2") (pintype "passive"))
      (node (ref "D14") (pin "2") (pinfunction "A_2") (pintype "passive"))
      (node (ref "D15") (pin "2") (pinfunction "A_2") (pintype "passive"))
      (node (ref "D16") (pin "2") (pinfunction "A_2") (pintype "passive"))
      (node (ref "D17") (pin "2") (pinfunction "A_2") (pintype "passive"))
      (node (ref "D18") (pin "2") (pinfunction "A_2") (pintype "passive"))
      (node (ref "D19") (pin "2") (pinfunction "A_2") (pintype "passive"))
      (node (ref "D20") (pin "2") (pinfunction "A_2") (pintype "passive"))
      (node (ref "D21") (pin "2") (pinfunction "A_2") (pintype "passive"))
      (node (ref "D22") (pin "2") (pinfunction "A_2") (pintype "passive"))
      (node (ref "D23") (pin "2") (pinfunction "A_2") (pintype "passive"))
      (node (ref "D24") (pin "2") (pinfunction "A_2") (pintype "passive"))
      (node (ref "D25") (pin "2") (pinfunction "A_2") (pintype "passive"))
      (node (ref "U11") (pin "7") (pinfunction "VCC_7") (pintype "passive"))
      (node (ref "U12") (pin "7") (pinfunction "VCC_7") (pintype "passive"))
      (node (ref "U13") (pin "7") (pinfunction "VCC_7") (pintype "passive"))
      (node (ref "U14") (pin "7") (pinfunction "VCC_7") (pintype "passive"))
      (node (ref "U15") (pin "7") (pinfunction "VCC_7") (pintype "passive"))
      (node (ref "U16") (pin "7") (pinfunction "VCC_7") (pintype "passive"))
      (node (ref "U17") (pin "7") (pinfunction "VCC_7") (pintype "passive"))
      (node (ref "U18") (pin "7") (pinfunction "VCC_7") (pintype "passive"))
      (node (ref "U19") (pin "7") (pinfunction "VCC_7") (pintype "passive"))
      (node (ref "U20") (pin "7") (pinfunction "VCC_7") (pintype "passive"))
      (node (ref "U21") (pin "7") (pinfunction "VCC_7") (pintype "passive"))
      (node (ref "U22") (pin "7") (pinfunction "VCC_7") (pintype "passive"))
      (node (ref "U23") (pin "7") (pinfunction "VCC_7") (pintype "passive"))
      (node (ref "U24") (pin "7") (pinfunction "VCC_7") (pintype "passive"))
      (node (ref "U25") (pin "7") (pinfunction "VCC_7") (pintype "passive"))
      (node (ref "U26") (pin "7") (pinfunction "VCC_7") (pintype "passive"))
    )
    (net (code "4") (name "/12V") (class "Default")
      (node (ref "C101") (pin "2") (pinfunction "2_2") (pintype "passive"))
      (node (ref "C102") (pin "2") (pinfunction "2_2") (pintype "passive"))
      (node (ref "C106") (pin "2") (pinfunction "2_2") (pintype "passive"))
      (node (ref "C107") (pin "2") (pinfunction "2_2") (pintype "passive"))
      (node (ref "C111") (pin "2") (pinfunction "2_2") (pintype "passive"))
      (node (ref "C112") (pin "2") (pinfunction "2_2") (pintype "passive"))
      (node (ref "C128") (pin "2") (pinfunction "2_2") (pintype "passive"))
      (node (ref "C129") (pin "2") (pinfunction "2_2") (pintype "passive"))
      (node (ref "C133") (pin "2") (pinfunction "2_2") (pintype "passive"))
      (node (ref "C134") (pin "2") (pinfunction "2_2") (pintype "passive"))
      (node (ref "C138") (pin "2") (pinfunction "2_2") (pintype "passive"))
      (node (ref "C139") (pin "2") (pinfunction "2_2") (pintype "passive"))
      (node (ref "C143") (pin "2") (pinfunction "2_2") (pintype "passive"))
      (node (ref "C144") (pin "2") (pinfunction "2_2") (pintype "passive"))
      (node (ref "C32") (pin "2") (pinfunction "2_2") (pintype "passive"))
      (node (ref "C33") (pin "2") (pinfunction "2_2") (pintype "passive"))
      (node (ref "C348") (pin "2") (pinfunction "2_2") (pintype "passive"))
      (node (ref "C349") (pin "2") (pinfunction "2_2") (pintype "passive"))
      (node (ref "C353") (pin "2") (pinfunction "2_2") (pintype "passive"))
      (node (ref "C354") (pin "2") (pinfunction "2_2") (pintype "passive"))
      (node (ref "C358") (pin "2") (pinfunction "2_2") (pintype "passive"))
      (node (ref "C359") (pin "2") (pinfunction "2_2") (pintype "passive"))
      (node (ref "C363") (pin "2") (pinfunction "2_2") (pintype "passive"))
      (node (ref "C364") (pin "2") (pinfunction "2_2") (pintype "passive"))
      (node (ref "C368") (pin "2") (pinfunction "2_2") (pintype "passive"))
      (node (ref "C369") (pin "2") (pinfunction "2_2") (pintype "passive"))
      (node (ref "C37") (pin "2") (pinfunction "2_2") (pintype "passive"))
      (node (ref "C373") (pin "2") (pinfunction "2_2") (pintype "passive"))
      (node (ref "C374") (pin "2") (pinfunction "2_2") (pintype "passive"))
      (node (ref "C378") (pin "2") (pinfunction "2_2") (pintype "passive"))
      (node (ref "C379") (pin "2") (pinfunction "2_2") (pintype "passive"))
      (node (ref "C38") (pin "2") (pinfunction "2_2") (pintype "passive"))
      (node (ref "C383") (pin "2") (pinfunction "2_2") (pintype "passive"))
      (node (ref "C384") (pin "2") (pinfunction "2_2") (pintype "passive"))
      (node (ref "C391") (pin "2") (pinfunction "2_2") (pintype "passive"))
      (node (ref "C392") (pin "2") (pinfunction "2_2") (pintype "passive"))
      (node (ref "C402") (pin "2") (pinfunction "2_2") (pintype "passive"))
      (node (ref "C403") (pin "2") (pinfunction "2_2") (pintype "passive"))
      (node (ref "C404") (pin "2") (pinfunction "2_2") (pintype "passive"))
      (node (ref "C405") (pin "2") (pinfunction "2_2") (pintype "passive"))
      (node (ref "C406") (pin "2") (pinfunction "2_2") (pintype "passive"))
      (node (ref "C407") (pin "2") (pinfunction "2_2") (pintype "passive"))
      (node (ref "C42") (pin "2") (pinfunction "2_2") (pintype "passive"))
      (node (ref "C420") (pin "2") (pinfunction "2_2") (pintype "passive"))
      (node (ref "C421") (pin "2") (pinfunction "2_2") (pintype "passive"))
      (node (ref "C422") (pin "2") (pinfunction "2_2") (pintype "passive"))
      (node (ref "C423") (pin "2") (pinfunction "2_2") (pintype "passive"))
      (node (ref "C424") (pin "2") (pinfunction "2_2") (pintype "passive"))
      (node (ref "C425") (pin "2") (pinfunction "2_2") (pintype "passive"))
      (node (ref "C426") (pin "2") (pinfunction "2_2") (pintype "passive"))
      (node (ref "C427") (pin "2") (pinfunction "2_2") (pintype "passive"))
      (node (ref "C43") (pin "2") (pinfunction "2_2") (pintype "passive"))
      (node (ref "C47") (pin "2") (pinfunction "2_2") (pintype "passive"))
      (node (ref "C48") (pin "2") (pinfunction "2_2") (pintype "passive"))
      (node (ref "C64") (pin "2") (pinfunction "2_2") (pintype "passive"))
      (node (ref "C65") (pin "2") (pinfunction "2_2") (pintype "passive"))
      (node (ref "C69") (pin "2") (pinfunction "2_2") (pintype "passive"))
      (node (ref "C70") (pin "2") (pinfunction "2_2") (pintype "passive"))
      (node (ref "C74") (pin "2") (pinfunction "2_2") (pintype "passive"))
      (node (ref "C75") (pin "2") (pinfunction "2_2") (pintype "passive"))
      (node (ref "C79") (pin "2") (pinfunction "2_2") (pintype "passive"))
      (node (ref "C80") (pin "2") (pinfunction "2_2") (pintype "passive"))
      (node (ref "C96") (pin "2") (pinfunction "2_2") (pintype "passive"))
      (node (ref "C97") (pin "2") (pinfunction "2_2") (pintype "passive"))
      (node (ref "Q1") (pin "5") (pinfunction "D_5") (pintype "passive"))
      (node (ref "Q1") (pin "6") (pinfunction "D_6") (pintype "passive"))
      (node (ref "Q1") (pin "7") (pinfunction "D_7") (pintype "passive"))
      (node (ref "Q1") (pin "8") (pinfunction "D_8") (pintype "passive"))
      (node (ref "Q13") (pin "5") (pinfunction "D_5") (pintype "passive"))
      (node (ref "Q13") (pin "6") (pinfunction "D_6") (pintype "passive"))
      (node (ref "Q13") (pin "7") (pinfunction "D_7") (pintype "passive"))
      (node (ref "Q13") (pin "8") (pinfunction "D_8") (pintype "passive"))
      (node (ref "Q14") (pin "5") (pinfunction "D_5") (pintype "passive"))
      (node (ref "Q14") (pin "6") (pinfunction "D_6") (pintype "passive"))
      (node (ref "Q14") (pin "7") (pinfunction "D_7") (pintype "passive"))
      (node (ref "Q14") (pin "8") (pinfunction "D_8") (pintype "passive"))
      (node (ref "Q15") (pin "5") (pinfunction "D_5") (pintype "passive"))
      (node (ref "Q15") (pin "6") (pinfunction "D_6") (pintype "passive"))
      (node (ref "Q15") (pin "7") (pinfunction "D_7") (pintype "passive"))
      (node (ref "Q15") (pin "8") (pinfunction "D_8") (pintype "passive"))
      (node (ref "Q16") (pin "5") (pinfunction "D_5") (pintype "passive"))
      (node (ref "Q16") (pin "6") (pinfunction "D_6") (pintype "passive"))
      (node (ref "Q16") (pin "7") (pinfunction "D_7") (pintype "passive"))
      (node (ref "Q16") (pin "8") (pinfunction "D_8") (pintype "passive"))
      (node (ref "Q2") (pin "5") (pinfunction "D_5") (pintype "passive"))
      (node (ref "Q2") (pin "6") (pinfunction "D_6") (pintype "passive"))
      (node (ref "Q2") (pin "7") (pinfunction "D_7") (pintype "passive"))
      (node (ref "Q2") (pin "8") (pinfunction "D_8") (pintype "passive"))
      (node (ref "Q25") (pin "5") (pinfunction "D_5") (pintype "passive"))
      (node (ref "Q25") (pin "6") (pinfunction "D_6") (pintype "passive"))
      (node (ref "Q25") (pin "7") (pinfunction "D_7") (pintype "passive"))
      (node (ref "Q25") (pin "8") (pinfunction "D_8") (pintype "passive"))
      (node (ref "Q26") (pin "5") (pinfunction "D_5") (pintype "passive"))
      (node (ref "Q26") (pin "6") (pinfunction "D_6") (pintype "passive"))
      (node (ref "Q26") (pin "7") (pinfunction "D_7") (pintype "passive"))
      (node (ref "Q26") (pin "8") (pinfunction "D_8") (pintype "passive"))
      (node (ref "Q27") (pin "5") (pinfunction "D_5") (pintype "passive"))
      (node (ref "Q27") (pin "6") (pinfunction "D_6") (pintype "passive"))
      (node (ref "Q27") (pin "7") (pinfunction "D_7") (pintype "passive"))
      (node (ref "Q27") (pin "8") (pinfunction "D_8") (pintype "passive"))
      (node (ref "Q28") (pin "5") (pinfunction "D_5") (pintype "passive"))
      (node (ref "Q28") (pin "6") (pinfunction "D_6") (pintype "passive"))
      (node (ref "Q28") (pin "7") (pinfunction "D_7") (pintype "passive"))
      (node (ref "Q28") (pin "8") (pinfunction "D_8") (pintype "passive"))
      (node (ref "Q3") (pin "5") (pinfunction "D_5") (pintype "passive"))
      (node (ref "Q3") (pin "6") (pinfunction "D_6") (pintype "passive"))
      (node (ref "Q3") (pin "7") (pinfunction "D_7") (pintype "passive"))
      (node (ref "Q3") (pin "8") (pinfunction "D_8") (pintype "passive"))
      (node (ref "Q37") (pin "5") (pinfunction "D_5") (pintype "passive"))
      (node (ref "Q37") (pin "6") (pinfunction "D_6") (pintype "passive"))
      (node (ref "Q37") (pin "7") (pinfunction "D_7") (pintype "passive"))
      (node (ref "Q37") (pin "8") (pinfunction "D_8") (pintype "passive"))
      (node (ref "Q38") (pin "5") (pinfunction "D_5") (pintype "passive"))
      (node (ref "Q38") (pin "6") (pinfunction "D_6") (pintype "passive"))
      (node (ref "Q38") (pin "7") (pinfunction "D_7") (pintype "passive"))
      (node (ref "Q38") (pin "8") (pinfunction "D_8") (pintype "passive"))
      (node (ref "Q39") (pin "5") (pinfunction "D_5") (pintype "passive"))
      (node (ref "Q39") (pin "6") (pinfunction "D_6") (pintype "passive"))
      (node (ref "Q39") (pin "7") (pinfunction "D_7") (pintype "passive"))
      (node (ref "Q39") (pin "8") (pinfunction "D_8") (pintype "passive"))
      (node (ref "Q4") (pin "5") (pinfunction "D_5") (pintype "passive"))
      (node (ref "Q4") (pin "6") (pinfunction "D_6") (pintype "passive"))
      (node (ref "Q4") (pin "7") (pinfunction "D_7") (pintype "passive"))
      (node (ref "Q4") (pin "8") (pinfunction "D_8") (pintype "passive"))
      (node (ref "Q40") (pin "5") (pinfunction "D_5") (pintype "passive"))
      (node (ref "Q40") (pin "6") (pinfunction "D_6") (pintype "passive"))
      (node (ref "Q40") (pin "7") (pinfunction "D_7") (pintype "passive"))
      (node (ref "Q40") (pin "8") (pinfunction "D_8") (pintype "passive"))
    )
    (net (code "5") (name "/BOOT1") (class "Default")
      (node (ref "C28") (pin "1") (pinfunction "1_1") (pintype "passive"))
      (node (ref "D10") (pin "1") (pinfunction "C_1") (pintype "passive"))
      (node (ref "U11") (pin "8") (pinfunction "BOOST_8") (pintype "passive"))
    )
    (net (code "6") (name "/BOOT2") (class "Default")
      (node (ref "C60") (pin "1") (pinfunction "1_1") (pintype "passive"))
      (node (ref "D14") (pin "1") (pinfunction "C_1") (pintype "passive"))
      (node (ref "U15") (pin "8") (pinfunction "BOOST_8") (pintype "passive"))
    )
    (net (code "7") (name "/BOOT3") (class "Default")
      (node (ref "C92") (pin "1") (pinfunction "1_1") (pintype "passive"))
      (node (ref "D18") (pin "1") (pinfunction "C_1") (pintype "passive"))
      (node (ref "U19") (pin "8") (pinfunction "BOOST_8") (pintype "passive"))
    )
    (net (code "8") (name "/BOOT4") (class "Default")
      (node (ref "C124") (pin "1") (pinfunction "1_1") (pintype "passive"))
      (node (ref "D22") (pin "1") (pinfunction "C_1") (pintype "passive"))
      (node (ref "U23") (pin "8") (pinfunction "BOOST_8") (pintype "passive"))
    )
    (net (code "9") (name "/BOOT5") (class "Default")
      (node (ref "C29") (pin "1") (pinfunction "1_1") (pintype "passive"))
      (node (ref "D11") (pin "1") (pinfunction "C_1") (pintype "passive"))
      (node (ref "U12") (pin "8") (pinfunction "BOOST_8") (pintype "passive"))
    )
    (net (code "10") (name "/BOOT6") (class "Default")
      (node (ref "C61") (pin "1") (pinfunction "1_1") (pintype "passive"))
      (node (ref "D15") (pin "1") (pinfunction "C_1") (pintype "passive"))
      (node (ref "U16") (pin "8") (pinfunction "BOOST_8") (pintype "passive"))
    )
    (net (code "11") (name "/BOOT7") (class "Default")
      (node (ref "C93") (pin "1") (pinfunction "1_1") (pintype "passive"))
      (node (ref "D19") (pin "1") (pinfunction "C_1") (pintype "passive"))
      (node (ref "U20") (pin "8") (pinfunction "BOOST_8") (pintype "passive"))
    )
    (net (code "12") (name "/BOOT8") (class "Default")
      (node (ref "C125") (pin "1") (pinfunction "1_1") (pintype "passive"))
      (node (ref "D23") (pin "1") (pinfunction "C_1") (pintype "passive"))
      (node (ref "U24") (pin "8") (pinfunction "BOOST_8") (pintype "passive"))
    )
    (net (code "13") (name "/BOOT9") (class "Default")
      (node (ref "C30") (pin "1") (pinfunction "1_1") (pintype "passive"))
      (node (ref "D12") (pin "1") (pinfunction "C_1") (pintype "passive"))
      (node (ref "U13") (pin "8") (pinfunction "BOOST_8") (pintype "passive"))
    )
    (net (code "14") (name "/BOOT10") (class "Default")
      (node (ref "C62") (pin "1") (pinfunction "1_1") (pintype "passive"))
      (node (ref "D16") (pin "1") (pinfunction "C_1") (pintype "passive"))
      (node (ref "U17") (pin "8") (pinfunction "BOOST_8") (pintype "passive"))
    )
    (net (code "15") (name "/BOOT11") (class "Default")
      (node (ref "C94") (pin "1") (pinfunction "1_1") (pintype "passive"))
      (node (ref "D20") (pin "1") (pinfunction "C_1") (pintype "passive"))
      (node (ref "U21") (pin "8") (pinfunction "BOOST_8") (pintype "passive"))
    )
    (net (code "16") (name "/BOOT12") (class "Default")
      (node (ref "C126") (pin "1") (pinfunction "1_1") (pintype "passive"))
      (node (ref "D24") (pin "1") (pinfunction "C_1") (pintype "passive"))
      (node (ref "U25") (pin "8") (pinfunction "BOOST_8") (pintype "passive"))
    )
    (net (code "17") (name "/BOOT13") (class "Default")
      (node (ref "C31") (pin "1") (pinfunction "1_1") (pintype "passive"))
      (node (ref "D13") (pin "1") (pinfunction "C_1") (pintype "passive"))
      (node (ref "U14") (pin "8") (pinfunction "BOOST_8") (pintype "passive"))
    )
    (net (code "18") (name "/BOOT14") (class "Default")
      (node (ref "C63") (pin "1") (pinfunction "1_1") (pintype "passive"))
      (node (ref "D17") (pin "1") (pinfunction "C_1") (pintype "passive"))
      (node (ref "U18") (pin "8") (pinfunction "BOOST_8") (pintype "passive"))
    )
    (net (code "19") (name "/BOOT15") (class "Default")
      (node (ref "C95") (pin "1") (pinfunction "1_1") (pintype "passive"))
      (node (ref "D21") (pin "1") (pinfunction "C_1") (pintype "passive"))
      (node (ref "U22") (pin "8") (pinfunction "BOOST_8") (pintype "passive"))
    )
    (net (code "20") (name "/BOOT16") (class "Default")
      (node (ref "C127") (pin "1") (pinfunction "1_1") (pintype "passive"))
      (node (ref "D25") (pin "1") (pinfunction "C_1") (pintype "passive"))
      (node (ref "U26") (pin "8") (pinfunction "BOOST_8") (pintype "passive"))
    )
    (net (code "21") (name "/HO1") (class "Default")
      (node (ref "Q1") (pin "4") (pinfunction "G_4") (pintype "passive"))
      (node (ref "U11") (pin "1") (pinfunction "TG_1") (pintype "passive"))
    )
    (net (code "22") (name "/HO2") (class "Default")
      (node (ref "Q13") (pin "4") (pinfunction "G_4") (pintype "passive"))
      (node (ref "U15") (pin "1") (pinfunction "TG_1") (pintype "passive"))
    )
    (net (code "23") (name "/HO3") (class "Default")
      (node (ref "Q25") (pin "4") (pinfunction "G_4") (pintype "passive"))
      (node (ref "U19") (pin "1") (pinfunction "TG_1") (pintype "passive"))
    )
    (net (code "24") (name "/HO4") (class "Default")
      (node (ref "Q37") (pin "4") (pinfunction "G_4") (pintype "passive"))
      (node (ref "U23") (pin "1") (pinfunction "TG_1") (pintype "passive"))
    )
    (net (code "25") (name "/HO5") (class "Default")
      (node (ref "Q2") (pin "4") (pinfunction "G_4") (pintype "passive"))
      (node (ref "U12") (pin "1") (pinfunction "TG_1") (pintype "passive"))
    )
    (net (code "26") (name "/HO6") (class "Default")
      (node (ref "Q14") (pin "4") (pinfunction "G_4") (pintype "passive"))
      (node (ref "U16") (pin "1") (pinfunction "TG_1") (pintype "passive"))
    )
    (net (code "27") (name "/HO7") (class "Default")
      (node (ref "Q26") (pin "4") (pinfunction "G_4") (pintype "passive"))
      (node (ref "U20") (pin "1") (pinfunction "TG_1") (pintype "passive"))
    )
    (net (code "28") (name "/HO8") (class "Default")
      (node (ref "Q38") (pin "4") (pinfunction "G_4") (pintype "passive"))
      (node (ref "U24") (pin "1") (pinfunction "TG_1") (pintype "passive"))
    )
    (net (code "29") (name "/HO9") (class "Default")
      (node (ref "Q3") (pin "4") (pinfunction "G_4") (pintype "passive"))
      (node (ref "U13") (pin "1") (pinfunction "TG_1") (pintype "passive"))
    )
    (net (code "30") (name "/HO10") (class "Default")
      (node (ref "Q15") (pin "4") (pinfunction "G_4") (pintype "passive"))
      (node (ref "U17") (pin "1") (pinfunction "TG_1") (pintype "passive"))
    )
    (net (code "31") (name "/HO11") (class "Default")
      (node (ref "Q27") (pin "4") (pinfunction "G_4") (pintype "passive"))
      (node (ref "U21") (pin "1") (pinfunction "TG_1") (pintype "passive"))
    )
    (net (code "32") (name "/HO12") (class "Default")
      (node (ref "Q39") (pin "4") (pinfunction "G_4") (pintype "passive"))
      (node (ref "U25") (pin "1") (pinfunction "TG_1") (pintype "passive"))
    )
    (net (code "33") (name "/HO13") (class "Default")
      (node (ref "Q4") (pin "4") (pinfunction "G_4") (pintype "passive"))
      (node (ref "U14") (pin "1") (pinfunction "TG_1") (pintype "passive"))
    )
    (net (code "34") (name "/HO14") (class "Default")
      (node (ref "Q16") (pin "4") (pinfunction "G_4") (pintype "passive"))
      (node (ref "U18") (pin "1") (pinfunction "TG_1") (pintype "passive"))
    )
    (net (code "35") (name "/HO15") (class "Default")
      (node (ref "Q28") (pin "4") (pinfunction "G_4") (pintype "passive"))
      (node (ref "U22") (pin "1") (pinfunction "TG_1") (pintype "passive"))
    )
    (net (code "36") (name "/HO16") (class "Default")
      (node (ref "Q40") (pin "4") (pinfunction "G_4") (pintype "passive"))
      (node (ref "U26") (pin "1") (pinfunction "TG_1") (pintype "passive"))
    )
    (net (code "37") (name "/LO1") (class "Default")
      (node (ref "Q5") (pin "4") (pinfunction "G_4") (pintype "passive"))
      (node (ref "Q6") (pin "4") (pinfunction "G_4") (pintype "passive"))
      (node (ref "U11") (pin "3") (pinfunction "BG_3") (pintype "passive"))
    )
    (net (code "38") (name "/LO2") (class "Default")
      (node (ref "Q17") (pin "4") (pinfunction "G_4") (pintype "passive"))
      (node (ref "Q18") (pin "4") (pinfunction "G_4") (pintype "passive"))
      (node (ref "U15") (pin "3") (pinfunction "BG_3") (pintype "passive"))
    )
    (net (code "39") (name "/LO3") (class "Default")
      (node (ref "Q29") (pin "4") (pinfunction "G_4") (pintype "passive"))
      (node (ref "Q30") (pin "4") (pinfunction "G_4") (pintype "passive"))
      (node (ref "U19") (pin "3") (pinfunction "BG_3") (pintype "passive"))
    )
    (net (code "40") (name "/LO4") (class "Default")
      (node (ref "Q41") (pin "4") (pinfunction "G_4") (pintype "passive"))
      (node (ref "Q42") (pin "4") (pinfunction "G_4") (pintype "passive"))
      (node (ref "U23") (pin "3") (pinfunction "BG_3") (pintype "passive"))
    )
    (net (code "41") (name "/LO5") (class "Default")
      (node (ref "Q7") (pin "4") (pinfunction "G_4") (pintype "passive"))
      (node (ref "Q8") (pin "4") (pinfunction "G_4") (pintype "passive"))
      (node (ref "U12") (pin "3") (pinfunction "BG_3") (pintype "passive"))
    )
    (net (code "42") (name "/LO6") (class "Default")
      (node (ref "Q19") (pin "4") (pinfunction "G_4") (pintype "passive"))
      (node (ref "Q20") (pin "4") (pinfunction "G_4") (pintype "passive"))
      (node (ref "U16") (pin "3") (pinfunction "BG_3") (pintype "passive"))
    )
    (net (code "43") (name "/LO7") (class "Default")
      (node (ref "Q31") (pin "4") (pinfunction "G_4") (pintype "passive"))
      (node (ref "Q32") (pin "4") (pinfunction "G_4") (pintype "passive"))
      (node (ref "U20") (pin "3") (pinfunction "BG_3") (pintype "passive"))
    )
    (net (code "44") (name "/LO8") (class "Default")
      (node (ref "Q43") (pin "4") (pinfunction "G_4") (pintype "passive"))
      (node (ref "Q44") (pin "4") (pinfunction "G_4") (pintype "passive"))
      (node (ref "U24") (pin "3") (pinfunction "BG_3") (pintype "passive"))
    )
    (net (code "45") (name "/LO9") (class "Default")
      (node (ref "Q10") (pin "4") (pinfunction "G_4") (pintype "passive"))
      (node (ref "Q9") (pin "4") (pinfunction "G_4") (pintype "passive"))
      (node (ref "U13") (pin "3") (pinfunction "BG_3") (pintype "passive"))
    )
    (net (code "46") (name "/LO10") (class "Default")
      (node (ref "Q21") (pin "4") (pinfunction "G_4") (pintype "passive"))
      (node (ref "Q22") (pin "4") (pinfunction "G_4") (pintype "passive"))
      (node (ref "U17") (pin "3") (pinfunction "BG_3") (pintype "passive"))
    )
    (net (code "47") (name "/LO11") (class "Default")
      (node (ref "Q33") (pin "4") (pinfunction "G_4") (pintype "passive"))
      (node (ref "Q34") (pin "4") (pinfunction "G_4") (pintype "passive"))
      (node (ref "U21") (pin "3") (pinfunction "BG_3") (pintype "passive"))
    )
    (net (code "48") (name "/LO12") (class "Default")
      (node (ref "Q45") (pin "4") (pinfunction "G_4") (pintype "passive"))
      (node (ref "Q46") (pin "4") (pinfunction "G_4") (pintype "passive"))
      (node (ref "U25") (pin "3") (pinfunction "BG_3") (pintype "passive"))
    )
    (net (code "49") (name "/LO13") (class "Default")
      (node (ref "Q11") (pin "4") (pinfunction "G_4") (pintype "passive"))
      (node (ref "Q12") (pin "4") (pinfunction "G_4") (pintype "passive"))
      (node (ref "U14") (pin "3") (pinfunction "BG_3") (pintype "passive"))
    )
    (net (code "50") (name "/LO14") (class "Default")
      (node (ref "Q23") (pin "4") (pinfunction "G_4") (pintype "passive"))
      (node (ref "Q24") (pin "4") (pinfunction "G_4") (pintype "passive"))
      (node (ref "U18") (pin "3") (pinfunction "BG_3") (pintype "passive"))
    )
    (net (code "51") (name "/LO15") (class "Default")
      (node (ref "Q35") (pin "4") (pinfunction "G_4") (pintype "passive"))
      (node (ref "Q36") (pin "4") (pinfunction "G_4") (pintype "passive"))
      (node (ref "U22") (pin "3") (pinfunction "BG_3") (pintype "passive"))
    )
    (net (code "52") (name "/LO16") (class "Default")
      (node (ref "Q47") (pin "4") (pinfunction "G_4") (pintype "passive"))
      (node (ref "Q48") (pin "4") (pinfunction "G_4") (pintype "passive"))
      (node (ref "U26") (pin "3") (pinfunction "BG_3") (pintype "passive"))
    )
    (net (code "53") (name "/PWM1H") (class "Default")
      (node (ref "U12") (pin "5") (pinfunction "IN_5") (pintype "passive"))
      (node (ref "U14") (pin "5") (pinfunction "IN_5") (pintype "passive"))
    )
    (net (code "54") (name "/PWM1L") (class "Default")
      (node (ref "U11") (pin "5") (pinfunction "IN_5") (pintype "passive"))
      (node (ref "U13") (pin "5") (pinfunction "IN_5") (pintype "passive"))
    )
    (net (code "55") (name "/PWM2H") (class "Default")
      (node (ref "U16") (pin "5") (pinfunction "IN_5") (pintype "passive"))
      (node (ref "U18") (pin "5") (pinfunction "IN_5") (pintype "passive"))
    )
    (net (code "56") (name "/PWM2L") (class "Default")
      (node (ref "U15") (pin "5") (pinfunction "IN_5") (pintype "passive"))
      (node (ref "U17") (pin "5") (pinfunction "IN_5") (pintype "passive"))
    )
    (net (code "57") (name "/PWM3H") (class "Default")
      (node (ref "U20") (pin "5") (pinfunction "IN_5") (pintype "passive"))
      (node (ref "U22") (pin "5") (pinfunction "IN_5") (pintype "passive"))
    )
    (net (code "58") (name "/PWM3L") (class "Default")
      (node (ref "U19") (pin "5") (pinfunction "IN_5") (pintype "passive"))
      (node (ref "U21") (pin "5") (pinfunction "IN_5") (pintype "passive"))
    )
    (net (code "59") (name "/PWM4H") (class "Default")
      (node (ref "U24") (pin "5") (pinfunction "IN_5") (pintype "passive"))
      (node (ref "U26") (pin "5") (pinfunction "IN_5") (pintype "passive"))
    )
    (net (code "60") (name "/PWM4L") (class "Default")
      (node (ref "U23") (pin "5") (pinfunction "IN_5") (pintype "passive"))
      (node (ref "U25") (pin "5") (pinfunction "IN_5") (pintype "passive"))
    )
    (net (code "61") (name "/SWN1") (class "Default")
      (node (ref "C28") (pin "2") (pinfunction "2_2") (pintype "passive"))
      (node (ref "L1") (pin "1") (pinfunction "1_1") (pintype "passive"))
      (node (ref "Q1") (pin "1") (pinfunction "S_1") (pintype "passive"))
      (node (ref "Q1") (pin "2") (pinfunction "S_2") (pintype "passive"))
      (node (ref "Q1") (pin "3") (pinfunction "S_3") (pintype "passive"))
      (node (ref "Q5") (pin "5") (pinfunction "D_5") (pintype "passive"))
      (node (ref "Q5") (pin "6") (pinfunction "D_6") (pintype "passive"))
      (node (ref "Q5") (pin "7") (pinfunction "D_7") (pintype "passive"))
      (node (ref "Q5") (pin "8") (pinfunction "D_8") (pintype "passive"))
      (node (ref "Q6") (pin "5") (pinfunction "D_5") (pintype "passive"))
      (node (ref "Q6") (pin "6") (pinfunction "D_6") (pintype "passive"))
      (node (ref "Q6") (pin "7") (pinfunction "D_7") (pintype "passive"))
      (node (ref "Q6") (pin "8") (pinfunction "D_8") (pintype "passive"))
      (node (ref "U11") (pin "2") (pinfunction "TS_2") (pintype "passive"))
    )
    (net (code "62") (name "/SWN2") (class "Default")
      (node (ref "C60") (pin "2") (pinfunction "2_2") (pintype "passive"))
      (node (ref "L5") (pin "1") (pinfunction "1_1") (pintype "passive"))
      (node (ref "Q13") (pin "1") (pinfunction "S_1") (pintype "passive"))
      (node (ref "Q13") (pin "2") (pinfunction "S_2") (pintype "passive"))
      (node (ref "Q13") (pin "3") (pinfunction "S_3") (pintype "passive"))
      (node (ref "Q17") (pin "5") (pinfunction "D_5") (pintype "passive"))
      (node (ref "Q17") (pin "6") (pinfunction "D_6") (pintype "passive"))
      (node (ref "Q17") (pin "7") (pinfunction "D_7") (pintype "passive"))
      (node (ref "Q17") (pin "8") (pinfunction "D_8") (pintype "passive"))
      (node (ref "Q18") (pin "5") (pinfunction "D_5") (pintype "passive"))
      (node (ref "Q18") (pin "6") (pinfunction "D_6") (pintype "passive"))
      (node (ref "Q18") (pin "7") (pinfunction "D_7") (pintype "passive"))
      (node (ref "Q18") (pin "8") (pinfunction "D_8") (pintype "passive"))
      (node (ref "U15") (pin "2") (pinfunction "TS_2") (pintype "passive"))
    )
    (net (code "63") (name "/SWN3") (class "Default")
      (node (ref "C92") (pin "2") (pinfunction "2_2") (pintype "passive"))
      (node (ref "L9") (pin "1") (pinfunction "1_1") (pintype "passive"))
      (node (ref "Q25") (pin "1") (pinfunction "S_1") (pintype "passive"))
      (node (ref "Q25") (pin "2") (pinfunction "S_2") (pintype "passive"))
      (node (ref "Q25") (pin "3") (pinfunction "S_3") (pintype "passive"))
      (node (ref "Q29") (pin "5") (pinfunction "D_5") (pintype "passive"))
      (node (ref "Q29") (pin "6") (pinfunction "D_6") (pintype "passive"))
      (node (ref "Q29") (pin "7") (pinfunction "D_7") (pintype "passive"))
      (node (ref "Q29") (pin "8") (pinfunction "D_8") (pintype "passive"))
      (node (ref "Q30") (pin "5") (pinfunction "D_5") (pintype "passive"))
      (node (ref "Q30") (pin "6") (pinfunction "D_6") (pintype "passive"))
      (node (ref "Q30") (pin "7") (pinfunction "D_7") (pintype "passive"))
      (node (ref "Q30") (pin "8") (pinfunction "D_8") (pintype "passive"))
      (node (ref "U19") (pin "2") (pinfunction "TS_2") (pintype "passive"))
    )
    (net (code "64") (name "/SWN4") (class "Default")
      (node (ref "C124") (pin "2") (pinfunction "2_2") (pintype "passive"))
      (node (ref "L13") (pin "1") (pinfunction "1_1") (pintype "passive"))
      (node (ref "Q37") (pin "1") (pinfunction "S_1") (pintype "passive"))
      (node (ref "Q37") (pin "2") (pinfunction "S_2") (pintype "passive"))
      (node (ref "Q37") (pin "3") (pinfunction "S_3") (pintype "passive"))
      (node (ref "Q41") (pin "5") (pinfunction "D_5") (pintype "passive"))
      (node (ref "Q41") (pin "6") (pinfunction "D_6") (pintype "passive"))
      (node (ref "Q41") (pin "7") (pinfunction "D_7") (pintype "passive"))
      (node (ref "Q41") (pin "8") (pinfunction "D_8") (pintype "passive"))
      (node (ref "Q42") (pin "5") (pinfunction "D_5") (pintype "passive"))
      (node (ref "Q42") (pin "6") (pinfunction "D_6") (pintype "passive"))
      (node (ref "Q42") (pin "7") (pinfunction "D_7") (pintype "passive"))
      (node (ref "Q42") (pin "8") (pinfunction "D_8") (pintype "passive"))
      (node (ref "U23") (pin "2") (pinfunction "TS_2") (pintype "passive"))
    )
    (net (code "65") (name "/SWN5") (class "Default")
      (node (ref "C29") (pin "2") (pinfunction "2_2") (pintype "passive"))
      (node (ref "L2") (pin "1") (pinfunction "1_1") (pintype "passive"))
      (node (ref "Q2") (pin "1") (pinfunction "S_1") (pintype "passive"))
      (node (ref "Q2") (pin "2") (pinfunction "S_2") (pintype "passive"))
      (node (ref "Q2") (pin "3") (pinfunction "S_3") (pintype "passive"))
      (node (ref "Q7") (pin "5") (pinfunction "D_5") (pintype "passive"))
      (node (ref "Q7") (pin "6") (pinfunction "D_6") (pintype "passive"))
      (node (ref "Q7") (pin "7") (pinfunction "D_7") (pintype "passive"))
      (node (ref "Q7") (pin "8") (pinfunction "D_8") (pintype "passive"))
      (node (ref "Q8") (pin "5") (pinfunction "D_5") (pintype "passive"))
      (node (ref "Q8") (pin "6") (pinfunction "D_6") (pintype "passive"))
      (node (ref "Q8") (pin "7") (pinfunction "D_7") (pintype "passive"))
      (node (ref "Q8") (pin "8") (pinfunction "D_8") (pintype "passive"))
      (node (ref "U12") (pin "2") (pinfunction "TS_2") (pintype "passive"))
    )
    (net (code "66") (name "/SWN6") (class "Default")
      (node (ref "C61") (pin "2") (pinfunction "2_2") (pintype "passive"))
      (node (ref "L6") (pin "1") (pinfunction "1_1") (pintype "passive"))
      (node (ref "Q14") (pin "1") (pinfunction "S_1") (pintype "passive"))
      (node (ref "Q14") (pin "2") (pinfunction "S_2") (pintype "passive"))
      (node (ref "Q14") (pin "3") (pinfunction "S_3") (pintype "passive"))
      (node (ref "Q19") (pin "5") (pinfunction "D_5") (pintype "passive"))
      (node (ref "Q19") (pin "6") (pinfunction "D_6") (pintype "passive"))
      (node (ref "Q19") (pin "7") (pinfunction "D_7") (pintype "passive"))
      (node (ref "Q19") (pin "8") (pinfunction "D_8") (pintype "passive"))
      (node (ref "Q20") (pin "5") (pinfunction "D_5") (pintype "passive"))
      (node (ref "Q20") (pin "6") (pinfunction "D_6") (pintype "passive"))
      (node (ref "Q20") (pin "7") (pinfunction "D_7") (pintype "passive"))
      (node (ref "Q20") (pin "8") (pinfunction "D_8") (pintype "passive"))
      (node (ref "U16") (pin "2") (pinfunction "TS_2") (pintype "passive"))
    )
    (net (code "67") (name "/SWN7") (class "Default")
      (node (ref "C93") (pin "2") (pinfunction "2_2") (pintype "passive"))
      (node (ref "L10") (pin "1") (pinfunction "1_1") (pintype "passive"))
      (node (ref "Q26") (pin "1") (pinfunction "S_1") (pintype "passive"))
      (node (ref "Q26") (pin "2") (pinfunction "S_2") (pintype "passive"))
      (node (ref "Q26") (pin "3") (pinfunction "S_3") (pintype "passive"))
      (node (ref "Q31") (pin "5") (pinfunction "D_5") (pintype "passive"))
      (node (ref "Q31") (pin "6") (pinfunction "D_6") (pintype "passive"))
      (node (ref "Q31") (pin "7") (pinfunction "D_7") (pintype "passive"))
      (node (ref "Q31") (pin "8") (pinfunction "D_8") (pintype "passive"))
      (node (ref "Q32") (pin "5") (pinfunction "D_5") (pintype "passive"))
      (node (ref "Q32") (pin "6") (pinfunction "D_6") (pintype "passive"))
      (node (ref "Q32") (pin "7") (pinfunction "D_7") (pintype "passive"))
      (node (ref "Q32") (pin "8") (pinfunction "D_8") (pintype "passive"))
      (node (ref "U20") (pin "2") (pinfunction "TS_2") (pintype "passive"))
    )
    (net (code "68") (name "/SWN8") (class "Default")
      (node (ref "C125") (pin "2") (pinfunction "2_2") (pintype "passive"))
      (node (ref "L14") (pin "1") (pinfunction "1_1") (pintype "passive"))
      (node (ref "Q38") (pin "1") (pinfunction "S_1") (pintype "passive"))
      (node (ref "Q38") (pin "2") (pinfunction "S_2") (pintype "passive"))
      (node (ref "Q38") (pin "3") (pinfunction "S_3") (pintype "passive"))
      (node (ref "Q43") (pin "5") (pinfunction "D_5") (pintype "passive"))
      (node (ref "Q43") (pin "6") (pinfunction "D_6") (pintype "passive"))
      (node (ref "Q43") (pin "7") (pinfunction "D_7") (pintype "passive"))
      (node (ref "Q43") (pin "8") (pinfunction "D_8") (pintype "passive"))
      (node (ref "Q44") (pin "5") (pinfunction "D_5") (pintype "passive"))
      (node (ref "Q44") (pin "6") (pinfunction "D_6") (pintype "passive"))
      (node (ref "Q44") (pin "7") (pinfunction "D_7") (pintype "passive"))
      (node (ref "Q44") (pin "8") (pinfunction "D_8") (pintype "passive"))
      (node (ref "U24") (pin "2") (pinfunction "TS_2") (pintype "passive"))
    )
    (net (code "69") (name "/SWN9") (class "Default")
      (node (ref "C30") (pin "2") (pinfunction "2_2") (pintype "passive"))
      (node (ref "L3") (pin "1") (pinfunction "1_1") (pintype "passive"))
      (node (ref "Q10") (pin "5") (pinfunction "D_5") (pintype "passive"))
      (node (ref "Q10") (pin "6") (pinfunction "D_6") (pintype "passive"))
      (node (ref "Q10") (pin "7") (pinfunction "D_7") (pintype "passive"))
      (node (ref "Q10") (pin "8") (pinfunction "D_8") (pintype "passive"))
      (node (ref "Q3") (pin "1") (pinfunction "S_1") (pintype "passive"))
      (node (ref "Q3") (pin "2") (pinfunction "S_2") (pintype "passive"))
      (node (ref "Q3") (pin "3") (pinfunction "S_3") (pintype "passive"))
      (node (ref "Q9") (pin "5") (pinfunction "D_5") (pintype "passive"))
      (node (ref "Q9") (pin "6") (pinfunction "D_6") (pintype "passive"))
      (node (ref "Q9") (pin "7") (pinfunction "D_7") (pintype "passive"))
      (node (ref "Q9") (pin "8") (pinfunction "D_8") (pintype "passive"))
      (node (ref "U13") (pin "2") (pinfunction "TS_2") (pintype "passive"))
    )
    (net (code "70") (name "/SWN10") (class "Default")
      (node (ref "C62") (pin "2") (pinfunction "2_2") (pintype "passive"))
      (node (ref "L7") (pin "1") (pinfunction "1_1") (pintype "passive"))
      (node (ref "Q15") (pin "1") (pinfunction "S_1") (pintype "passive"))
      (node (ref "Q15") (pin "2") (pinfunction "S_2") (pintype "passive"))
      (node (ref "Q15") (pin "3") (pinfunction "S_3") (pintype "passive"))
      (node (ref "Q21") (pin "5") (pinfunction "D_5") (pintype "passive"))
      (node (ref "Q21") (pin "6") (pinfunction "D_6") (pintype "passive"))
      (node (ref "Q21") (pin "7") (pinfunction "D_7") (pintype "passive"))
      (node (ref "Q21") (pin "8") (pinfunction "D_8") (pintype "passive"))
      (node (ref "Q22") (pin "5") (pinfunction "D_5") (pintype "passive"))
      (node (ref "Q22") (pin "6") (pinfunction "D_6") (pintype "passive"))
      (node (ref "Q22") (pin "7") (pinfunction "D_7") (pintype "passive"))
      (node (ref "Q22") (pin "8") (pinfunction "D_8") (pintype "passive"))
      (node (ref "U17") (pin "2") (pinfunction "TS_2") (pintype "passive"))
    )
    (net (code "71") (name "/SWN11") (class "Default")
      (node (ref "C94") (pin "2") (pinfunction "2_2") (pintype "passive"))
      (node (ref "L11") (pin "1") (pinfunction "1_1") (pintype "passive"))
      (node (ref "Q27") (pin "1") (pinfunction "S_1") (pintype "passive"))
      (node (ref "Q27") (pin "2") (pinfunction "S_2") (pintype "passive"))
      (node (ref "Q27") (pin "3") (pinfunction "S_3") (pintype "passive"))
      (node (ref "Q33") (pin "5") (pinfunction "D_5") (pintype "passive"))
      (node (ref "Q33") (pin "6") (pinfunction "D_6") (pintype "passive"))
      (node (ref "Q33") (pin "7") (pinfunction "D_7") (pintype "passive"))
      (node (ref "Q33") (pin "8") (pinfunction "D_8") (pintype "passive"))
      (node (ref "Q34") (pin "5") (pinfunction "D_5") (pintype "passive"))
      (node (ref "Q34") (pin "6") (pinfunction "D_6") (pintype "passive"))
      (node (ref "Q34") (pin "7") (pinfunction "D_7") (pintype "passive"))
      (node (ref "Q34") (pin "8") (pinfunction "D_8") (pintype "passive"))
      (node (ref "U21") (pin "2") (pinfunction "TS_2") (pintype "passive"))
    )
    (net (code "72") (name "/SWN12") (class "Default")
      (node (ref "C126") (pin "2") (pinfunction "2_2") (pintype "passive"))
      (node (ref "L15") (pin "1") (pinfunction "1_1") (pintype "passive"))
      (node (ref "Q39") (pin "1") (pinfunction "S_1") (pintype "passive"))
      (node (ref "Q39") (pin "2") (pinfunction "S_2") (pintype "passive"))
      (node (ref "Q39") (pin "3") (pinfunction "S_3") (pintype "passive"))
      (node (ref "Q45") (pin "5") (pinfunction "D_5") (pintype "passive"))
      (node (ref "Q45") (pin "6") (pinfunction "D_6") (pintype "passive"))
      (node (ref "Q45") (pin "7") (pinfunction "D_7") (pintype "passive"))
      (node (ref "Q45") (pin "8") (pinfunction "D_8") (pintype "passive"))
      (node (ref "Q46") (pin "5") (pinfunction "D_5") (pintype "passive"))
      (node (ref "Q46") (pin "6") (pinfunction "D_6") (pintype "passive"))
      (node (ref "Q46") (pin "7") (pinfunction "D_7") (pintype "passive"))
      (node (ref "Q46") (pin "8") (pinfunction "D_8") (pintype "passive"))
      (node (ref "U25") (pin "2") (pinfunction "TS_2") (pintype "passive"))
    )
    (net (code "73") (name "/SWN13") (class "Default")
      (node (ref "C31") (pin "2") (pinfunction "2_2") (pintype "passive"))
      (node (ref "L4") (pin "1") (pinfunction "1_1") (pintype "passive"))
      (node (ref "Q11") (pin "5") (pinfunction "D_5") (pintype "passive"))
      (node (ref "Q11") (pin "6") (pinfunction "D_6") (pintype "passive"))
      (node (ref "Q11") (pin "7") (pinfunction "D_7") (pintype "passive"))
      (node (ref "Q11") (pin "8") (pinfunction "D_8") (pintype "passive"))
      (node (ref "Q12") (pin "5") (pinfunction "D_5") (pintype "passive"))
      (node (ref "Q12") (pin "6") (pinfunction "D_6") (pintype "passive"))
      (node (ref "Q12") (pin "7") (pinfunction "D_7") (pintype "passive"))
      (node (ref "Q12") (pin "8") (pinfunction "D_8") (pintype "passive"))
      (node (ref "Q4") (pin "1") (pinfunction "S_1") (pintype "passive"))
      (node (ref "Q4") (pin "2") (pinfunction "S_2") (pintype "passive"))
      (node (ref "Q4") (pin "3") (pinfunction "S_3") (pintype "passive"))
      (node (ref "U14") (pin "2") (pinfunction "TS_2") (pintype "passive"))
    )
    (net (code "74") (name "/SWN14") (class "Default")
      (node (ref "C63") (pin "2") (pinfunction "2_2") (pintype "passive"))
      (node (ref "L8") (pin "1") (pinfunction "1_1") (pintype "passive"))
      (node (ref "Q16") (pin "1") (pinfunction "S_1") (pintype "passive"))
      (node (ref "Q16") (pin "2") (pinfunction "S_2") (pintype "passive"))
      (node (ref "Q16") (pin "3") (pinfunction "S_3") (pintype "passive"))
      (node (ref "Q23") (pin "5") (pinfunction "D_5") (pintype "passive"))
      (node (ref "Q23") (pin "6") (pinfunction "D_6") (pintype "passive"))
      (node (ref "Q23") (pin "7") (pinfunction "D_7") (pintype "passive"))
      (node (ref "Q23") (pin "8") (pinfunction "D_8") (pintype "passive"))
      (node (ref "Q24") (pin "5") (pinfunction "D_5") (pintype "passive"))
      (node (ref "Q24") (pin "6") (pinfunction "D_6") (pintype "passive"))
      (node (ref "Q24") (pin "7") (pinfunction "D_7") (pintype "passive"))
      (node (ref "Q24") (pin "8") (pinfunction "D_8") (pintype "passive"))
      (node (ref "U18") (pin "2") (pinfunction "TS_2") (pintype "passive"))
    )
    (net (code "75") (name "/SWN15") (class "Default")
      (node (ref "C95") (pin "2") (pinfunction "2_2") (pintype "passive"))
      (node (ref "L12") (pin "1") (pinfunction "1_1") (pintype "passive"))
      (node (ref "Q28") (pin "1") (pinfunction "S_1") (pintype "passive"))
      (node (ref "Q28") (pin "2") (pinfunction "S_2") (pintype "passive"))
      (node (ref "Q28") (pin "3") (pinfunction "S_3") (pintype "passive"))
      (node (ref "Q35") (pin "5") (pinfunction "D_5") (pintype "passive"))
      (node (ref "Q35") (pin "6") (pinfunction "D_6") (pintype "passive"))
      (node (ref "Q35") (pin "7") (pinfunction "D_7") (pintype "passive"))
      (node (ref "Q35") (pin "8") (pinfunction "D_8") (pintype "passive"))
      (node (ref "Q36") (pin "5") (pinfunction "D_5") (pintype "passive"))
      (node (ref "Q36") (pin "6") (pinfunction "D_6") (pintype "passive"))
      (node (ref "Q36") (pin "7") (pinfunction "D_7") (pintype "passive"))
      (node (ref "Q36") (pin "8") (pinfunction "D_8") (pintype "passive"))
      (node (ref "U22") (pin "2") (pinfunction "TS_2") (pintype "passive"))
    )
    (net (code "76") (name "/SWN16") (class "Default")
      (node (ref "C127") (pin "2") (pinfunction "2_2") (pintype "passive"))
      (node (ref "L16") (pin "1") (pinfunction "1_1") (pintype "passive"))
      (node (ref "Q40") (pin "1") (pinfunction "S_1") (pintype "passive"))
      (node (ref "Q40") (pin "2") (pinfunction "S_2") (pintype "passive"))
      (node (ref "Q40") (pin "3") (pinfunction "S_3") (pintype "passive"))
      (node (ref "Q47") (pin "5") (pinfunction "D_5") (pintype "passive"))
      (node (ref "Q47") (pin "6") (pinfunction "D_6") (pintype "passive"))
      (node (ref "Q47") (pin "7") (pinfunction "D_7") (pintype "passive"))
      (node (ref "Q47") (pin "8") (pinfunction "D_8") (pintype "passive"))
      (node (ref "Q48") (pin "5") (pinfunction "D_5") (pintype "passive"))
      (node (ref "Q48") (pin "6") (pinfunction "D_6") (pintype "passive"))
      (node (ref "Q48") (pin "7") (pinfunction "D_7") (pintype "passive"))
      (node (ref "Q48") (pin "8") (pinfunction "D_8") (pintype "passive"))
      (node (ref "U26") (pin "2") (pinfunction "TS_2") (pintype "passive"))
    )
    (net (code "77") (name "GND") (class "Default")
      (node (ref "C100") (pin "1") (pinfunction "1_1") (pintype "passive"))
      (node (ref "C101") (pin "1") (pinfunction "1_1") (pintype "passive"))
      (node (ref "C102") (pin "1") (pinfunction "1_1") (pintype "passive"))
      (node (ref "C103") (pin "1") (pinfunction "1_1") (pintype "passive"))
      (node (ref "C104") (pin "1") (pinfunction "1_1") (pintype "passive"))
      (node (ref "C105") (pin "1") (pinfunction "1_1") (pintype "passive"))
      (node (ref "C106") (pin "1") (pinfunction "1_1") (pintype "passive"))
      (node (ref "C107") (pin "1") (pinfunction "1_1") (pintype "passive"))
      (node (ref "C108") (pin "1") (pinfunction "1_1") (pintype "passive"))
      (node (ref "C109") (pin "1") (pinfunction "1_1") (pintype "passive"))
      (node (ref "C110") (pin "1") (pinfunction "1_1") (pintype "passive"))
      (node (ref "C111") (pin "1") (pinfunction "1_1") (pintype "passive"))
      (node (ref "C112") (pin "1") (pinfunction "1_1") (pintype "passive"))
      (node (ref "C113") (pin "1") (pinfunction "1_1") (pintype "passive"))
      (node (ref "C114") (pin "1") (pinfunction "1_1") (pintype "passive"))
      (node (ref "C115") (pin "1") (pinfunction "1_1") (pintype "passive"))
      (node (ref "C116") (pin "1") (pinfunction "1_1") (pintype "passive"))
      (node (ref "C117") (pin "1") (pinfunction "1_1") (pintype "passive"))
      (node (ref "C118") (pin "1") (pinfunction "1_1") (pintype "passive"))
      (node (ref "C119") (pin "1") (pinfunction "1_1") (pintype "passive"))
      (node (ref "C120") (pin "2") (pinfunction "2_2") (pintype "passive"))
      (node (ref "C121") (pin "2") (pinfunction "2_2") (pintype "passive"))
      (node (ref "C122") (pin "2") (pinfunction "2_2") (pintype "passive"))
      (node (ref "C123") (pin "2") (pinfunction "2_2") (pintype "passive"))
      (node (ref "C128") (pin "1") (pinfunction "1_1") (pintype "passive"))
      (node (ref "C129") (pin "1") (pinfunction "1_1") (pintype "passive"))
      (node (ref "C130") (pin "1") (pinfunction "1_1") (pintype "passive"))
      (node (ref "C131") (pin "1") (pinfunction "1_1") (pintype "passive"))
      (node (ref "C132") (pin "1") (pinfunction "1_1") (pintype "passive"))
      (node (ref "C133") (pin "1") (pinfunction "1_1") (pintype "passive"))
      (node (ref "C134") (pin "1") (pinfunction "1_1") (pintype "passive"))
      (node (ref "C135") (pin "1") (pinfunction "1_1") (pintype "passive"))
      (node (ref "C136") (pin "1") (pinfunction "1_1") (pintype "passive"))
      (node (ref "C137") (pin "1") (pinfunction "1_1") (pintype "passive"))
      (node (ref "C138") (pin "1") (pinfunction "1_1") (pintype "passive"))
      (node (ref "C139") (pin "1") (pinfunction "1_1") (pintype "passive"))
      (node (ref "C140") (pin "1") (pinfunction "1_1") (pintype "passive"))
      (node (ref "C141") (pin "1") (pinfunction "1_1") (pintype "passive"))
      (node (ref "C142") (pin "1") (pinfunction "1_1") (pintype "passive"))
      (node (ref "C143") (pin "1") (pinfunction "1_1") (pintype "passive"))
      (node (ref "C144") (pin "1") (pinfunction "1_1") (pintype "passive"))
      (node (ref "C145") (pin "1") (pinfunction "1_1") (pintype "passive"))
      (node (ref "C146") (pin "1") (pinfunction "1_1") (pintype "passive"))
      (node (ref "C147") (pin "1") (pinfunction "1_1") (pintype "passive"))
      (node (ref "C20") (pin "1") (pinfunction "1_1") (pintype "passive"))
      (node (ref "C21") (pin "1") (pinfunction "1_1") (pintype "passive"))
      (node (ref "C22") (pin "1") (pinfunction "1_1") (pintype "passive"))
      (node (ref "C23") (pin "1") (pinfunction "1_1") (pintype "passive"))
      (node (ref "C236") (pin "1") (pinfunction "1_1") (pintype "passive"))
      (node (ref "C24") (pin "2") (pinfunction "2_2") (pintype "passive"))
      (node (ref "C25") (pin "2") (pinfunction "2_2") (pintype "passive"))
      (node (ref "C26") (pin "2") (pinfunction "2_2") (pintype "passive"))
      (node (ref "C27") (pin "2") (pinfunction "2_2") (pintype "passive"))
      (node (ref "C32") (pin "1") (pinfunction "1_1") (pintype "passive"))
      (node (ref "C33") (pin "1") (pinfunction "1_1") (pintype "passive"))
      (node (ref "C34") (pin "1") (pinfunction "1_1") (pintype "passive"))
      (node (ref "C348") (pin "1") (pinfunction "1_1") (pintype "passive"))
      (node (ref "C349") (pin "1") (pinfunction "1_1") (pintype "passive"))
      (node (ref "C35") (pin "1") (pinfunction "1_1") (pintype "passive"))
      (node (ref "C350") (pin "1") (pinfunction "1_1") (pintype "passive"))
      (node (ref "C351") (pin "1") (pinfunction "1_1") (pintype "passive"))
      (node (ref "C352") (pin "1") (pinfunction "1_1") (pintype "passive"))
      (node (ref "C353") (pin "1") (pinfunction "1_1") (pintype "passive"))
      (node (ref "C354") (pin "1") (pinfunction "1_1") (pintype "passive"))
      (node (ref "C355") (pin "1") (pinfunction "1_1") (pintype "passive"))
      (node (ref "C356") (pin "1") (pinfunction "1_1") (pintype "passive"))
      (node (ref "C357") (pin "1") (pinfunction "1_1") (pintype "passive"))
      (node (ref "C358") (pin "1") (pinfunction "1_1") (pintype "passive"))
      (node (ref "C359") (pin "1") (pinfunction "1_1") (pintype "passive"))
      (node (ref "C360") (pin "1") (pinfunction "1_1") (pintype "passive"))
      (node (ref "C361") (pin "1") (pinfunction "1_1") (pintype "passive"))
      (node (ref "C362") (pin "1") (pinfunction "1_1") (pintype "passive"))
      (node (ref "C363") (pin "1") (pinfunction "1_1") (pintype "passive"))
      (node (ref "C364") (pin "1") (pinfunction "1_1") (pintype "passive"))
      (node (ref "C365") (pin "1") (pinfunction "1_1") (pintype "passive"))
      (node (ref "C366") (pin "1") (pinfunction "1_1") (pintype "passive"))
      (node (ref "C367") (pin "1") (pinfunction "1_1") (pintype "passive"))
      (node (ref "C368") (pin "1") (pinfunction "1_1") (pintype "passive"))
      (node (ref "C369") (pin "1") (pinfunction "1_1") (pintype "passive"))
      (node (ref "C37") (pin "1") (pinfunction "1_1") (pintype "passive"))
      (node (ref "C370") (pin "1") (pinfunction "1_1") (pintype "passive"))
      (node (ref "C371") (pin "1") (pinfunction "1_1") (pintype "passive"))
      (node (ref "C372") (pin "1") (pinfunction "1_1") (pintype "passive"))
      (node (ref "C373") (pin "1") (pinfunction "1_1") (pintype "passive"))
      (node (ref "C374") (pin "1") (pinfunction "1_1") (pintype "passive"))
      (node (ref "C375") (pin "1") (pinfunction "1_1") (pintype "passive"))
      (node (ref "C376") (pin "1") (pinfunction "1_1") (pintype "passive"))
      (node (ref "C377") (pin "1") (pinfunction "1_1") (pintype "passive"))
      (node (ref "C378") (pin "1") (pinfunction "1_1") (pintype "passive"))
      (node (ref "C379") (pin "1") (pinfunction "1_1") (pintype "passive"))
      (node (ref "C38") (pin "1") (pinfunction "1_1") (pintype "passive"))
      (node (ref "C380") (pin "1") (pinfunction "1_1") (pintype "passive"))
      (node (ref "C381") (pin "1") (pinfunction "1_1") (pintype "passive"))
      (node (ref "C382") (pin "1") (pinfunction "1_1") (pintype "passive"))
      (node (ref "C383") (pin "1") (pinfunction "1_1") (pintype "passive"))
      (node (ref "C384") (pin "1") (pinfunction "1_1") (pintype "passive"))
      (node (ref "C385") (pin "1") (pinfunction "1_1") (pintype "passive"))
      (node (ref "C386") (pin "1") (pinfunction "1_1") (pintype "passive"))
      (node (ref "C387") (pin "1") (pinfunction "1_1") (pintype "passive"))
      (node (ref "C388") (pin "1") (pinfunction "1_1") (pintype "passive"))
      (node (ref "C389") (pin "1") (pinfunction "1_1") (pintype "passive"))
      (node (ref "C39") (pin "1") (pinfunction "1_1") (pintype "passive"))
      (node (ref "C390") (pin "1") (pinfunction "1_1") (pintype "passive"))
      (node (ref "C391") (pin "1") (pinfunction "1_1") (pintype "passive"))
      (node (ref "C392") (pin "1") (pinfunction "1_1") (pintype "passive"))
      (node (ref "C393") (pin "1") (pinfunction "1_1") (pintype "passive"))
      (node (ref "C394") (pin "1") (pinfunction "1_1") (pintype "passive"))
      (node (ref "C395") (pin "1") (pinfunction "1_1") (pintype "passive"))
      (node (ref "C396") (pin "1") (pinfunction "1_1") (pintype "passive"))
      (node (ref "C397") (pin "1") (pinfunction "1_1") (pintype "passive"))
      (node (ref "C398") (pin "1") (pinfunction "1_1") (pintype "passive"))
      (node (ref "C399") (pin "1") (pinfunction "1_1") (pintype "passive"))
      (node (ref "C40") (pin "1") (pinfunction "1_1") (pintype "passive"))
      (node (ref "C400") (pin "1") (pinfunction "1_1") (pintype "passive"))
      (node (ref "C401") (pin "1") (pinfunction "1_1") (pintype "passive"))
      (node (ref "C402") (pin "1") (pinfunction "1_1") (pintype "passive"))
      (node (ref "C403") (pin "1") (pinfunction "1_1") (pintype "passive"))
      (node (ref "C404") (pin "1") (pinfunction "1_1") (pintype "passive"))
      (node (ref "C405") (pin "1") (pinfunction "1_1") (pintype "passive"))
      (node (ref "C406") (pin "1") (pinfunction "1_1") (pintype "passive"))
      (node (ref "C407") (pin "1") (pinfunction "1_1") (pintype "passive"))
      (node (ref "C408") (pin "1") (pinfunction "1_1") (pintype "passive"))
      (node (ref "C409") (pin "1") (pinfunction "1_1") (pintype "passive"))
      (node (ref "C41") (pin "1") (pinfunction "1_1") (pintype "passive"))
      (node (ref "C410") (pin "1") (pinfunction "1_1") (pintype "passive"))
      (node (ref "C411") (pin "1") (pinfunction "1_1") (pintype "passive"))
      (node (ref "C412") (pin "1") (pinfunction "1_1") (pintype "passive"))
      (node (ref "C413") (pin "1") (pinfunction "1_1") (pintype "passive"))
      (node (ref "C414") (pin "1") (pinfunction "1_1") (pintype "passive"))
      (node (ref "C415") (pin "1") (pinfunction "1_1") (pintype "passive"))
      (node (ref "C416") (pin "1") (pinfunction "1_1") (pintype "passive"))
      (node (ref "C417") (pin "1") (pinfunction "1_1") (pintype "passive"))
      (node (ref "C418") (pin "1") (pinfunction "1_1") (pintype "passive"))
      (node (ref "C419") (pin "1") (pinfunction "1_1") (pintype "passive"))
      (node (ref "C42") (pin "1") (pinfunction "1_1") (pintype "passive"))
      (node (ref "C420") (pin "1") (pinfunction "1_1") (pintype "passive"))
      (node (ref "C421") (pin "1") (pinfunction "1_1") (pintype "passive"))
      (node (ref "C422") (pin "1") (pinfunction "1_1") (pintype "passive"))
      (node (ref "C423") (pin "1") (pinfunction "1_1") (pintype "passive"))
      (node (ref "C424") (pin "1") (pinfunction "1_1") (pintype "passive"))
      (node (ref "C425") (pin "1") (pinfunction "1_1") (pintype "passive"))
      (node (ref "C426") (pin "1") (pinfunction "1_1") (pintype "passive"))
      (node (ref "C427") (pin "1") (pinfunction "1_1") (pintype "passive"))
      (node (ref "C43") (pin "1") (pinfunction "1_1") (pintype "passive"))
      (node (ref "C44") (pin "1") (pinfunction "1_1") (pintype "passive"))
      (node (ref "C45") (pin "1") (pinfunction "1_1") (pintype "passive"))
      (node (ref "C46") (pin "1") (pinfunction "1_1") (pintype "passive"))
      (node (ref "C47") (pin "1") (pinfunction "1_1") (pintype "passive"))
      (node (ref "C48") (pin "1") (pinfunction "1_1") (pintype "passive"))
      (node (ref "C49") (pin "1") (pinfunction "1_1") (pintype "passive"))
      (node (ref "C50") (pin "1") (pinfunction "1_1") (pintype "passive"))
      (node (ref "C51") (pin "1") (pinfunction "1_1") (pintype "passive"))
      (node (ref "C52") (pin "1") (pinfunction "1_1") (pintype "passive"))
      (node (ref "C53") (pin "1") (pinfunction "1_1") (pintype "passive"))
      (node (ref "C54") (pin "1") (pinfunction "1_1") (pintype "passive"))
      (node (ref "C55") (pin "1") (pinfunction "1_1") (pintype "passive"))
      (node (ref "C56") (pin "2") (pinfunction "2_2") (pintype "passive"))
      (node (ref "C57") (pin "2") (pinfunction "2_2") (pintype "passive"))
      (node (ref "C58") (pin "2") (pinfunction "2_2") (pintype "passive"))
      (node (ref "C59") (pin "2") (pinfunction "2_2") (pintype "passive"))
      (node (ref "C64") (pin "1") (pinfunction "1_1") (pintype "passive"))
      (node (ref "C65") (pin "1") (pinfunction "1_1") (pintype "passive"))
      (node (ref "C66") (pin "1") (pinfunction "1_1") (pintype "passive"))
      (node (ref "C67") (pin "1") (pinfunction "1_1") (pintype "passive"))
      (node (ref "C68") (pin "1") (pinfunction "1_1") (pintype "passive"))
      (node (ref "C69") (pin "1") (pinfunction "1_1") (pintype "passive"))
      (node (ref "C70") (pin "1") (pinfunction "1_1") (pintype "passive"))
      (node (ref "C71") (pin "1") (pinfunction "1_1") (pintype "passive"))
      (node (ref "C72") (pin "1") (pinfunction "1_1") (pintype "passive"))
      (node (ref "C73") (pin "1") (pinfunction "1_1") (pintype "passive"))
      (node (ref "C74") (pin "1") (pinfunction "1_1") (pintype "passive"))
      (node (ref "C75") (pin "1") (pinfunction "1_1") (pintype "passive"))
      (node (ref "C76") (pin "1") (pinfunction "1_1") (pintype "passive"))
      (node (ref "C77") (pin "1") (pinfunction "1_1") (pintype "passive"))
      (node (ref "C78") (pin "1") (pinfunction "1_1") (pintype "passive"))
      (node (ref "C79") (pin "1") (pinfunction "1_1") (pintype "passive"))
      (node (ref "C80") (pin "1") (pinfunction "1_1") (pintype "passive"))
      (node (ref "C81") (pin "1") (pinfunction "1_1") (pintype "passive"))
      (node (ref "C82") (pin "1") (pinfunction "1_1") (pintype "passive"))
      (node (ref "C83") (pin "1") (pinfunction "1_1") (pintype "passive"))
      (node (ref "C84") (pin "1") (pinfunction "1_1") (pintype "passive"))
      (node (ref "C85") (pin "1") (pinfunction "1_1") (pintype "passive"))
      (node (ref "C86") (pin "1") (pinfunction "1_1") (pintype "passive"))
      (node (ref "C87") (pin "1") (pinfunction "1_1") (pintype "passive"))
      (node (ref "C88") (pin "2") (pinfunction "2_2") (pintype "passive"))
      (node (ref "C89") (pin "2") (pinfunction "2_2") (pintype "passive"))
      (node (ref "C90") (pin "2") (pinfunction "2_2") (pintype "passive"))
      (node (ref "C91") (pin "2") (pinfunction "2_2") (pintype "passive"))
      (node (ref "C96") (pin "1") (pinfunction "1_1") (pintype "passive"))
      (node (ref "C97") (pin "1") (pinfunction "1_1") (pintype "passive"))
      (node (ref "C98") (pin "1") (pinfunction "1_1") (pintype "passive"))
      (node (ref "C99") (pin "1") (pinfunction "1_1") (pintype "passive"))
      (node (ref "Q10") (pin "1") (pinfunction "S_1") (pintype "passive"))
      (node (ref "Q10") (pin "2") (pinfunction "S_2") (pintype "passive"))
      (node (ref "Q10") (pin "3") (pinfunction "S_3") (pintype "passive"))
      (node (ref "Q11") (pin "1") (pinfunction "S_1") (pintype "passive"))
      (node (ref "Q11") (pin "2") (pinfunction "S_2") (pintype "passive"))
      (node (ref "Q11") (pin "3") (pinfunction "S_3") (pintype "passive"))
      (node (ref "Q12") (pin "1") (pinfunction "S_1") (pintype "passive"))
      (node (ref "Q12") (pin "2") (pinfunction "S_2") (pintype "passive"))
      (node (ref "Q12") (pin "3") (pinfunction "S_3") (pintype "passive"))
      (node (ref "Q17") (pin "1") (pinfunction "S_1") (pintype "passive"))
      (node (ref "Q17") (pin "2") (pinfunction "S_2") (pintype "passive"))
      (node (ref "Q17") (pin "3") (pinfunction "S_3") (pintype "passive"))
      (node (ref "Q18") (pin "1") (pinfunction "S_1") (pintype "passive"))
      (node (ref "Q18") (pin "2") (pinfunction "S_2") (pintype "passive"))
      (node (ref "Q18") (pin "3") (pinfunction "S_3") (pintype "passive"))
      (node (ref "Q19") (pin "1") (pinfunction "S_1") (pintype "passive"))
      (node (ref "Q19") (pin "2") (pinfunction "S_2") (pintype "passive"))
      (node (ref "Q19") (pin "3") (pinfunction "S_3") (pintype "passive"))
      (node (ref "Q20") (pin "1") (pinfunction "S_1") (pintype "passive"))
      (node (ref "Q20") (pin "2") (pinfunction "S_2") (pintype "passive"))
      (node (ref "Q20") (pin "3") (pinfunction "S_3") (pintype "passive"))
      (node (ref "Q21") (pin "1") (pinfunction "S_1") (pintype "passive"))
      (node (ref "Q21") (pin "2") (pinfunction "S_2") (pintype "passive"))
      (node (ref "Q21") (pin "3") (pinfunction "S_3") (pintype "passive"))
      (node (ref "Q22") (pin "1") (pinfunction "S_1") (pintype "passive"))
      (node (ref "Q22") (pin "2") (pinfunction "S_2") (pintype "passive"))
      (node (ref "Q22") (pin "3") (pinfunction "S_3") (pintype "passive"))
      (node (ref "Q23") (pin "1") (pinfunction "S_1") (pintype "passive"))
      (node (ref "Q23") (pin "2") (pinfunction "S_2") (pintype "passive"))
      (node (ref "Q23") (pin "3") (pinfunction "S_3") (pintype "passive"))
      (node (ref "Q24") (pin "1") (pinfunction "S_1") (pintype "passive"))
      (node (ref "Q24") (pin "2") (pinfunction "S_2") (pintype "passive"))
      (node (ref "Q24") (pin "3") (pinfunction "S_3") (pintype "passive"))
      (node (ref "Q29") (pin "1") (pinfunction "S_1") (pintype "passive"))
      (node (ref "Q29") (pin "2") (pinfunction "S_2") (pintype "passive"))
      (node (ref "Q29") (pin "3") (pinfunction "S_3") (pintype "passive"))
      (node (ref "Q30") (pin "1") (pinfunction "S_1") (pintype "passive"))
      (node (ref "Q30") (pin "2") (pinfunction "S_2") (pintype "passive"))
      (node (ref "Q30") (pin "3") (pinfunction "S_3") (pintype "passive"))
      (node (ref "Q31") (pin "1") (pinfunction "S_1") (pintype "passive"))
      (node (ref "Q31") (pin "2") (pinfunction "S_2") (pintype "passive"))
      (node (ref "Q31") (pin "3") (pinfunction "S_3") (pintype "passive"))
      (node (ref "Q32") (pin "1") (pinfunction "S_1") (pintype "passive"))
      (node (ref "Q32") (pin "2") (pinfunction "S_2") (pintype "passive"))
      (node (ref "Q32") (pin "3") (pinfunction "S_3") (pintype "passive"))
      (node (ref "Q33") (pin "1") (pinfunction "S_1") (pintype "passive"))
      (node (ref "Q33") (pin "2") (pinfunction "S_2") (pintype "passive"))
      (node (ref "Q33") (pin "3") (pinfunction "S_3") (pintype "passive"))
      (node (ref "Q34") (pin "1") (pinfunction "S_1") (pintype "passive"))
      (node (ref "Q34") (pin "2") (pinfunction "S_2") (pintype "passive"))
      (node (ref "Q34") (pin "3") (pinfunction "S_3") (pintype "passive"))
      (node (ref "Q35") (pin "1") (pinfunction "S_1") (pintype "passive"))
      (node (ref "Q35") (pin "2") (pinfunction "S_2") (pintype "passive"))
      (node (ref "Q35") (pin "3") (pinfunction "S_3") (pintype "passive"))
      (node (ref "Q36") (pin "1") (pinfunction "S_1") (pintype "passive"))
      (node (ref "Q36") (pin "2") (pinfunction "S_2") (pintype "passive"))
      (node (ref "Q36") (pin "3") (pinfunction "S_3") (pintype "passive"))
      (node (ref "Q41") (pin "1") (pinfunction "S_1") (pintype "passive"))
      (node (ref "Q41") (pin "2") (pinfunction "S_2") (pintype "passive"))
      (node (ref "Q41") (pin "3") (pinfunction "S_3") (pintype "passive"))
      (node (ref "Q42") (pin "1") (pinfunction "S_1") (pintype "passive"))
      (node (ref "Q42") (pin "2") (pinfunction "S_2") (pintype "passive"))
      (node (ref "Q42") (pin "3") (pinfunction "S_3") (pintype "passive"))
      (node (ref "Q43") (pin "1") (pinfunction "S_1") (pintype "passive"))
      (node (ref "Q43") (pin "2") (pinfunction "S_2") (pintype "passive"))
      (node (ref "Q43") (pin "3") (pinfunction "S_3") (pintype "passive"))
      (node (ref "Q44") (pin "1") (pinfunction "S_1") (pintype "passive"))
      (node (ref "Q44") (pin "2") (pinfunction "S_2") (pintype "passive"))
      (node (ref "Q44") (pin "3") (pinfunction "S_3") (pintype "passive"))
      (node (ref "Q45") (pin "1") (pinfunction "S_1") (pintype "passive"))
      (node (ref "Q45") (pin "2") (pinfunction "S_2") (pintype "passive"))
      (node (ref "Q45") (pin "3") (pinfunction "S_3") (pintype "passive"))
      (node (ref "Q46") (pin "1") (pinfunction "S_1") (pintype "passive"))
      (node (ref "Q46") (pin "2") (pinfunction "S_2") (pintype "passive"))
      (node (ref "Q46") (pin "3") (pinfunction "S_3") (pintype "passive"))
      (node (ref "Q47") (pin "1") (pinfunction "S_1") (pintype "passive"))
      (node (ref "Q47") (pin "2") (pinfunction "S_2") (pintype "passive"))
      (node (ref "Q47") (pin "3") (pinfunction "S_3") (pintype "passive"))
      (node (ref "Q48") (pin "1") (pinfunction "S_1") (pintype "passive"))
      (node (ref "Q48") (pin "2") (pinfunction "S_2") (pintype "passive"))
      (node (ref "Q48") (pin "3") (pinfunction "S_3") (pintype "passive"))
      (node (ref "Q5") (pin "1") (pinfunction "S_1") (pintype "passive"))
      (node (ref "Q5") (pin "2") (pinfunction "S_2") (pintype "passive"))
      (node (ref "Q5") (pin "3") (pinfunction "S_3") (pintype "passive"))
      (node (ref "Q6") (pin "1") (pinfunction "S_1") (pintype "passive"))
      (node (ref "Q6") (pin "2") (pinfunction "S_2") (pintype "passive"))
      (node (ref "Q6") (pin "3") (pinfunction "S_3") (pintype "passive"))
      (node (ref "Q7") (pin "1") (pinfunction "S_1") (pintype "passive"))
      (node (ref "Q7") (pin "2") (pinfunction "S_2") (pintype "passive"))
      (node (ref "Q7") (pin "3") (pinfunction "S_3") (pintype "passive"))
      (node (ref "Q8") (pin "1") (pinfunction "S_1") (pintype "passive"))
      (node (ref "Q8") (pin "2") (pinfunction "S_2") (pintype "passive"))
      (node (ref "Q8") (pin "3") (pinfunction "S_3") (pintype "passive"))
      (node (ref "Q9") (pin "1") (pinfunction "S_1") (pintype "passive"))
      (node (ref "Q9") (pin "2") (pinfunction "S_2") (pintype "passive"))
      (node (ref "Q9") (pin "3") (pinfunction "S_3") (pintype "passive"))
      (node (ref "U11") (pin "4") (pinfunction "GND_4") (pintype "passive"))
      (node (ref "U11") (pin "9") (pinfunction "EP_9") (pintype "passive"))
      (node (ref "U12") (pin "4") (pinfunction "GND_4") (pintype "passive"))
      (node (ref "U12") (pin "9") (pinfunction "EP_9") (pintype "passive"))
      (node (ref "U13") (pin "4") (pinfunction "GND_4") (pintype "passive"))
      (node (ref "U13") (pin "9") (pinfunction "EP_9") (pintype "passive"))
      (node (ref "U14") (pin "4") (pinfunction "GND_4") (pintype "passive"))
      (node (ref "U14") (pin "9") (pinfunction "EP_9") (pintype "passive"))
      (node (ref "U15") (pin "4") (pinfunction "GND_4") (pintype "passive"))
      (node (ref "U15") (pin "9") (pinfunction "EP_9") (pintype "passive"))
      (node (ref "U16") (pin "4") (pinfunction "GND_4") (pintype "passive"))
      (node (ref "U16") (pin "9") (pinfunction "EP_9") (pintype "passive"))
      (node (ref "U17") (pin "4") (pinfunction "GND_4") (pintype "passive"))
      (node (ref "U17") (pin "9") (pinfunction "EP_9") (pintype "passive"))
      (node (ref "U18") (pin "4") (pinfunction "GND_4") (pintype "passive"))
      (node (ref "U18") (pin "9") (pinfunction "EP_9") (pintype "passive"))
      (node (ref "U19") (pin "4") (pinfunction "GND_4") (pintype "passive"))
      (node (ref "U19") (pin "9") (pinfunction "EP_9") (pintype "passive"))
      (node (ref "U20") (pin "4") (pinfunction "GND_4") (pintype "passive"))
      (node (ref "U20") (pin "9") (pinfunction "EP_9") (pintype "passive"))
      (node (ref "U21") (pin "4") (pinfunction "GND_4") (pintype "passive"))
      (node (ref "U21") (pin "9") (pinfunction "EP_9") (pintype "passive"))
      (node (ref "U22") (pin "4") (pinfunction "GND_4") (pintype "passive"))
      (node (ref "U22") (pin "9") (pinfunction "EP_9") (pintype "passive"))
      (node (ref "U23") (pin "4") (pinfunction "GND_4") (pintype "passive"))
      (node (ref "U23") (pin "9") (pinfunction "EP_9") (pintype "passive"))
      (node (ref "U24") (pin "4") (pinfunction "GND_4") (pintype "passive"))
      (node (ref "U24") (pin "9") (pinfunction "EP_9") (pintype "passive"))
      (node (ref "U25") (pin "4") (pinfunction "GND_4") (pintype "passive"))
      (node (ref "U25") (pin "9") (pinfunction "EP_9") (pintype "passive"))
      (node (ref "U26") (pin "4") (pinfunction "GND_4") (pintype "passive"))
      (node (ref "U26") (pin "9") (pinfunction "EP_9") (pintype "passive"))
    )
  )
)
